# M8416P.net
KiCad netlist of a schematic drawn in EAGLE
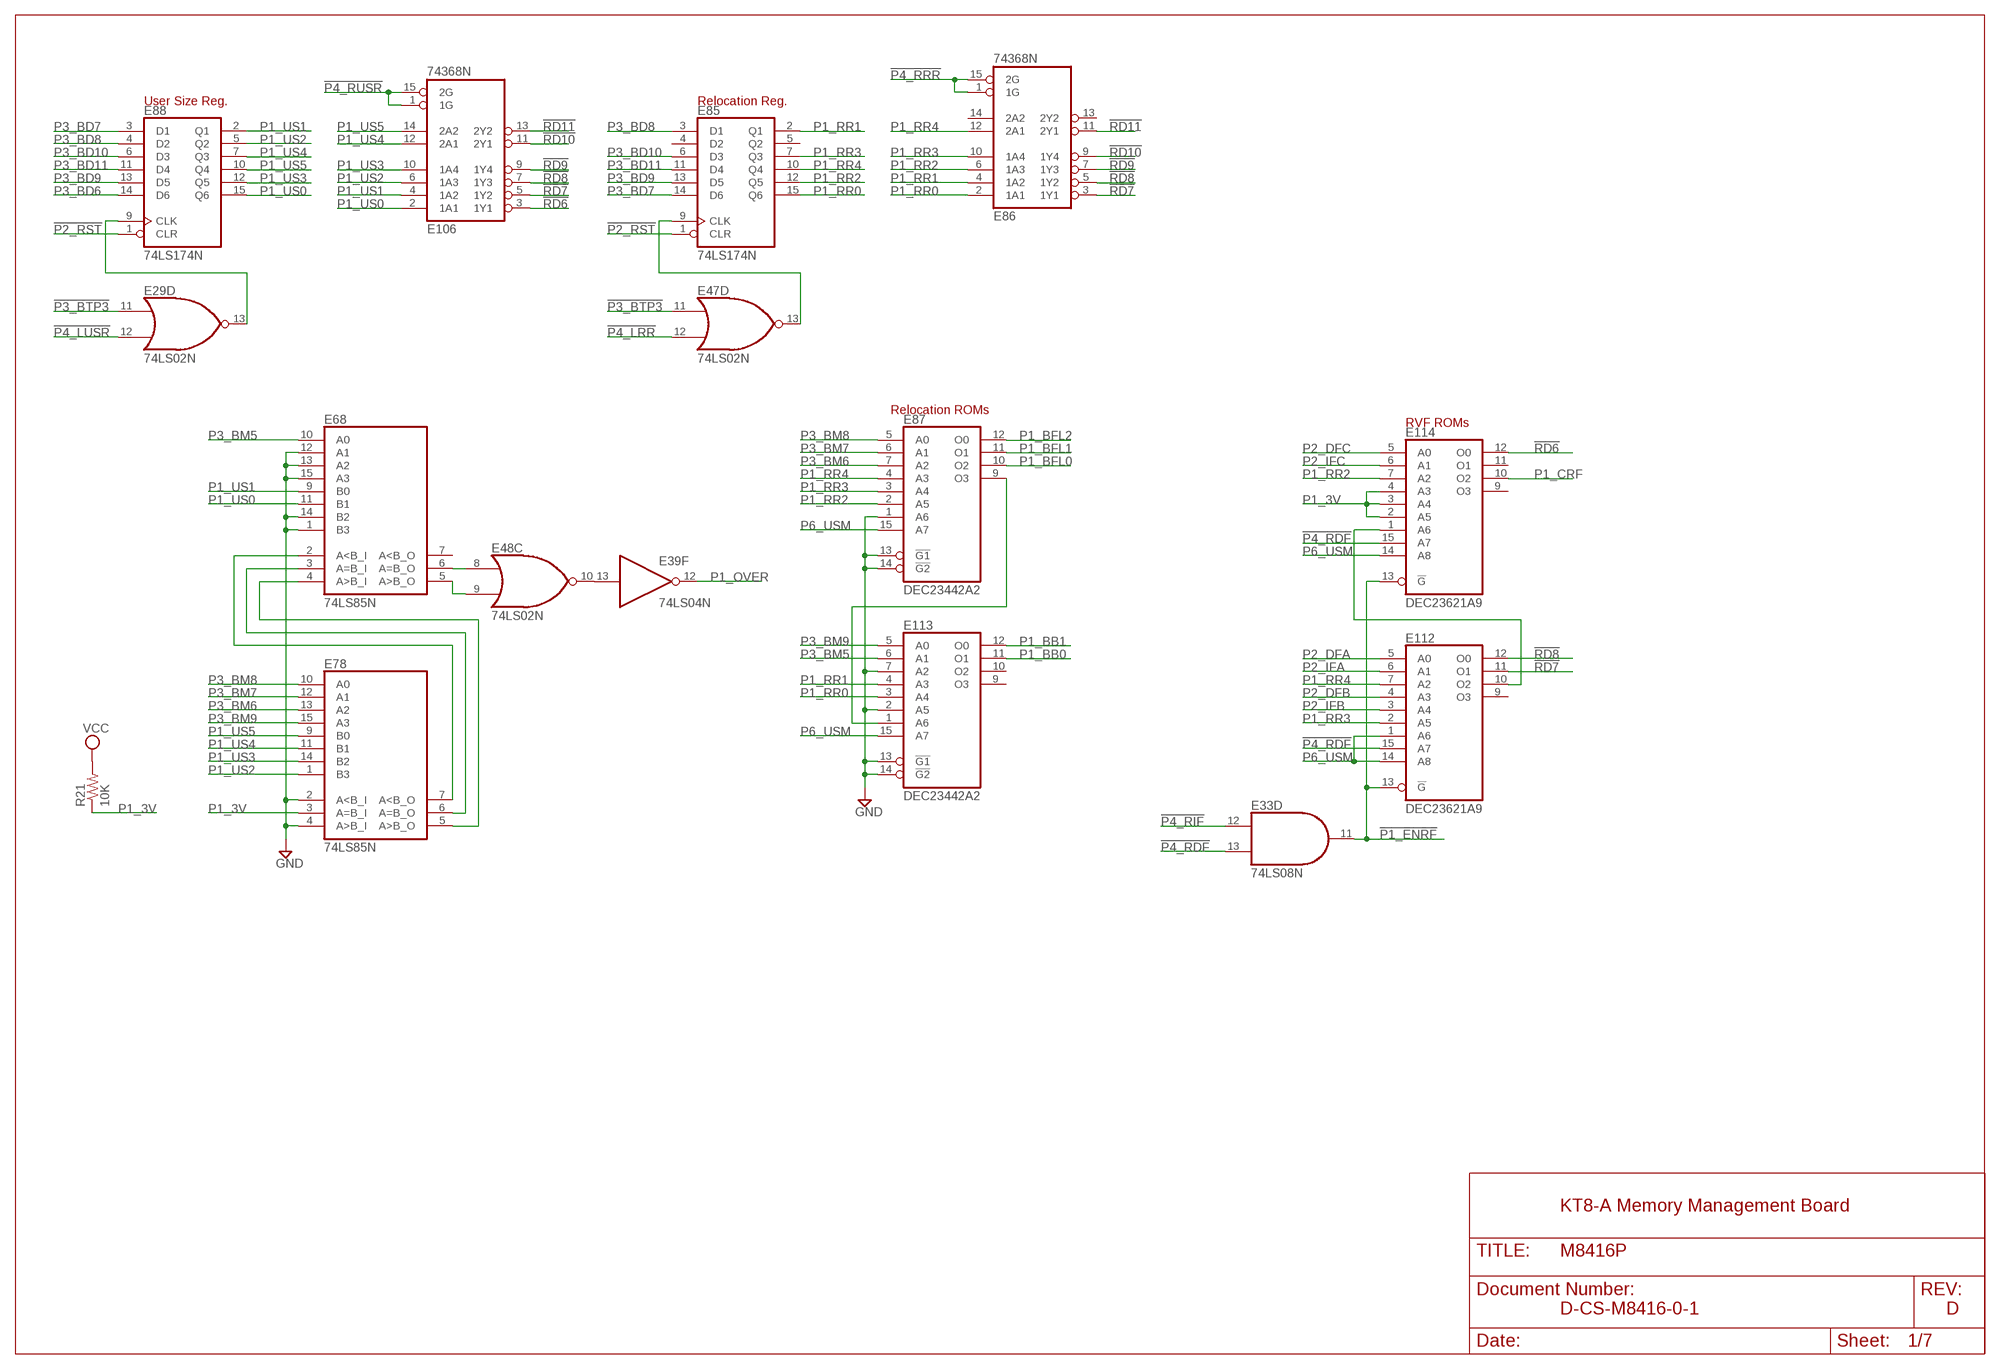
[diagram p0: schematic, sheet 1]
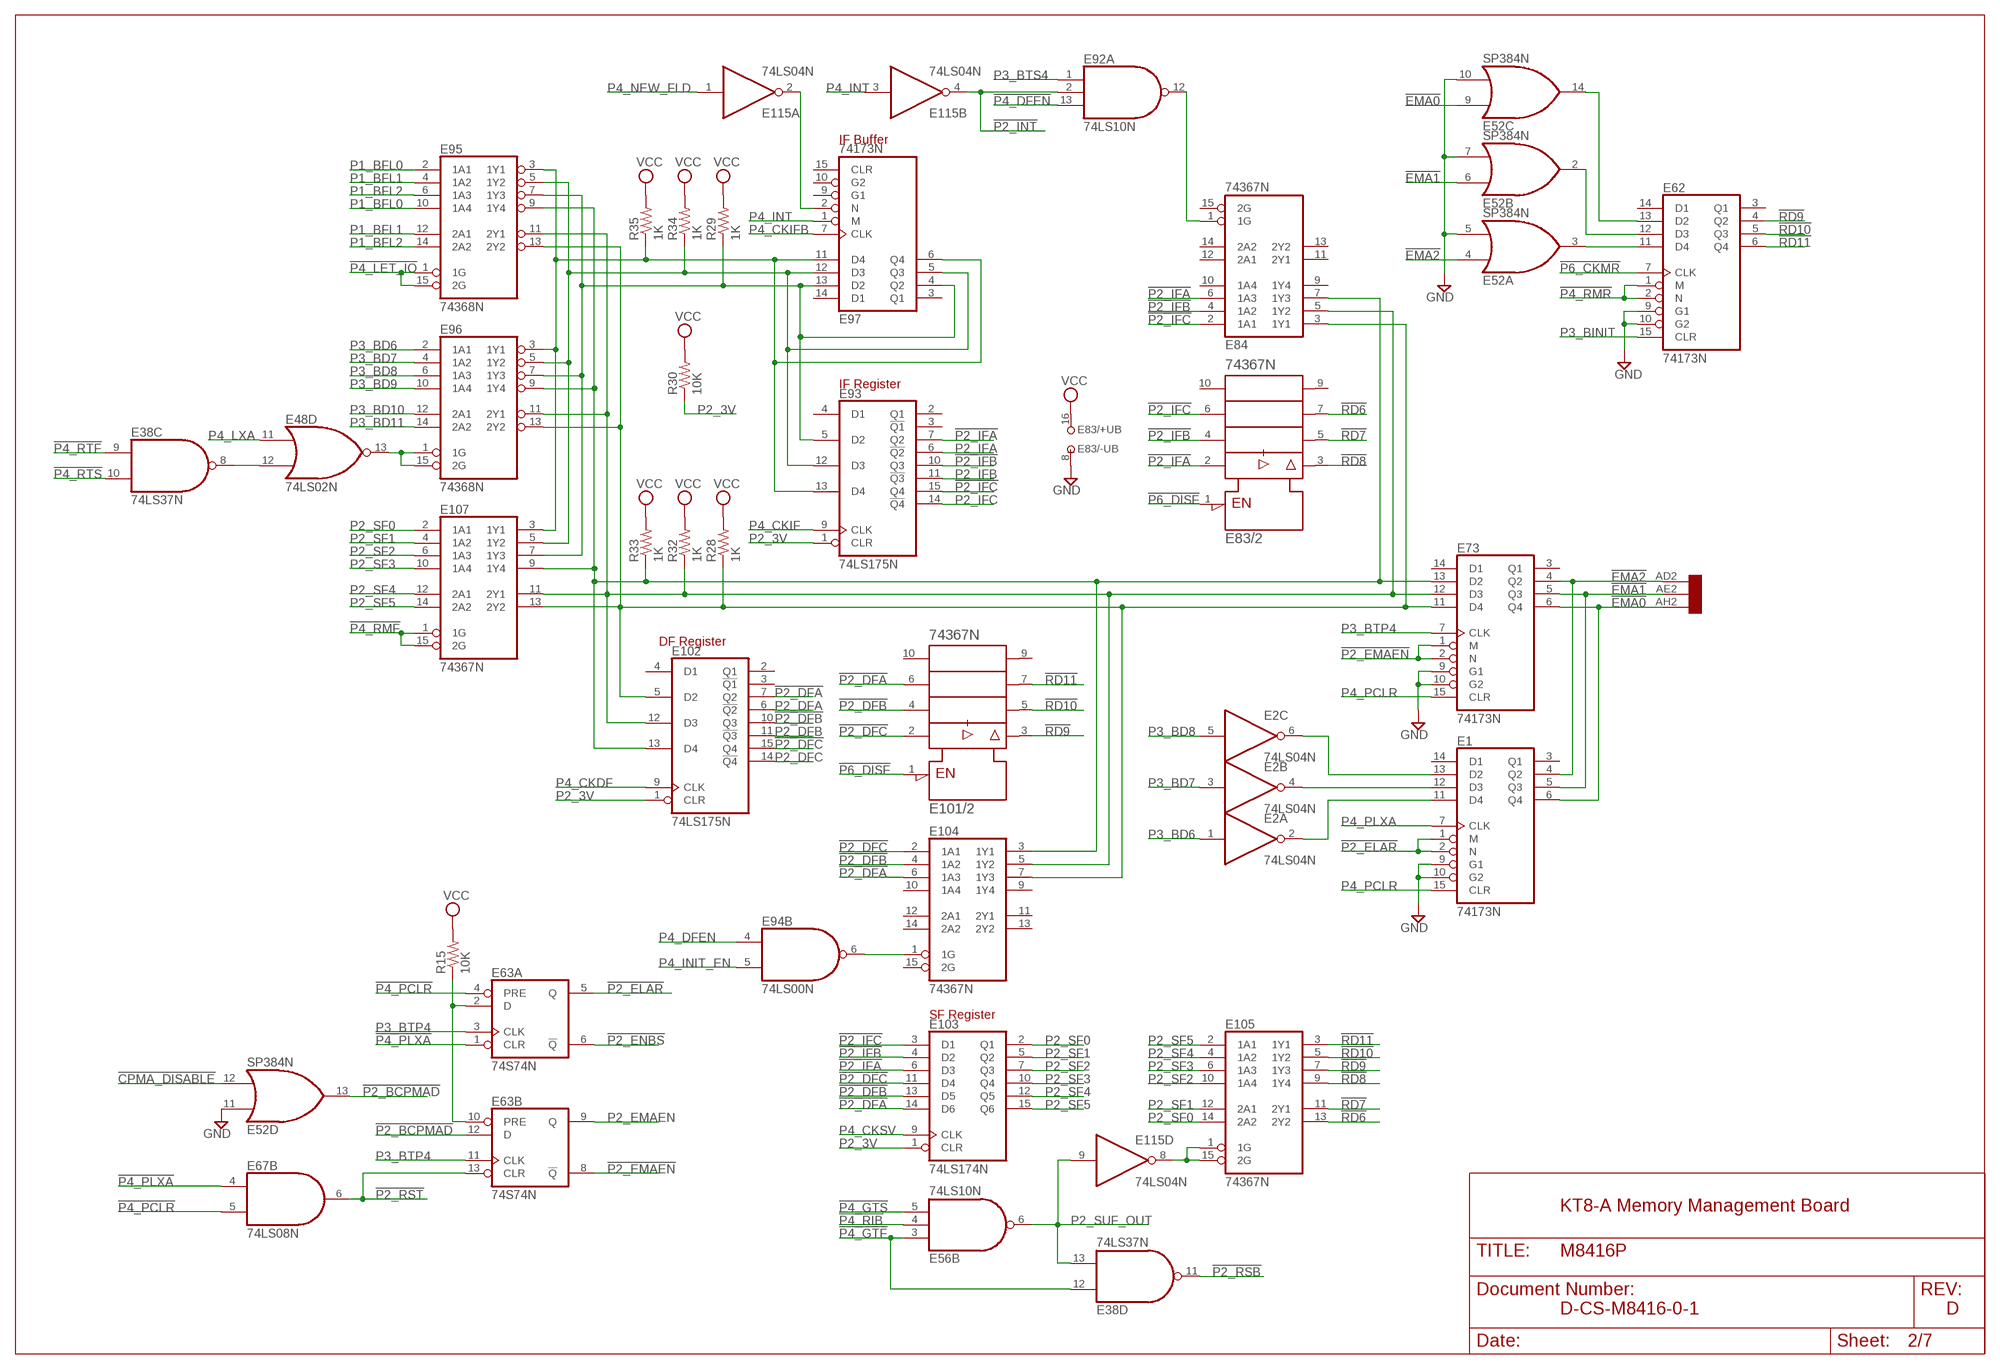
[diagram p1: schematic, sheet 2]
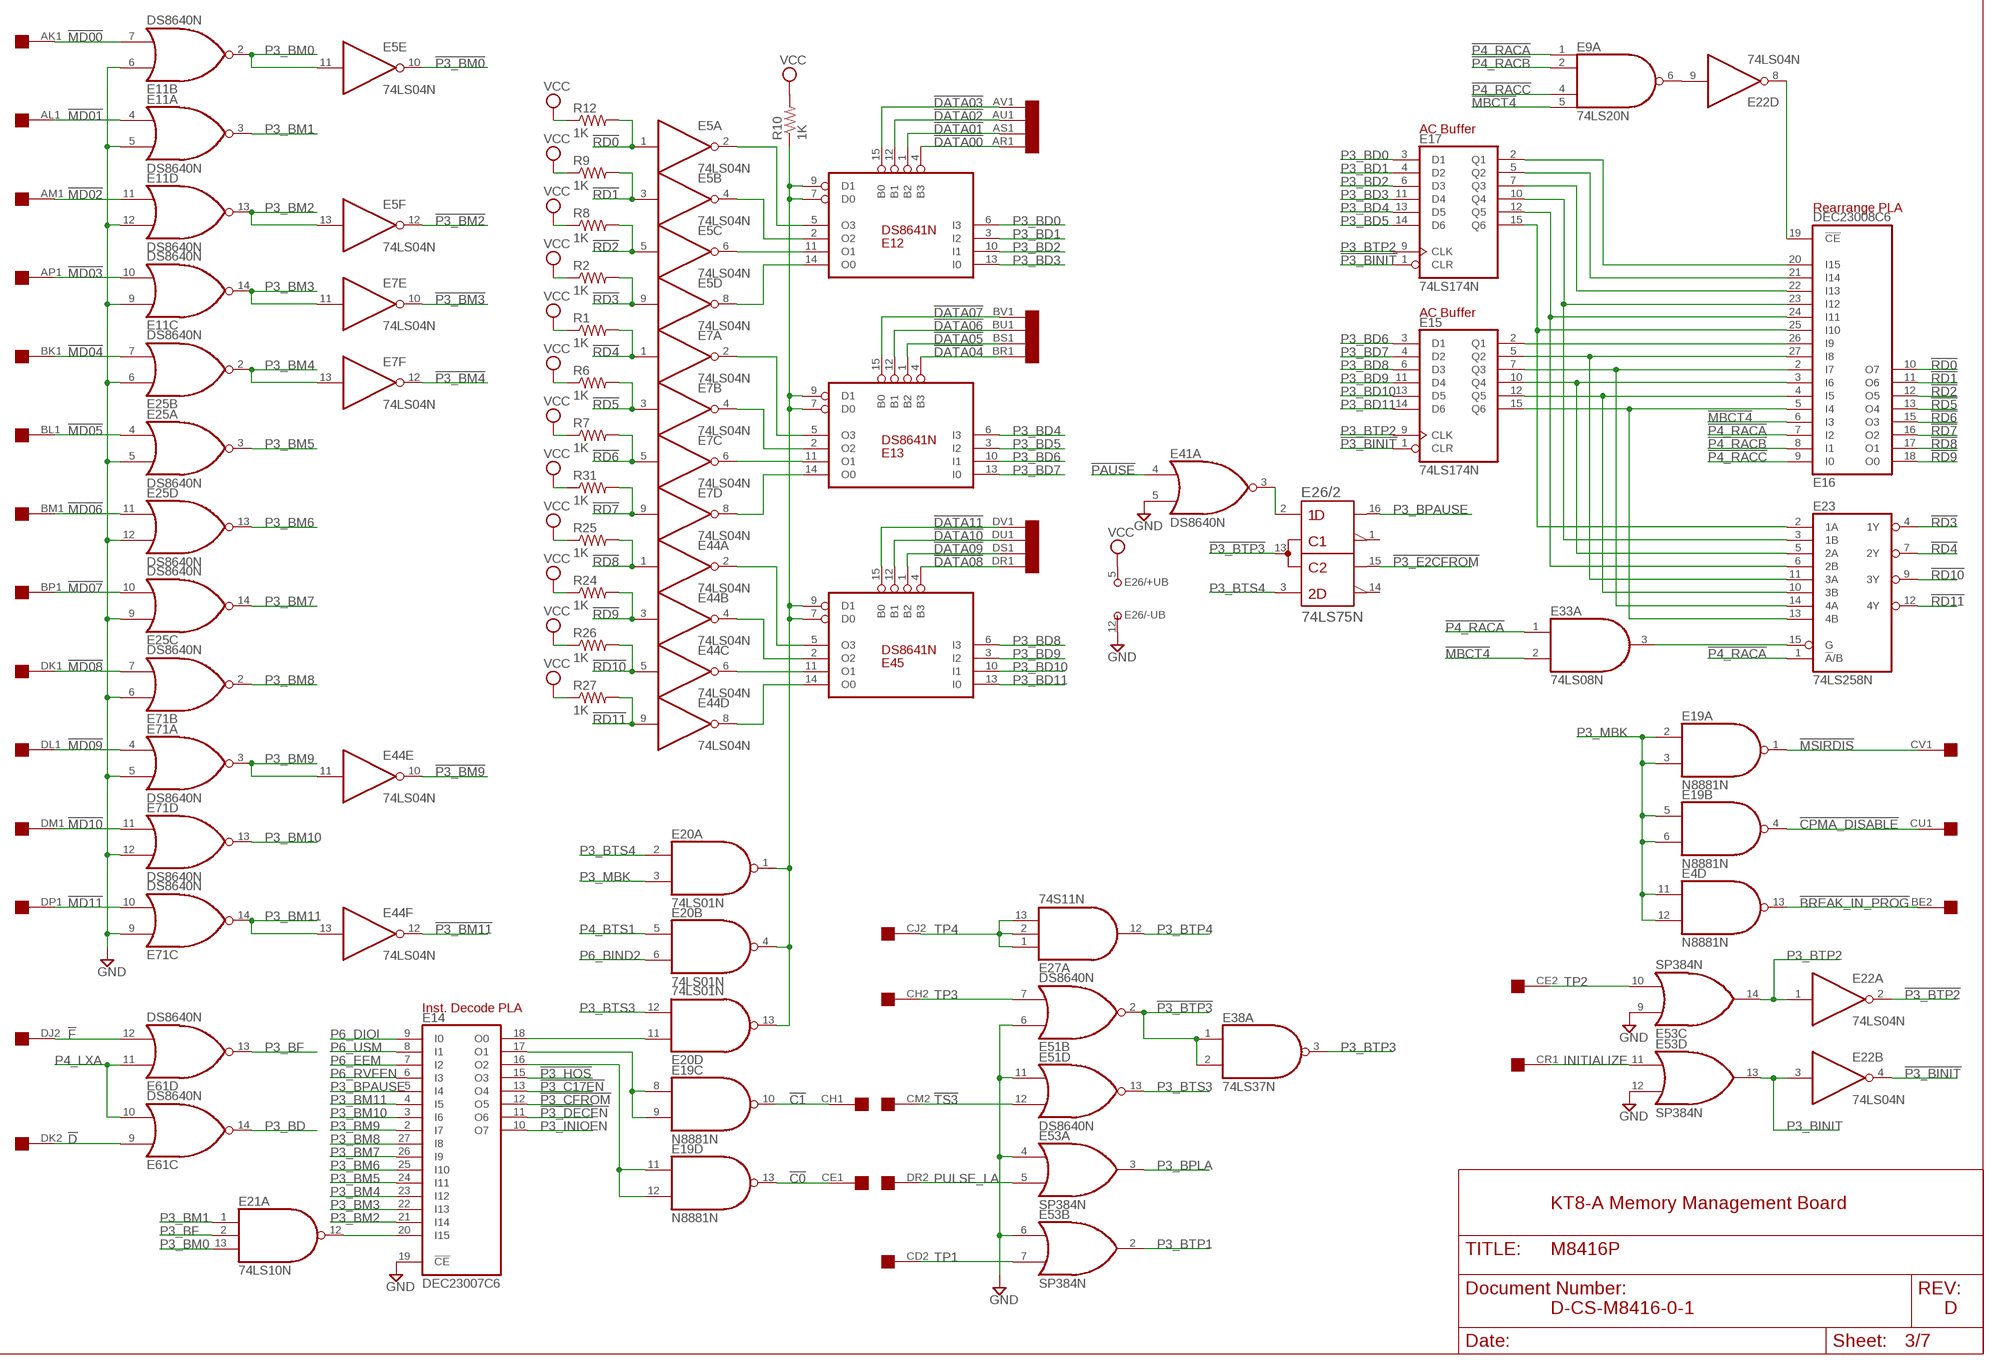
[diagram p2: schematic, sheet 3, part 1 of 2]
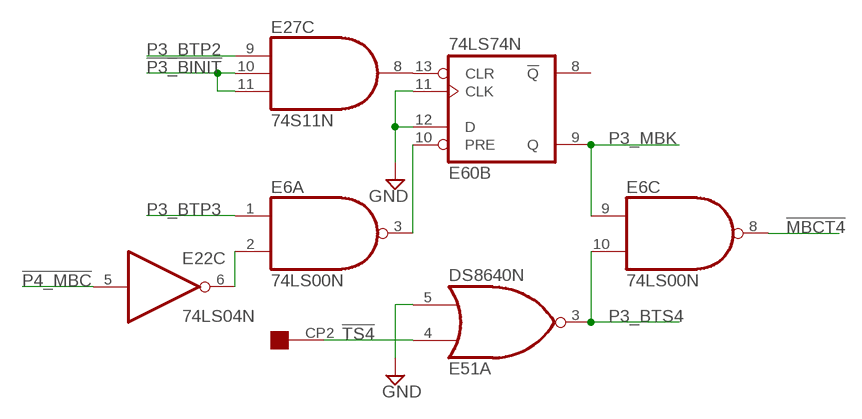
[diagram p3: schematic, sheet 3, part 2 of 2]
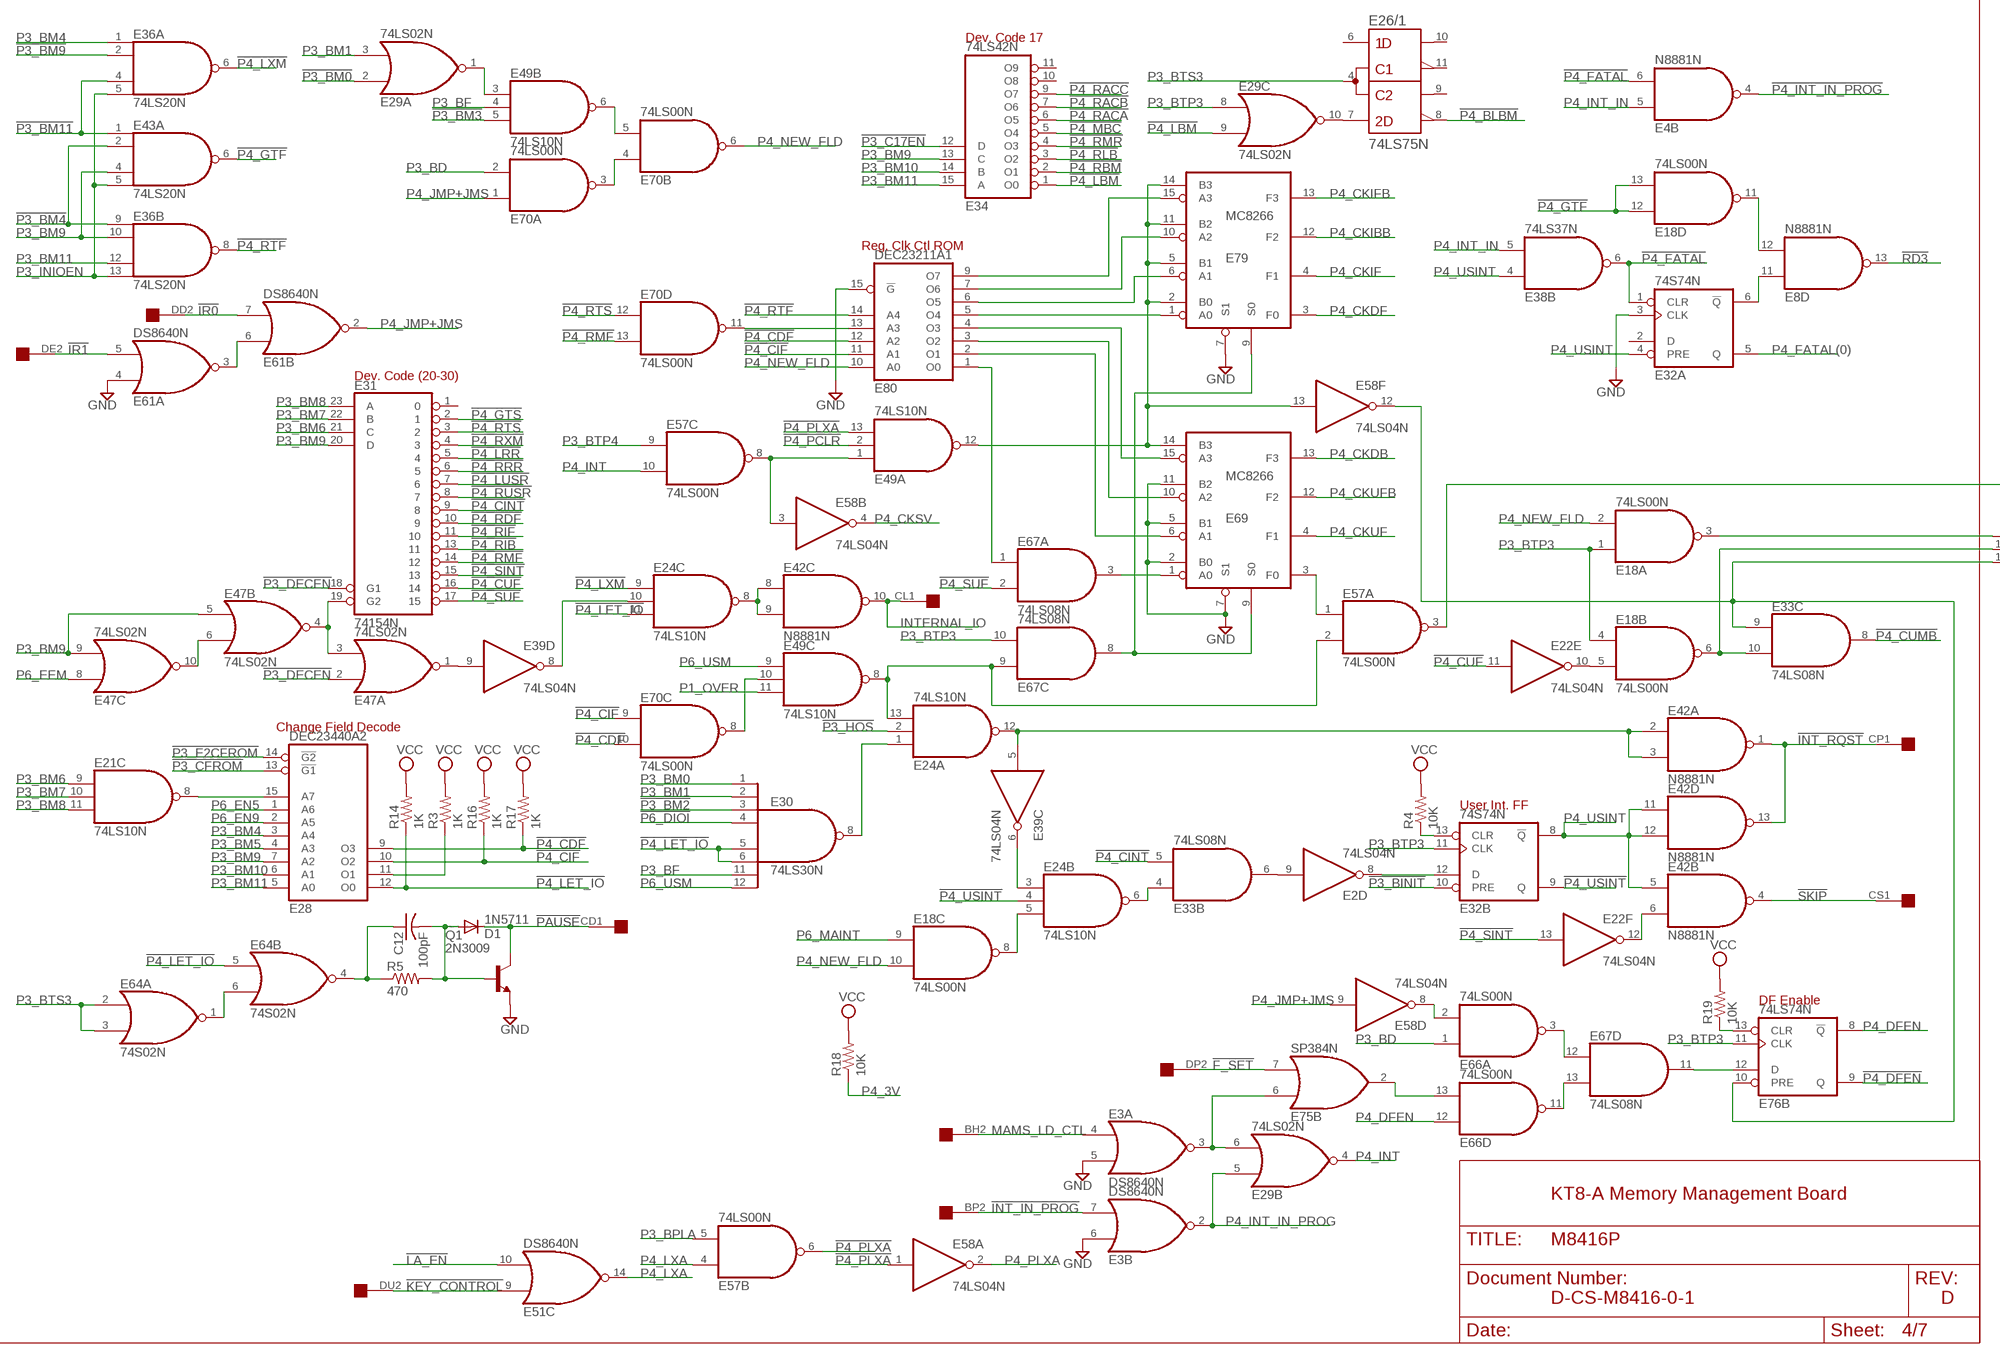
[diagram p4: schematic, sheet 4, part 1 of 2]
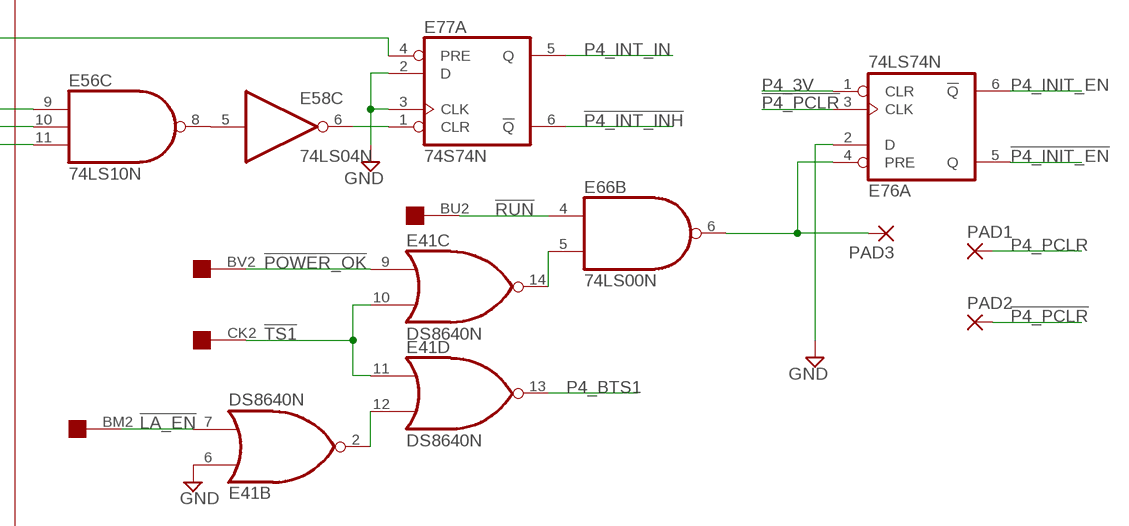
[diagram p5: schematic, sheet 4, part 2 of 2]
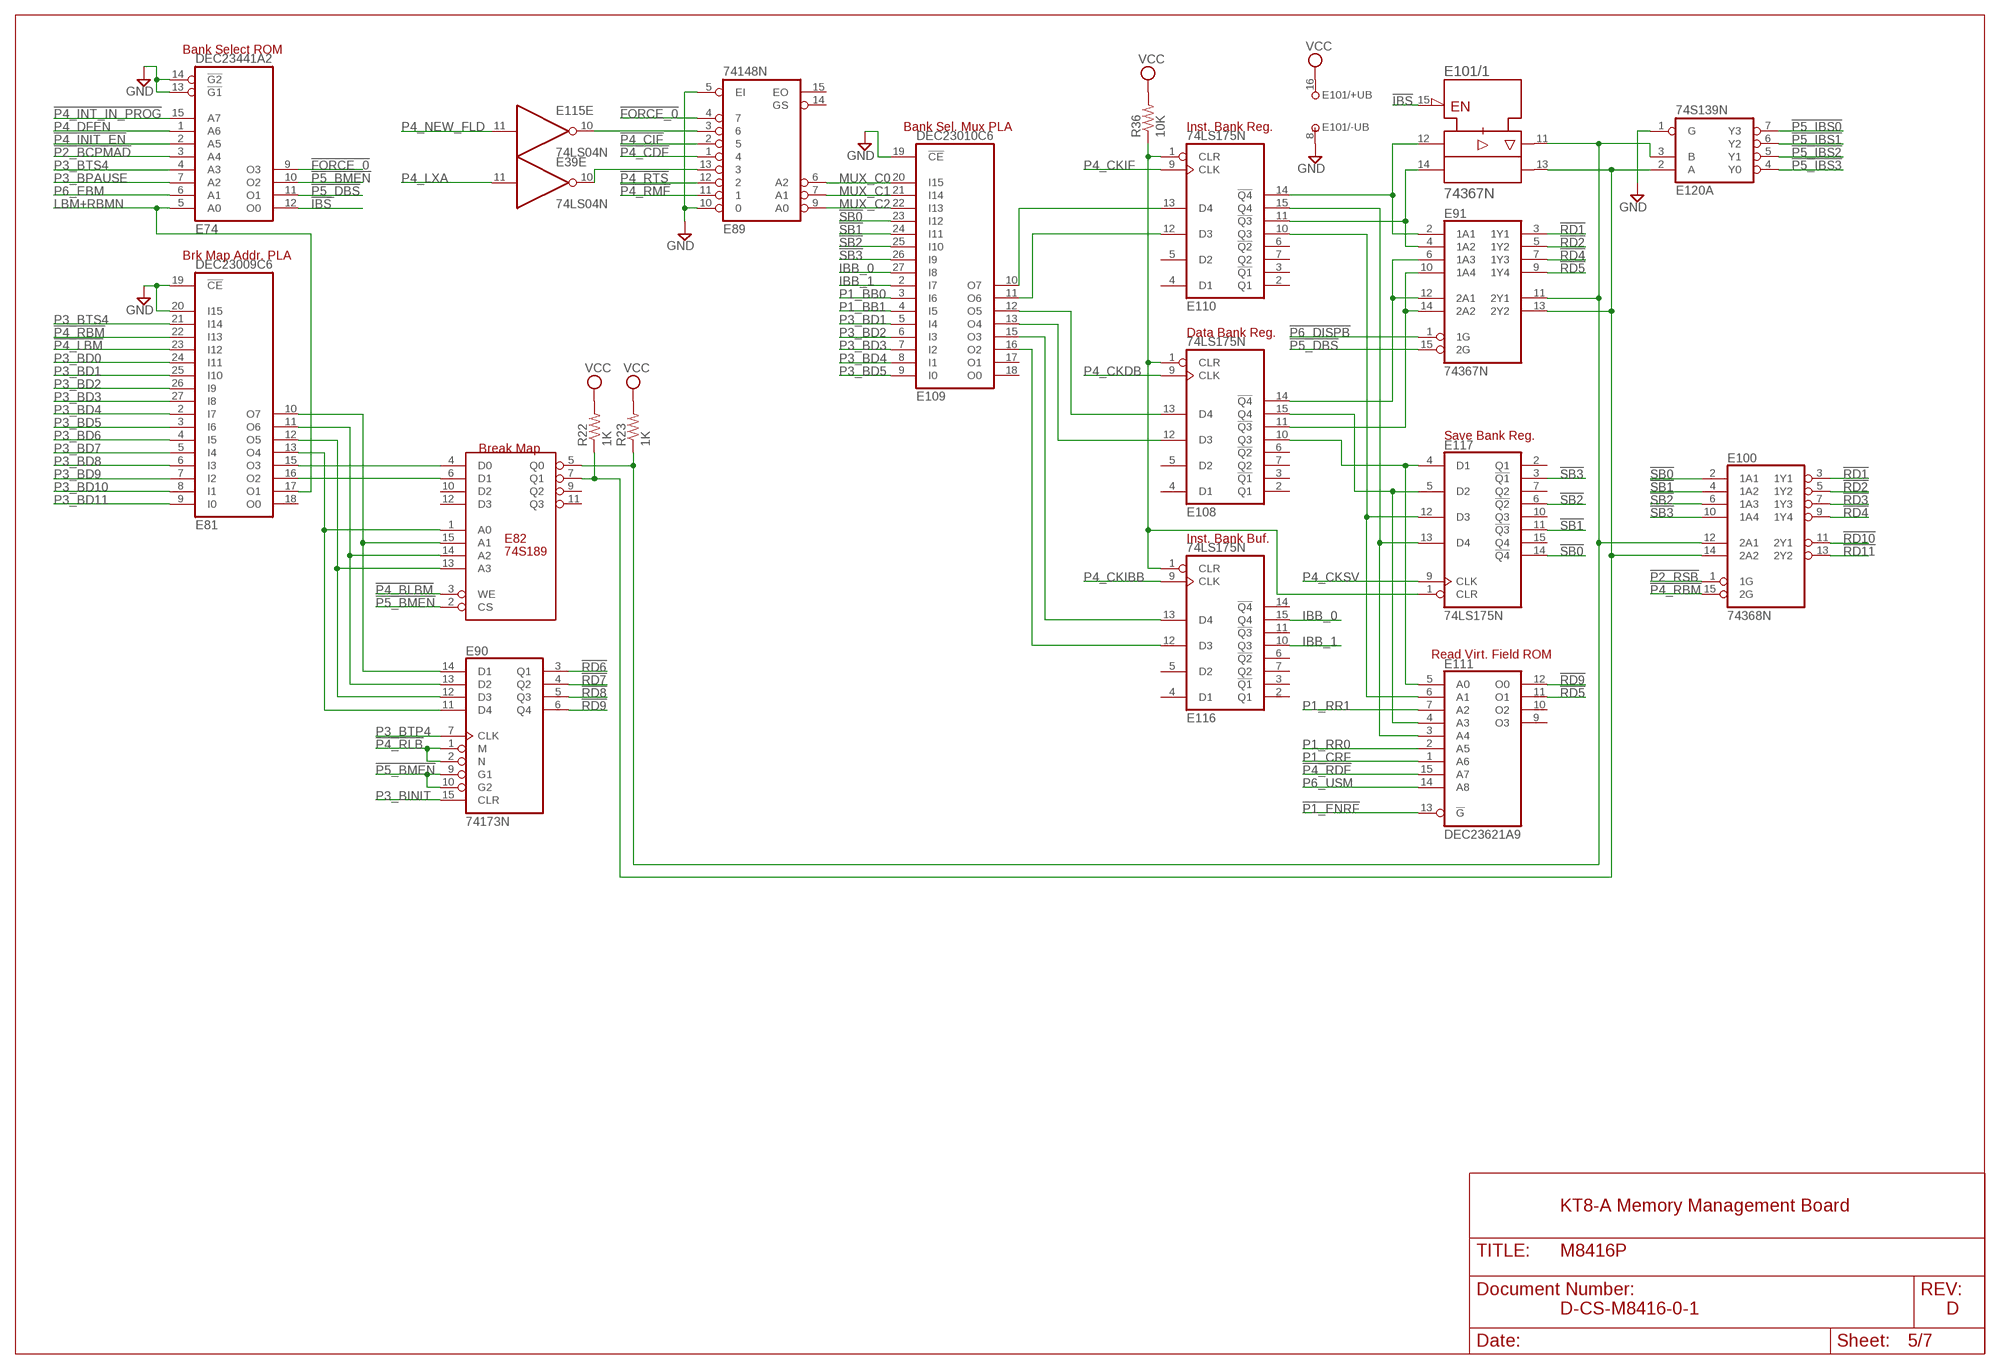
[diagram p6: schematic, sheet 5]
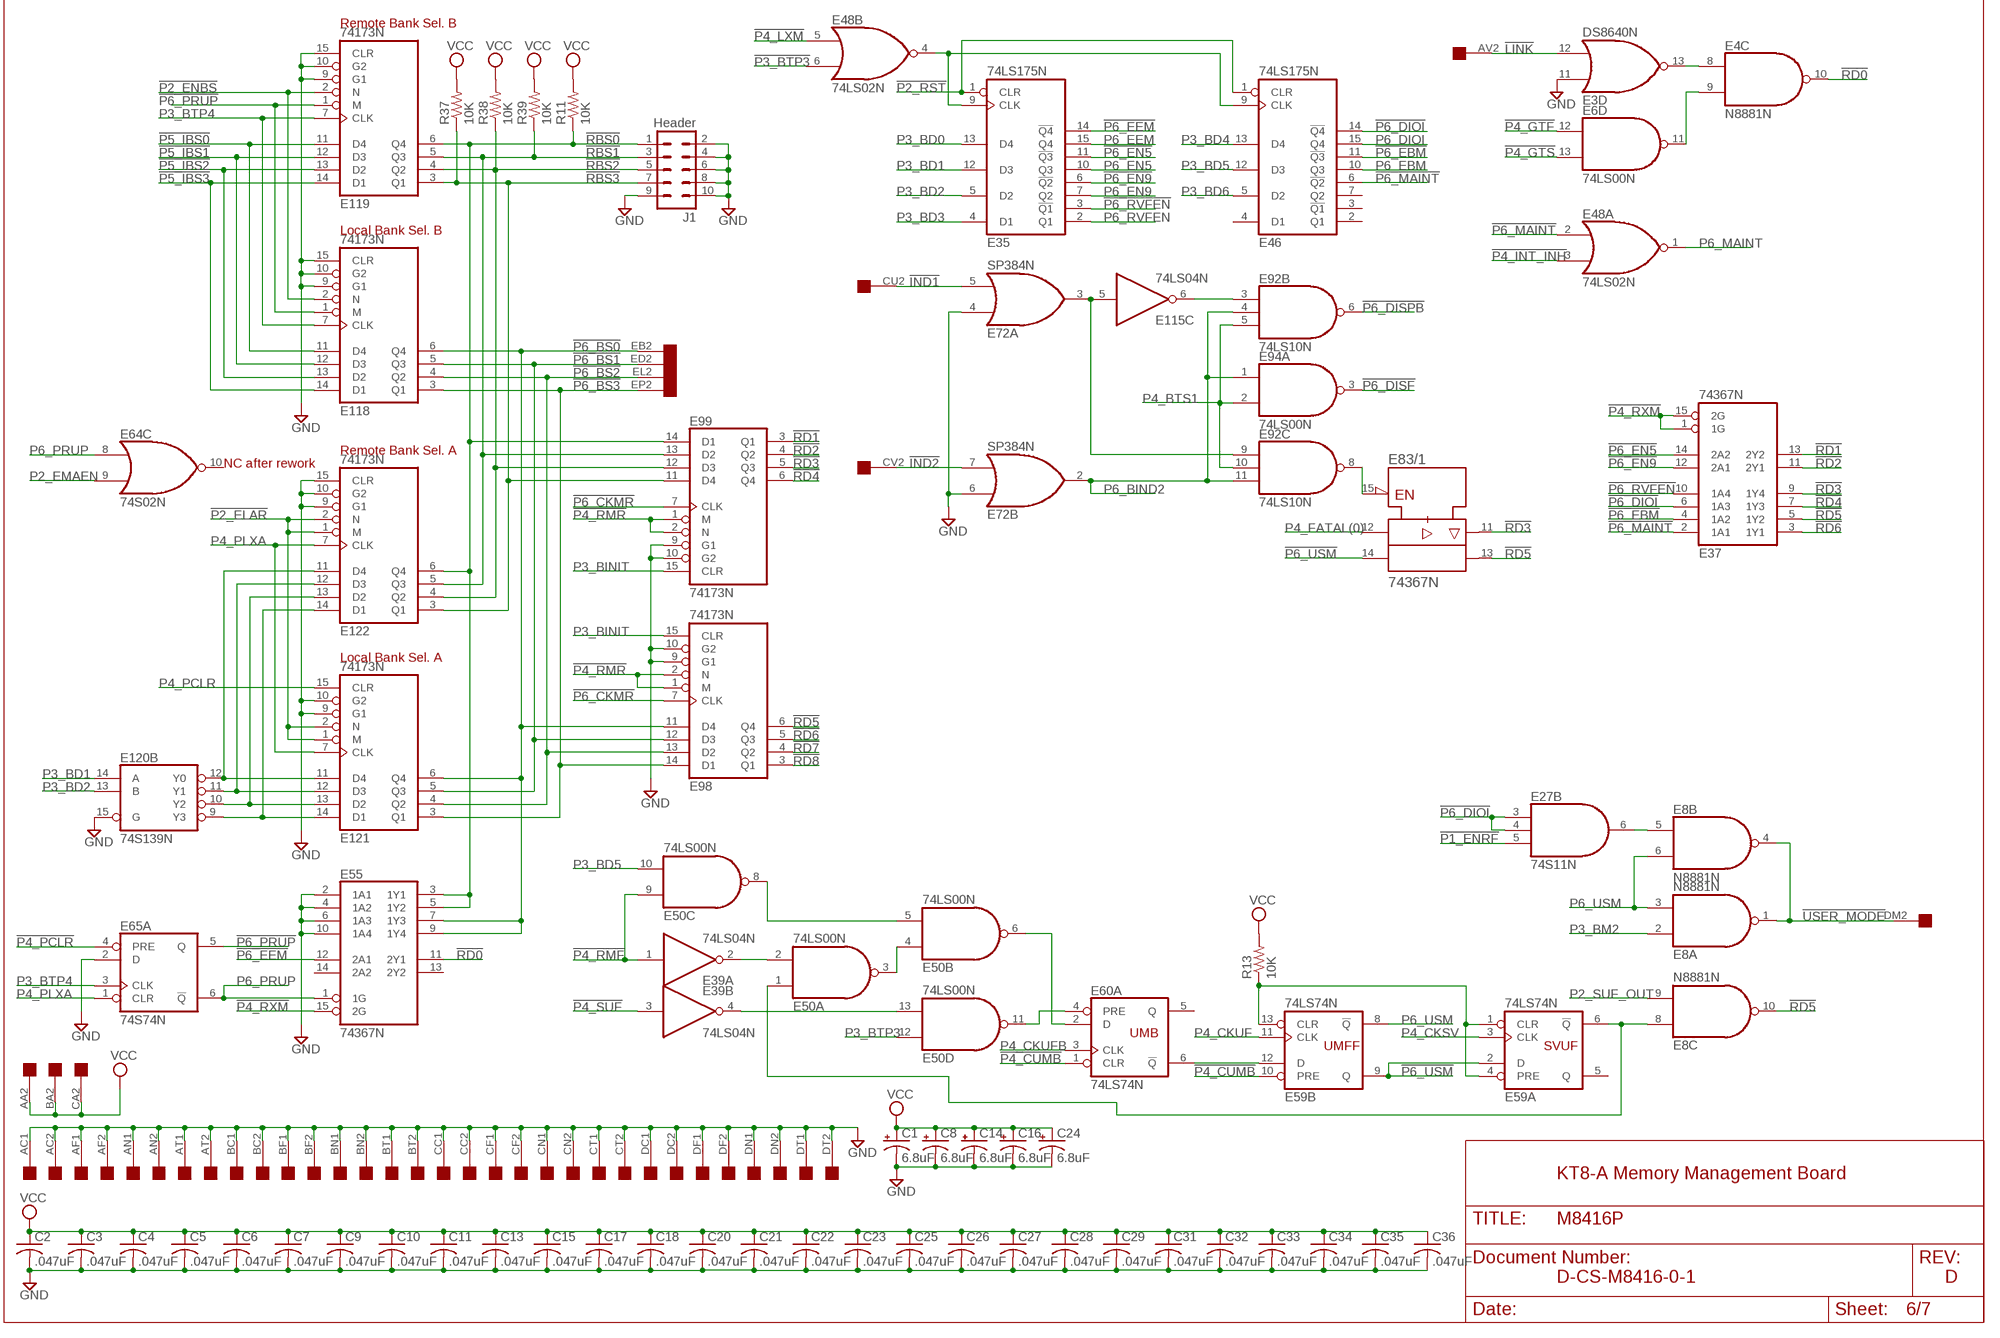
[diagram p7: schematic, sheet 6, part 1 of 2]
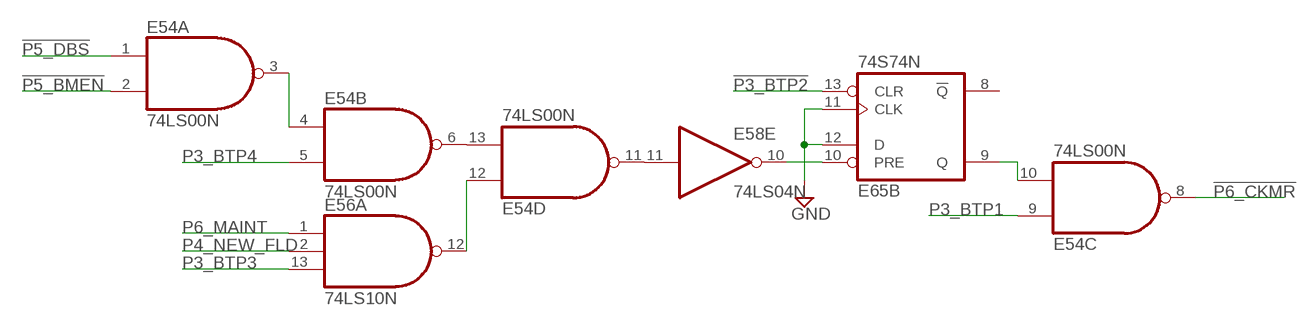
[diagram p8: schematic, sheet 6, part 2 of 2]
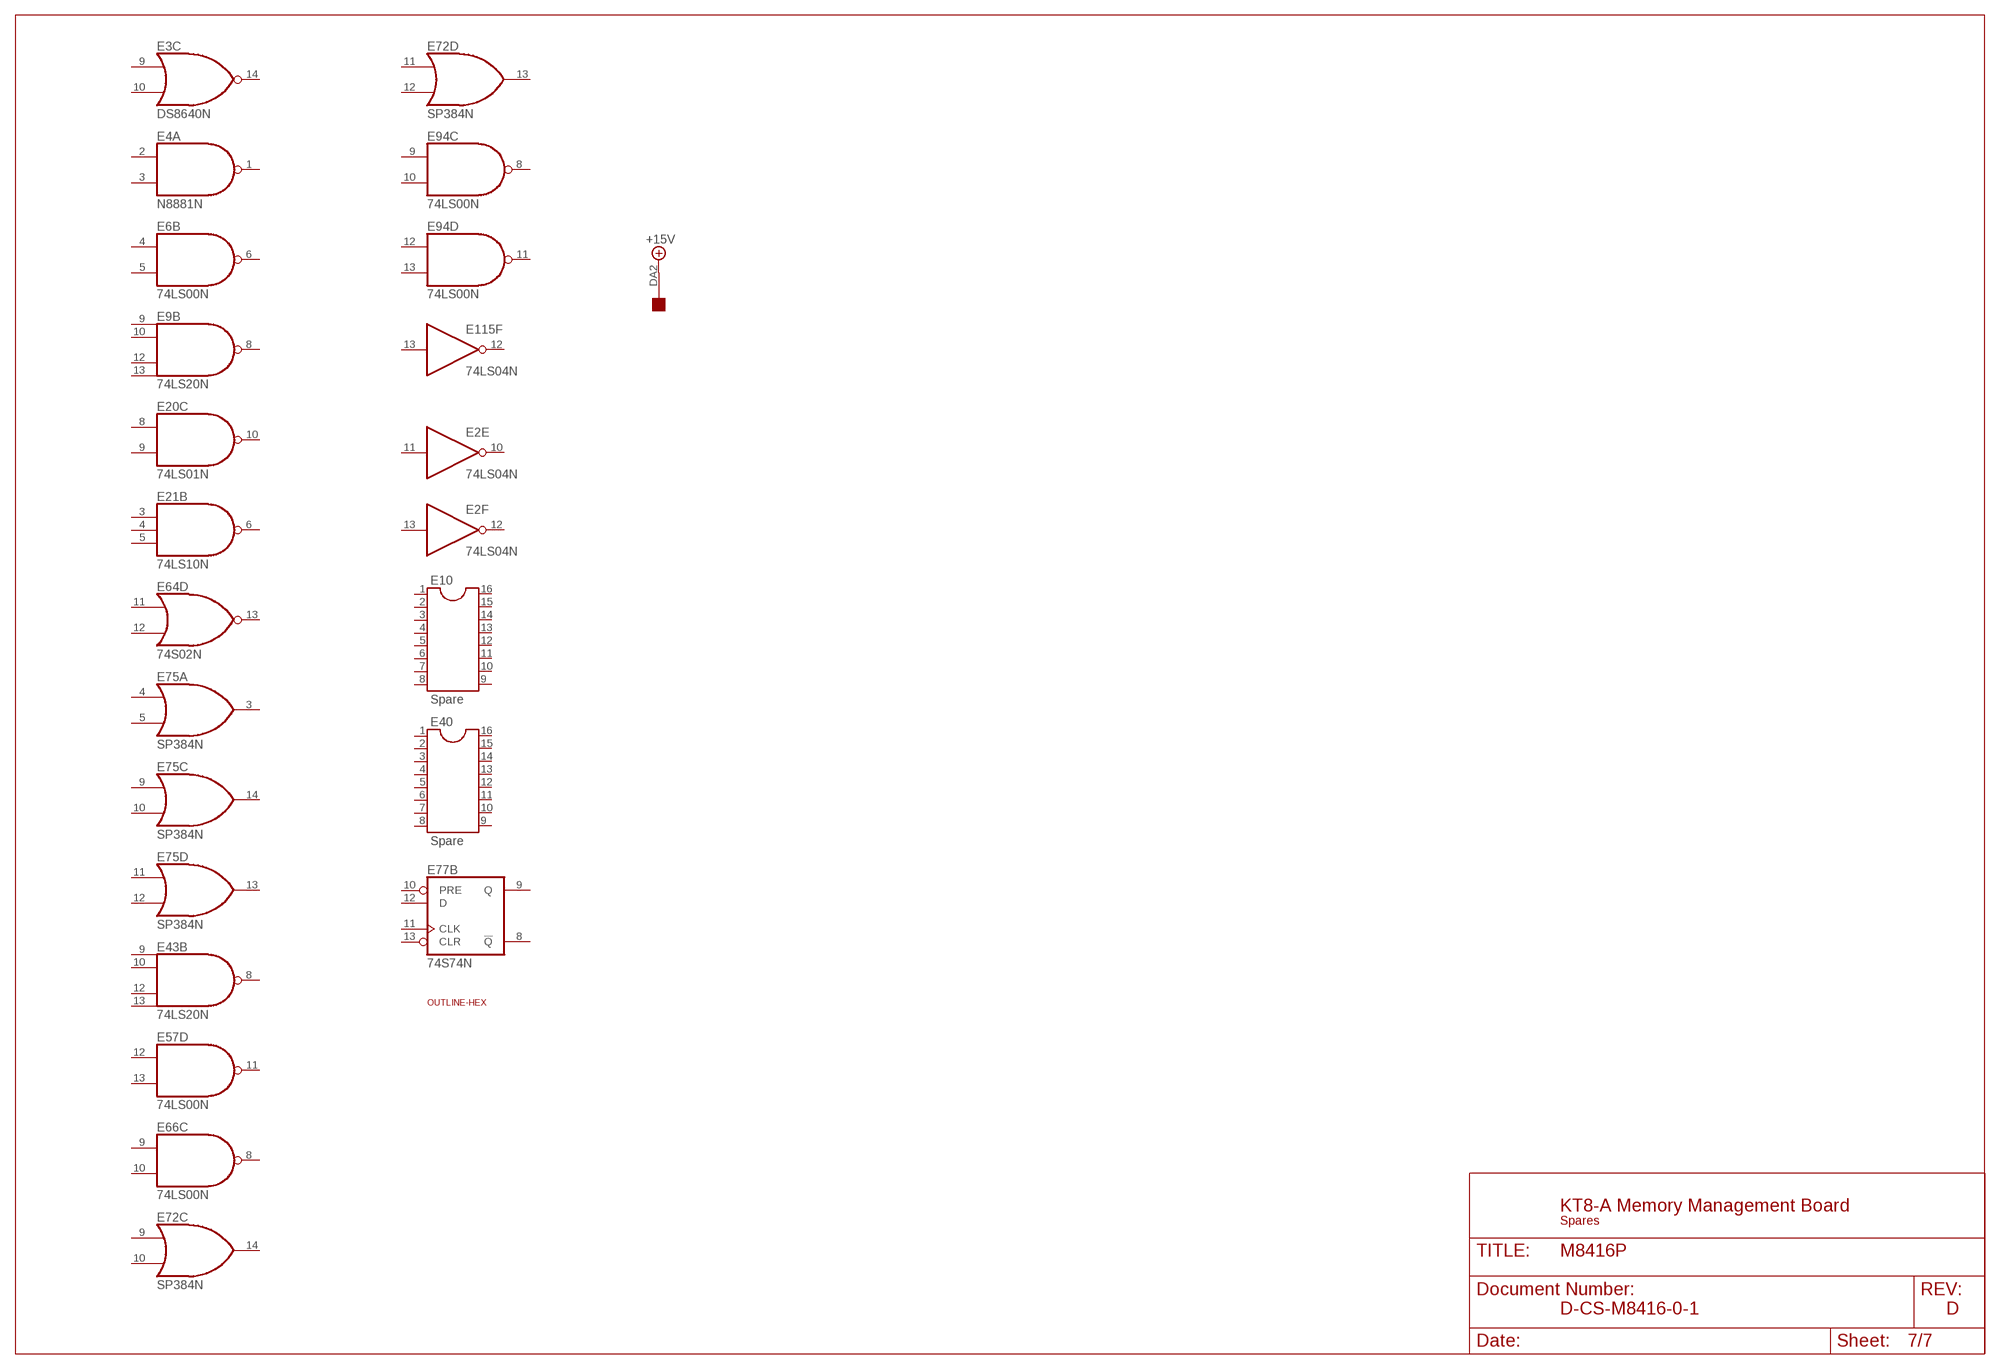
[diagram p9: schematic, sheet 7]

(export (version "E")
  (design (tool "Eeschema 10.0.6"))
  (components
    (comp (ref "E1")
      (value "74173N")
      (footprint "eagle-import:DIL16")
      (libsource (lib "eagle-import") (part "74173NLS"))
    )
    (comp (ref "E2")
      (value "74LS04N")
      (footprint "eagle-import:DIL14")
      (libsource (lib "eagle-import") (part "7404NLS"))
    )
    (comp (ref "E38")
      (value "74LS37N")
      (footprint "eagle-import:DIL14")
      (libsource (lib "eagle-import") (part "7437NLS"))
    )
    (comp (ref "E48")
      (value "74LS02N")
      (footprint "eagle-import:DIL14")
      (libsource (lib "eagle-import") (part "7402NLS"))
    )
    (comp (ref "E52")
      (value "SP384N")
      (footprint "eagle-import:DIL14")
      (libsource (lib "eagle-import") (part "SP384N"))
    )
    (comp (ref "E56")
      (value "74LS10N")
      (footprint "eagle-import:DIL14")
      (libsource (lib "eagle-import") (part "7410NLS"))
    )
    (comp (ref "E62")
      (value "74173N")
      (footprint "eagle-import:DIL16")
      (libsource (lib "eagle-import") (part "74173NLS"))
    )
    (comp (ref "E63")
      (value "74S74N")
      (footprint "eagle-import:DIL14")
      (libsource (lib "eagle-import") (part "7474NS"))
    )
    (comp (ref "E67")
      (value "74LS08N")
      (footprint "eagle-import:DIL14")
      (libsource (lib "eagle-import") (part "7408NLS"))
    )
    (comp (ref "E73")
      (value "74173N")
      (footprint "eagle-import:DIL16")
      (libsource (lib "eagle-import") (part "74173NLS"))
    )
    (comp (ref "E83")
      (value "74367N")
      (footprint "eagle-import:DIL16")
      (libsource (lib "eagle-import") (part "74367N"))
    )
    (comp (ref "E84")
      (value "74367N")
      (footprint "eagle-import:DIL16")
      (libsource (lib "eagle-import") (part "74xx-us_74367N"))
    )
    (comp (ref "E92")
      (value "74LS10N")
      (footprint "eagle-import:DIL14")
      (libsource (lib "eagle-import") (part "7410NLS"))
    )
    (comp (ref "E93")
      (value "74LS175N")
      (footprint "eagle-import:DIL16")
      (libsource (lib "eagle-import") (part "74175NLS"))
    )
    (comp (ref "E94")
      (value "74LS00N")
      (footprint "eagle-import:DIL14")
      (libsource (lib "eagle-import") (part "7400NLS"))
    )
    (comp (ref "E95")
      (value "74368N")
      (footprint "eagle-import:DIL16")
      (libsource (lib "eagle-import") (part "74368N"))
    )
    (comp (ref "E96")
      (value "74368N")
      (footprint "eagle-import:DIL16")
      (libsource (lib "eagle-import") (part "74368N"))
    )
    (comp (ref "E97")
      (value "74173N")
      (footprint "eagle-import:DIL16")
      (libsource (lib "eagle-import") (part "74173NLS"))
    )
    (comp (ref "E101")
      (value "74367N")
      (footprint "eagle-import:DIL16")
      (libsource (lib "eagle-import") (part "74367N"))
    )
    (comp (ref "E102")
      (value "74LS175N")
      (footprint "eagle-import:DIL16")
      (libsource (lib "eagle-import") (part "74175NLS"))
    )
    (comp (ref "E103")
      (value "74LS174N")
      (footprint "eagle-import:DIL16")
      (libsource (lib "eagle-import") (part "74174NLS"))
    )
    (comp (ref "E104")
      (value "74367N")
      (footprint "eagle-import:DIL16")
      (libsource (lib "eagle-import") (part "74xx-us_74367N"))
    )
    (comp (ref "E105")
      (value "74367N")
      (footprint "eagle-import:DIL16")
      (libsource (lib "eagle-import") (part "74xx-us_74367N"))
    )
    (comp (ref "E107")
      (value "74367N")
      (footprint "eagle-import:DIL16")
      (libsource (lib "eagle-import") (part "74xx-us_74367N"))
    )
    (comp (ref "E115")
      (value "74LS04N")
      (footprint "eagle-import:DIL14")
      (libsource (lib "eagle-import") (part "7404NLS"))
    )
    (comp (ref "R15")
      (value "10K")
      (footprint "eagle-import:0207_10")
      (libsource (lib "eagle-import") (part "R-US_0207/10"))
    )
    (comp (ref "R28")
      (value "1K")
      (footprint "eagle-import:0207_10")
      (libsource (lib "eagle-import") (part "R-US_0207/10"))
    )
    (comp (ref "R29")
      (value "1K")
      (footprint "eagle-import:0207_10")
      (libsource (lib "eagle-import") (part "R-US_0207/10"))
    )
    (comp (ref "R30")
      (value "10K")
      (footprint "eagle-import:0207_10")
      (libsource (lib "eagle-import") (part "R-US_0207/10"))
    )
    (comp (ref "R32")
      (value "1K")
      (footprint "eagle-import:0207_10")
      (libsource (lib "eagle-import") (part "R-US_0207/10"))
    )
    (comp (ref "R33")
      (value "1K")
      (footprint "eagle-import:0207_10")
      (libsource (lib "eagle-import") (part "R-US_0207/10"))
    )
    (comp (ref "R34")
      (value "1K")
      (footprint "eagle-import:0207_10")
      (libsource (lib "eagle-import") (part "R-US_0207/10"))
    )
    (comp (ref "R35")
      (value "1K")
      (footprint "eagle-import:0207_10")
      (libsource (lib "eagle-import") (part "R-US_0207/10"))
    )
    (comp (ref "U$1")
      (value "HEX")
      (footprint "eagle-import:EDGE-CON12")
      (libsource (lib "eagle-import") (part "HEX"))
    )
    (comp (ref "C1")
      (value "6.8uF")
      (footprint "eagle-import:E12-8")
      (libsource (lib "eagle-import") (part "CPOL-USE20-8AXIAL"))
    )
    (comp (ref "C2")
      (value ".047uF")
      (footprint "eagle-import:C102-043X133")
      (libsource (lib "eagle-import") (part "C-US102-043X133"))
    )
    (comp (ref "C3")
      (value ".047uF")
      (footprint "eagle-import:C102-043X133")
      (libsource (lib "eagle-import") (part "C-US102-043X133"))
    )
    (comp (ref "C4")
      (value ".047uF")
      (footprint "eagle-import:C102-043X133")
      (libsource (lib "eagle-import") (part "C-US102-043X133"))
    )
    (comp (ref "C5")
      (value ".047uF")
      (footprint "eagle-import:C102-043X133")
      (libsource (lib "eagle-import") (part "C-US102-043X133"))
    )
    (comp (ref "C6")
      (value ".047uF")
      (footprint "eagle-import:C102-043X133")
      (libsource (lib "eagle-import") (part "C-US102-043X133"))
    )
    (comp (ref "C7")
      (value ".047uF")
      (footprint "eagle-import:C102-043X133")
      (libsource (lib "eagle-import") (part "C-US102-043X133"))
    )
    (comp (ref "C8")
      (value "6.8uF")
      (footprint "eagle-import:E12-8")
      (libsource (lib "eagle-import") (part "CPOL-USE20-8AXIAL"))
    )
    (comp (ref "C9")
      (value ".047uF")
      (footprint "eagle-import:C102-043X133")
      (libsource (lib "eagle-import") (part "C-US102-043X133"))
    )
    (comp (ref "C10")
      (value ".047uF")
      (footprint "eagle-import:C102-043X133")
      (libsource (lib "eagle-import") (part "C-US102-043X133"))
    )
    (comp (ref "C11")
      (value ".047uF")
      (footprint "eagle-import:C102-043X133")
      (libsource (lib "eagle-import") (part "C-US102-043X133"))
    )
    (comp (ref "C13")
      (value ".047uF")
      (footprint "eagle-import:C102-043X133")
      (libsource (lib "eagle-import") (part "C-US102-043X133"))
    )
    (comp (ref "C14")
      (value "6.8uF")
      (footprint "eagle-import:E12-8")
      (libsource (lib "eagle-import") (part "CPOL-USE20-8AXIAL"))
    )
    (comp (ref "C15")
      (value ".047uF")
      (footprint "eagle-import:C102-043X133")
      (libsource (lib "eagle-import") (part "C-US102-043X133"))
    )
    (comp (ref "C16")
      (value "6.8uF")
      (footprint "eagle-import:E12-8")
      (libsource (lib "eagle-import") (part "CPOL-USE20-8AXIAL"))
    )
    (comp (ref "C17")
      (value ".047uF")
      (footprint "eagle-import:C102-043X133")
      (libsource (lib "eagle-import") (part "C-US102-043X133"))
    )
    (comp (ref "C18")
      (value ".047uF")
      (footprint "eagle-import:C102-043X133")
      (libsource (lib "eagle-import") (part "C-US102-043X133"))
    )
    (comp (ref "C20")
      (value ".047uF")
      (footprint "eagle-import:C102-043X133")
      (libsource (lib "eagle-import") (part "C-US102-043X133"))
    )
    (comp (ref "C21")
      (value ".047uF")
      (footprint "eagle-import:C102-043X133")
      (libsource (lib "eagle-import") (part "C-US102-043X133"))
    )
    (comp (ref "C22")
      (value ".047uF")
      (footprint "eagle-import:C102-043X133")
      (libsource (lib "eagle-import") (part "C-US102-043X133"))
    )
    (comp (ref "C23")
      (value ".047uF")
      (footprint "eagle-import:C102-043X133")
      (libsource (lib "eagle-import") (part "C-US102-043X133"))
    )
    (comp (ref "C24")
      (value "6.8uF")
      (footprint "eagle-import:E12-8")
      (libsource (lib "eagle-import") (part "CPOL-USE20-8AXIAL"))
    )
    (comp (ref "C25")
      (value ".047uF")
      (footprint "eagle-import:C102-043X133")
      (libsource (lib "eagle-import") (part "C-US102-043X133"))
    )
    (comp (ref "C26")
      (value ".047uF")
      (footprint "eagle-import:C102-043X133")
      (libsource (lib "eagle-import") (part "C-US102-043X133"))
    )
    (comp (ref "C27")
      (value ".047uF")
      (footprint "eagle-import:C102-043X133")
      (libsource (lib "eagle-import") (part "C-US102-043X133"))
    )
    (comp (ref "C28")
      (value ".047uF")
      (footprint "eagle-import:C102-043X133")
      (libsource (lib "eagle-import") (part "C-US102-043X133"))
    )
    (comp (ref "C29")
      (value ".047uF")
      (footprint "eagle-import:C102-043X133")
      (libsource (lib "eagle-import") (part "C-US102-043X133"))
    )
    (comp (ref "C31")
      (value ".047uF")
      (footprint "eagle-import:C102-043X133")
      (libsource (lib "eagle-import") (part "C-US102-043X133"))
    )
    (comp (ref "C32")
      (value ".047uF")
      (footprint "eagle-import:C102-043X133")
      (libsource (lib "eagle-import") (part "C-US102-043X133"))
    )
    (comp (ref "C33")
      (value ".047uF")
      (footprint "eagle-import:C102-043X133")
      (libsource (lib "eagle-import") (part "C-US102-043X133"))
    )
    (comp (ref "C34")
      (value ".047uF")
      (footprint "eagle-import:C102-043X133")
      (libsource (lib "eagle-import") (part "C-US102-043X133"))
    )
    (comp (ref "C35")
      (value ".047uF")
      (footprint "eagle-import:C102-043X133")
      (libsource (lib "eagle-import") (part "C-US102-043X133"))
    )
    (comp (ref "C36")
      (value ".047uF")
      (footprint "eagle-import:C102-043X133")
      (libsource (lib "eagle-import") (part "C-US102-043X133"))
    )
    (comp (ref "E3")
      (value "DS8640N")
      (footprint "eagle-import:DIL14")
      (libsource (lib "eagle-import") (part "DS8640N"))
    )
    (comp (ref "E4")
      (value "N8881N")
      (footprint "eagle-import:DIL14")
      (libsource (lib "eagle-import") (part "N8881N"))
    )
    (comp (ref "E6")
      (value "74LS00N")
      (footprint "eagle-import:DIL14")
      (libsource (lib "eagle-import") (part "7400NLS"))
    )
    (comp (ref "E8")
      (value "N8881N")
      (footprint "eagle-import:DIL14")
      (libsource (lib "eagle-import") (part "N8881N"))
    )
    (comp (ref "E27")
      (value "74S11N")
      (footprint "eagle-import:DIL14")
      (libsource (lib "eagle-import") (part "7411NS"))
    )
    (comp (ref "E35")
      (value "74LS175N")
      (footprint "eagle-import:DIL16")
      (libsource (lib "eagle-import") (part "74175NLS"))
    )
    (comp (ref "E37")
      (value "74367N")
      (footprint "eagle-import:DIL16")
      (libsource (lib "eagle-import") (part "74xx-us_74367N"))
    )
    (comp (ref "E39")
      (value "74LS04N")
      (footprint "eagle-import:DIL14")
      (libsource (lib "eagle-import") (part "7404NLS"))
    )
    (comp (ref "E46")
      (value "74LS175N")
      (footprint "eagle-import:DIL16")
      (libsource (lib "eagle-import") (part "74175NLS"))
    )
    (comp (ref "E50")
      (value "74LS00N")
      (footprint "eagle-import:DIL14")
      (libsource (lib "eagle-import") (part "7400NLS"))
    )
    (comp (ref "E54")
      (value "74LS00N")
      (footprint "eagle-import:DIL14")
      (libsource (lib "eagle-import") (part "7400NLS"))
    )
    (comp (ref "E55")
      (value "74367N")
      (footprint "eagle-import:DIL16")
      (libsource (lib "eagle-import") (part "74xx-us_74367N"))
    )
    (comp (ref "E58")
      (value "74LS04N")
      (footprint "eagle-import:DIL14")
      (libsource (lib "eagle-import") (part "7404NLS"))
    )
    (comp (ref "E59")
      (value "74LS74N")
      (footprint "eagle-import:DIL14")
      (libsource (lib "eagle-import") (part "7474NLS"))
    )
    (comp (ref "E60")
      (value "74LS74N")
      (footprint "eagle-import:DIL14")
      (libsource (lib "eagle-import") (part "7474NLS"))
    )
    (comp (ref "E64")
      (value "74S02N")
      (footprint "eagle-import:DIL14")
      (libsource (lib "eagle-import") (part "7402NS"))
    )
    (comp (ref "E65")
      (value "74S74N")
      (footprint "eagle-import:DIL14")
      (libsource (lib "eagle-import") (part "7474NS"))
    )
    (comp (ref "E72")
      (value "SP384N")
      (footprint "eagle-import:DIL14")
      (libsource (lib "eagle-import") (part "SP384N"))
    )
    (comp (ref "E98")
      (value "74173N")
      (footprint "eagle-import:DIL16")
      (libsource (lib "eagle-import") (part "74173NLS"))
    )
    (comp (ref "E99")
      (value "74173N")
      (footprint "eagle-import:DIL16")
      (libsource (lib "eagle-import") (part "74173NLS"))
    )
    (comp (ref "E118")
      (value "74173N")
      (footprint "eagle-import:DIL16")
      (libsource (lib "eagle-import") (part "74173NLS"))
    )
    (comp (ref "E119")
      (value "74173N")
      (footprint "eagle-import:DIL16")
      (libsource (lib "eagle-import") (part "74173NLS"))
    )
    (comp (ref "E120")
      (value "74S139N")
      (footprint "eagle-import:DIL16")
      (libsource (lib "eagle-import") (part "74139NS"))
    )
    (comp (ref "E121")
      (value "74173N")
      (footprint "eagle-import:DIL16")
      (libsource (lib "eagle-import") (part "74173NLS"))
    )
    (comp (ref "E122")
      (value "74173N")
      (footprint "eagle-import:DIL16")
      (libsource (lib "eagle-import") (part "74173NLS"))
    )
    (comp (ref "J1")
      (value "Header")
      (footprint "eagle-import:10H")
      (libsource (lib "eagle-import") (part "10H"))
    )
    (comp (ref "R11")
      (value "10K")
      (footprint "eagle-import:0207_10")
      (libsource (lib "eagle-import") (part "R-US_0207/10"))
    )
    (comp (ref "R13")
      (value "10K")
      (footprint "eagle-import:0207_10")
      (libsource (lib "eagle-import") (part "R-US_0207/10"))
    )
    (comp (ref "R37")
      (value "10K")
      (footprint "eagle-import:0207_10")
      (libsource (lib "eagle-import") (part "R-US_0207/10"))
    )
    (comp (ref "R38")
      (value "10K")
      (footprint "eagle-import:0207_10")
      (libsource (lib "eagle-import") (part "R-US_0207/10"))
    )
    (comp (ref "R39")
      (value "10K")
      (footprint "eagle-import:0207_10")
      (libsource (lib "eagle-import") (part "R-US_0207/10"))
    )
    (comp (ref "E29")
      (value "74LS02N")
      (footprint "eagle-import:DIL14")
      (libsource (lib "eagle-import") (part "7402NLS"))
    )
    (comp (ref "E33")
      (value "74LS08N")
      (footprint "eagle-import:DIL14")
      (libsource (lib "eagle-import") (part "7408NLS"))
    )
    (comp (ref "E47")
      (value "74LS02N")
      (footprint "eagle-import:DIL14")
      (libsource (lib "eagle-import") (part "7402NLS"))
    )
    (comp (ref "E68")
      (value "74LS85N")
      (footprint "eagle-import:DIL16")
      (libsource (lib "eagle-import") (part "7485NLS"))
    )
    (comp (ref "E78")
      (value "74LS85N")
      (footprint "eagle-import:DIL16")
      (libsource (lib "eagle-import") (part "7485NLS"))
    )
    (comp (ref "E85")
      (value "74LS174N")
      (footprint "eagle-import:DIL16")
      (libsource (lib "eagle-import") (part "74174NLS"))
    )
    (comp (ref "E86")
      (value "74368N")
      (footprint "eagle-import:DIL16")
      (libsource (lib "eagle-import") (part "74368N"))
    )
    (comp (ref "E87")
      (value "DEC23442A2")
      (footprint "eagle-import:DIL16")
      (libsource (lib "eagle-import") (part "74S287"))
    )
    (comp (ref "E88")
      (value "74LS174N")
      (footprint "eagle-import:DIL16")
      (libsource (lib "eagle-import") (part "74174NLS"))
    )
    (comp (ref "E106")
      (value "74368N")
      (footprint "eagle-import:DIL16")
      (libsource (lib "eagle-import") (part "74368N"))
    )
    (comp (ref "E112")
      (value "DEC23621A9")
      (footprint "eagle-import:DIL16")
      (libsource (lib "eagle-import") (part "74S571"))
    )
    (comp (ref "E113")
      (value "DEC23442A2")
      (footprint "eagle-import:DIL16")
      (libsource (lib "eagle-import") (part "74S287"))
    )
    (comp (ref "E114")
      (value "DEC23621A9")
      (footprint "eagle-import:DIL16")
      (libsource (lib "eagle-import") (part "74S571"))
    )
    (comp (ref "R21")
      (value "10K")
      (footprint "eagle-import:0207_10")
      (libsource (lib "eagle-import") (part "R-US_0207/10"))
    )
    (comp (ref "E5")
      (value "74LS04N")
      (footprint "eagle-import:DIL14")
      (libsource (lib "eagle-import") (part "7404NLS"))
    )
    (comp (ref "E7")
      (value "74LS04N")
      (footprint "eagle-import:DIL14")
      (libsource (lib "eagle-import") (part "7404NLS"))
    )
    (comp (ref "E9")
      (value "74LS20N")
      (footprint "eagle-import:DIL14")
      (libsource (lib "eagle-import") (part "7420NLS"))
    )
    (comp (ref "E11")
      (value "DS8640N")
      (footprint "eagle-import:DIL14")
      (libsource (lib "eagle-import") (part "DS8640N"))
    )
    (comp (ref "E12")
      (value "DS8641N")
      (footprint "eagle-import:DIL16")
      (libsource (lib "eagle-import") (part "DS8641N"))
    )
    (comp (ref "E13")
      (value "DS8641N")
      (footprint "eagle-import:DIL16")
      (libsource (lib "eagle-import") (part "DS8641N"))
    )
    (comp (ref "E14")
      (value "DEC23007C6")
      (footprint "eagle-import:DIL28")
      (libsource (lib "eagle-import") (part "82S100"))
    )
    (comp (ref "E15")
      (value "74LS174N")
      (footprint "eagle-import:DIL16")
      (libsource (lib "eagle-import") (part "74174NLS"))
    )
    (comp (ref "E16")
      (value "DEC23008C6")
      (footprint "eagle-import:DIL28")
      (libsource (lib "eagle-import") (part "82S100"))
    )
    (comp (ref "E17")
      (value "74LS174N")
      (footprint "eagle-import:DIL16")
      (libsource (lib "eagle-import") (part "74174NLS"))
    )
    (comp (ref "E19")
      (value "N8881N")
      (footprint "eagle-import:DIL14")
      (libsource (lib "eagle-import") (part "N8881N"))
    )
    (comp (ref "E20")
      (value "74LS01N")
      (footprint "eagle-import:DIL14")
      (libsource (lib "eagle-import") (part "7401NLS"))
    )
    (comp (ref "E21")
      (value "74LS10N")
      (footprint "eagle-import:DIL14")
      (libsource (lib "eagle-import") (part "7410NLS"))
    )
    (comp (ref "E22")
      (value "74LS04N")
      (footprint "eagle-import:DIL14")
      (libsource (lib "eagle-import") (part "7404NLS"))
    )
    (comp (ref "E23")
      (value "74LS258N")
      (footprint "eagle-import:DIL16")
      (libsource (lib "eagle-import") (part "74258NLS"))
    )
    (comp (ref "E25")
      (value "DS8640N")
      (footprint "eagle-import:DIL14")
      (libsource (lib "eagle-import") (part "DS8640N"))
    )
    (comp (ref "E26")
      (value "74LS75N")
      (footprint "eagle-import:DIL16")
      (libsource (lib "eagle-import") (part "7475N"))
    )
    (comp (ref "E41")
      (value "DS8640N")
      (footprint "eagle-import:DIL14")
      (libsource (lib "eagle-import") (part "DS8640N"))
    )
    (comp (ref "E44")
      (value "74LS04N")
      (footprint "eagle-import:DIL14")
      (libsource (lib "eagle-import") (part "7404NLS"))
    )
    (comp (ref "E45")
      (value "DS8641N")
      (footprint "eagle-import:DIL16")
      (libsource (lib "eagle-import") (part "DS8641N"))
    )
    (comp (ref "E51")
      (value "DS8640N")
      (footprint "eagle-import:DIL14")
      (libsource (lib "eagle-import") (part "DS8640N"))
    )
    (comp (ref "E53")
      (value "SP384N")
      (footprint "eagle-import:DIL14")
      (libsource (lib "eagle-import") (part "SP384N"))
    )
    (comp (ref "E61")
      (value "DS8640N")
      (footprint "eagle-import:DIL14")
      (libsource (lib "eagle-import") (part "DS8640N"))
    )
    (comp (ref "E71")
      (value "DS8640N")
      (footprint "eagle-import:DIL14")
      (libsource (lib "eagle-import") (part "DS8640N"))
    )
    (comp (ref "R1")
      (value "1K")
      (footprint "eagle-import:0207_10")
      (libsource (lib "eagle-import") (part "R-US_0207/10"))
    )
    (comp (ref "R2")
      (value "1K")
      (footprint "eagle-import:0207_10")
      (libsource (lib "eagle-import") (part "R-US_0207/10"))
    )
    (comp (ref "R6")
      (value "1K")
      (footprint "eagle-import:0207_10")
      (libsource (lib "eagle-import") (part "R-US_0207/10"))
    )
    (comp (ref "R7")
      (value "1K")
      (footprint "eagle-import:0207_10")
      (libsource (lib "eagle-import") (part "R-US_0207/10"))
    )
    (comp (ref "R8")
      (value "1K")
      (footprint "eagle-import:0207_10")
      (libsource (lib "eagle-import") (part "R-US_0207/10"))
    )
    (comp (ref "R9")
      (value "1K")
      (footprint "eagle-import:0207_10")
      (libsource (lib "eagle-import") (part "R-US_0207/10"))
    )
    (comp (ref "R10")
      (value "1K")
      (footprint "eagle-import:0207_10")
      (libsource (lib "eagle-import") (part "R-US_0207/10"))
    )
    (comp (ref "R12")
      (value "1K")
      (footprint "eagle-import:0207_10")
      (libsource (lib "eagle-import") (part "R-US_0207/10"))
    )
    (comp (ref "R24")
      (value "1K")
      (footprint "eagle-import:0207_10")
      (libsource (lib "eagle-import") (part "R-US_0207/10"))
    )
    (comp (ref "R25")
      (value "1K")
      (footprint "eagle-import:0207_10")
      (libsource (lib "eagle-import") (part "R-US_0207/10"))
    )
    (comp (ref "R26")
      (value "1K")
      (footprint "eagle-import:0207_10")
      (libsource (lib "eagle-import") (part "R-US_0207/10"))
    )
    (comp (ref "R27")
      (value "1K")
      (footprint "eagle-import:0207_10")
      (libsource (lib "eagle-import") (part "R-US_0207/10"))
    )
    (comp (ref "R31")
      (value "1K")
      (footprint "eagle-import:0207_10")
      (libsource (lib "eagle-import") (part "R-US_0207/10"))
    )
    (comp (ref "E74")
      (value "DEC23441A2")
      (footprint "eagle-import:DIL16")
      (libsource (lib "eagle-import") (part "74S287"))
    )
    (comp (ref "E81")
      (value "DEC23009C6")
      (footprint "eagle-import:DIL28")
      (libsource (lib "eagle-import") (part "82S100"))
    )
    (comp (ref "E82")
      (value "74S189")
      (footprint "eagle-import:DIL16")
      (libsource (lib "eagle-import") (part "7489"))
    )
    (comp (ref "E89")
      (value "74148N")
      (footprint "eagle-import:DIL16")
      (libsource (lib "eagle-import") (part "74148N"))
    )
    (comp (ref "E90")
      (value "74173N")
      (footprint "eagle-import:DIL16")
      (libsource (lib "eagle-import") (part "74173NLS"))
    )
    (comp (ref "E91")
      (value "74367N")
      (footprint "eagle-import:DIL16")
      (libsource (lib "eagle-import") (part "74xx-us_74367N"))
    )
    (comp (ref "E100")
      (value "74368N")
      (footprint "eagle-import:DIL16")
      (libsource (lib "eagle-import") (part "74368N"))
    )
    (comp (ref "E108")
      (value "74LS175N")
      (footprint "eagle-import:DIL16")
      (libsource (lib "eagle-import") (part "74175NLS"))
    )
    (comp (ref "E109")
      (value "DEC23010C6")
      (footprint "eagle-import:DIL28")
      (libsource (lib "eagle-import") (part "82S100"))
    )
    (comp (ref "E110")
      (value "74LS175N")
      (footprint "eagle-import:DIL16")
      (libsource (lib "eagle-import") (part "74175NLS"))
    )
    (comp (ref "E111")
      (value "DEC23621A9")
      (footprint "eagle-import:DIL16")
      (libsource (lib "eagle-import") (part "74S571"))
    )
    (comp (ref "E116")
      (value "74LS175N")
      (footprint "eagle-import:DIL16")
      (libsource (lib "eagle-import") (part "74175NLS"))
    )
    (comp (ref "E117")
      (value "74LS175N")
      (footprint "eagle-import:DIL16")
      (libsource (lib "eagle-import") (part "74175NLS"))
    )
    (comp (ref "R22")
      (value "1K")
      (footprint "eagle-import:0207_10")
      (libsource (lib "eagle-import") (part "R-US_0207/10"))
    )
    (comp (ref "R23")
      (value "1K")
      (footprint "eagle-import:0207_10")
      (libsource (lib "eagle-import") (part "R-US_0207/10"))
    )
    (comp (ref "R36")
      (value "10K")
      (footprint "eagle-import:0207_10")
      (libsource (lib "eagle-import") (part "R-US_0207/10"))
    )
    (comp (ref "E10")
      (value "Spare")
      (footprint "eagle-import:SOCKET-16")
      (libsource (lib "eagle-import") (part "DIL16S"))
    )
    (comp (ref "E40")
      (value "Spare")
      (footprint "eagle-import:SOCKET-16")
      (libsource (lib "eagle-import") (part "DIL16S"))
    )
    (comp (ref "E43")
      (value "74LS20N")
      (footprint "eagle-import:DIL14")
      (libsource (lib "eagle-import") (part "7420NLS"))
    )
    (comp (ref "E57")
      (value "74LS00N")
      (footprint "eagle-import:DIL14")
      (libsource (lib "eagle-import") (part "7400NLS"))
    )
    (comp (ref "E66")
      (value "74LS00N")
      (footprint "eagle-import:DIL14")
      (libsource (lib "eagle-import") (part "7400NLS"))
    )
    (comp (ref "E75")
      (value "SP384N")
      (footprint "eagle-import:DIL14")
      (libsource (lib "eagle-import") (part "SP384N"))
    )
    (comp (ref "E77")
      (value "74S74N")
      (footprint "eagle-import:DIL14")
      (libsource (lib "eagle-import") (part "7474NS"))
    )
    (comp (ref "U$2")
      (value "OUTLINE-HEX")
      (footprint "eagle-import:HEX-HEIGHT")
      (libsource (lib "eagle-import") (part "OUTLINE-HEX"))
    )
    (comp (ref "C12")
      (value "100pF")
      (footprint "eagle-import:C063-025X075")
      (libsource (lib "eagle-import") (part "C-US"))
    )
    (comp (ref "D1")
      (value "1N5711")
      (footprint "eagle-import:DO35-10")
      (libsource (lib "eagle-import") (part "DIODE-DO35-10"))
    )
    (comp (ref "E18")
      (value "74LS00N")
      (footprint "eagle-import:DIL14")
      (libsource (lib "eagle-import") (part "7400NLS"))
    )
    (comp (ref "E24")
      (value "74LS10N")
      (footprint "eagle-import:DIL14")
      (libsource (lib "eagle-import") (part "7410NLS"))
    )
    (comp (ref "E28")
      (value "DEC23440A2")
      (footprint "eagle-import:DIL16")
      (libsource (lib "eagle-import") (part "74S287"))
    )
    (comp (ref "E30")
      (value "74LS30N")
      (footprint "eagle-import:DIL14")
      (libsource (lib "eagle-import") (part "7430NLS"))
    )
    (comp (ref "E31")
      (value "74154N")
      (footprint "eagle-import:DIL24-6")
      (libsource (lib "eagle-import") (part "74154N"))
    )
    (comp (ref "E32")
      (value "74S74N")
      (footprint "eagle-import:DIL14")
      (libsource (lib "eagle-import") (part "7474NS"))
    )
    (comp (ref "E34")
      (value "74LS42N")
      (footprint "eagle-import:DIL16")
      (libsource (lib "eagle-import") (part "7442NLS"))
    )
    (comp (ref "E36")
      (value "74LS20N")
      (footprint "eagle-import:DIL14")
      (libsource (lib "eagle-import") (part "7420NLS"))
    )
    (comp (ref "E42")
      (value "N8881N")
      (footprint "eagle-import:DIL14")
      (libsource (lib "eagle-import") (part "N8881N"))
    )
    (comp (ref "E49")
      (value "74LS10N")
      (footprint "eagle-import:DIL14")
      (libsource (lib "eagle-import") (part "7410NLS"))
    )
    (comp (ref "E69")
      (value "MC8266")
      (footprint "eagle-import:DIL16")
      (libsource (lib "eagle-import") (part "MC8266"))
    )
    (comp (ref "E70")
      (value "74LS00N")
      (footprint "eagle-import:DIL14")
      (libsource (lib "eagle-import") (part "7400NLS"))
    )
    (comp (ref "E76")
      (value "74LS74N")
      (footprint "eagle-import:DIL14")
      (libsource (lib "eagle-import") (part "7474NLS"))
    )
    (comp (ref "E79")
      (value "MC8266")
      (footprint "eagle-import:DIL16")
      (libsource (lib "eagle-import") (part "MC8266"))
    )
    (comp (ref "E80")
      (value "DEC23211A1")
      (footprint "eagle-import:DIL16")
      (libsource (lib "eagle-import") (part "74S288"))
    )
    (comp (ref "PAD1")
      (value "1,6/0,8")
      (footprint "eagle-import:1,6_0,8")
      (libsource (lib "eagle-import") (part "1,6/0,8"))
    )
    (comp (ref "PAD2")
      (value "1,6/0,8")
      (footprint "eagle-import:1,6_0,8")
      (libsource (lib "eagle-import") (part "1,6/0,8"))
    )
    (comp (ref "PAD3")
      (value "1,6/0,8")
      (footprint "eagle-import:1,6_0,8")
      (libsource (lib "eagle-import") (part "1,6/0,8"))
    )
    (comp (ref "Q1")
      (value "2N3009")
      (footprint "eagle-import:TO5")
      (libsource (lib "eagle-import") (part "-NPN-TO5"))
    )
    (comp (ref "R3")
      (value "1K")
      (footprint "eagle-import:0207_10")
      (libsource (lib "eagle-import") (part "R-US_0207/10"))
    )
    (comp (ref "R4")
      (value "10K")
      (footprint "eagle-import:0207_10")
      (libsource (lib "eagle-import") (part "R-US_0207/10"))
    )
    (comp (ref "R5")
      (value "470")
      (footprint "eagle-import:0207_10")
      (libsource (lib "eagle-import") (part "R-US_0207/10"))
    )
    (comp (ref "R14")
      (value "1K")
      (footprint "eagle-import:0207_10")
      (libsource (lib "eagle-import") (part "R-US_0207/10"))
    )
    (comp (ref "R16")
      (value "1K")
      (footprint "eagle-import:0207_10")
      (libsource (lib "eagle-import") (part "R-US_0207/10"))
    )
    (comp (ref "R17")
      (value "1K")
      (footprint "eagle-import:0207_10")
      (libsource (lib "eagle-import") (part "R-US_0207/10"))
    )
    (comp (ref "R18")
      (value "10K")
      (footprint "eagle-import:0207_10")
      (libsource (lib "eagle-import") (part "R-US_0207/10"))
    )
    (comp (ref "R19")
      (value "10K")
      (footprint "eagle-import:0207_10")
      (libsource (lib "eagle-import") (part "R-US_0207/10"))
    )
  )
  (nets
    (net (code "1") (name "+15V") (class "Default")
      (node (ref "U$1") (pin "DA2") (pinfunction "1_DA2") (pintype "bidirectional"))
    )
    (net (code "2") (name "GND") (class "Default")
      (node (ref "C1") (pin "-") (pinfunction "-_-") (pintype "passive"))
      (node (ref "C10") (pin "2") (pinfunction "2_2") (pintype "passive"))
      (node (ref "C11") (pin "2") (pinfunction "2_2") (pintype "passive"))
      (node (ref "C13") (pin "2") (pinfunction "2_2") (pintype "passive"))
      (node (ref "C14") (pin "-") (pinfunction "-_-") (pintype "passive"))
      (node (ref "C15") (pin "2") (pinfunction "2_2") (pintype "passive"))
      (node (ref "C16") (pin "-") (pinfunction "-_-") (pintype "passive"))
      (node (ref "C17") (pin "2") (pinfunction "2_2") (pintype "passive"))
      (node (ref "C18") (pin "2") (pinfunction "2_2") (pintype "passive"))
      (node (ref "C2") (pin "2") (pinfunction "2_2") (pintype "passive"))
      (node (ref "C20") (pin "2") (pinfunction "2_2") (pintype "passive"))
      (node (ref "C21") (pin "2") (pinfunction "2_2") (pintype "passive"))
      (node (ref "C22") (pin "2") (pinfunction "2_2") (pintype "passive"))
      (node (ref "C23") (pin "2") (pinfunction "2_2") (pintype "passive"))
      (node (ref "C24") (pin "-") (pinfunction "-_-") (pintype "passive"))
      (node (ref "C25") (pin "2") (pinfunction "2_2") (pintype "passive"))
      (node (ref "C26") (pin "2") (pinfunction "2_2") (pintype "passive"))
      (node (ref "C27") (pin "2") (pinfunction "2_2") (pintype "passive"))
      (node (ref "C28") (pin "2") (pinfunction "2_2") (pintype "passive"))
      (node (ref "C29") (pin "2") (pinfunction "2_2") (pintype "passive"))
      (node (ref "C3") (pin "2") (pinfunction "2_2") (pintype "passive"))
      (node (ref "C31") (pin "2") (pinfunction "2_2") (pintype "passive"))
      (node (ref "C32") (pin "2") (pinfunction "2_2") (pintype "passive"))
      (node (ref "C33") (pin "2") (pinfunction "2_2") (pintype "passive"))
      (node (ref "C34") (pin "2") (pinfunction "2_2") (pintype "passive"))
      (node (ref "C35") (pin "2") (pinfunction "2_2") (pintype "passive"))
      (node (ref "C36") (pin "2") (pinfunction "2_2") (pintype "passive"))
      (node (ref "C4") (pin "2") (pinfunction "2_2") (pintype "passive"))
      (node (ref "C5") (pin "2") (pinfunction "2_2") (pintype "passive"))
      (node (ref "C6") (pin "2") (pinfunction "2_2") (pintype "passive"))
      (node (ref "C7") (pin "2") (pinfunction "2_2") (pintype "passive"))
      (node (ref "C8") (pin "-") (pinfunction "-_-") (pintype "passive"))
      (node (ref "C9") (pin "2") (pinfunction "2_2") (pintype "passive"))
      (node (ref "E1") (pin "10") (pinfunction "G2_10") (pintype "input"))
      (node (ref "E1") (pin "9") (pinfunction "G1_9") (pintype "input"))
      (node (ref "E101") (pin "8") (pinfunction "-UB_8") (pintype "power_in"))
      (node (ref "E109") (pin "19") (pinfunction "~{CE}_19") (pintype "input"))
      (node (ref "E11") (pin "12") (pinfunction "I1_12") (pintype "input"))
      (node (ref "E11") (pin "5") (pinfunction "I1_5") (pintype "input"))
      (node (ref "E11") (pin "6") (pinfunction "I0_6") (pintype "input"))
      (node (ref "E11") (pin "9") (pinfunction "I0_9") (pintype "input"))
      (node (ref "E113") (pin "13") (pinfunction "~{G1}_13") (pintype "input"))
      (node (ref "E113") (pin "14") (pinfunction "~{G2}_14") (pintype "input"))
      (node (ref "E113") (pin "2") (pinfunction "A5_2") (pintype "input"))
      (node (ref "E113") (pin "7") (pinfunction "A2_7") (pintype "input"))
      (node (ref "E118") (pin "10") (pinfunction "G2_10") (pintype "input"))
      (node (ref "E118") (pin "15") (pinfunction "CLR_15") (pintype "input"))
      (node (ref "E118") (pin "9") (pinfunction "G1_9") (pintype "input"))
      (node (ref "E119") (pin "10") (pinfunction "G2_10") (pintype "input"))
      (node (ref "E119") (pin "15") (pinfunction "CLR_15") (pintype "input"))
      (node (ref "E119") (pin "9") (pinfunction "G1_9") (pintype "input"))
      (node (ref "E120") (pin "1") (pinfunction "G_1") (pintype "input"))
      (node (ref "E120") (pin "15") (pinfunction "G_15") (pintype "input"))
      (node (ref "E121") (pin "10") (pinfunction "G2_10") (pintype "input"))
      (node (ref "E121") (pin "9") (pinfunction "G1_9") (pintype "input"))
      (node (ref "E122") (pin "10") (pinfunction "G2_10") (pintype "input"))
      (node (ref "E122") (pin "15") (pinfunction "CLR_15") (pintype "input"))
      (node (ref "E122") (pin "9") (pinfunction "G1_9") (pintype "input"))
      (node (ref "E14") (pin "19") (pinfunction "~{CE}_19") (pintype "input"))
      (node (ref "E25") (pin "12") (pinfunction "I1_12") (pintype "input"))
      (node (ref "E25") (pin "5") (pinfunction "I1_5") (pintype "input"))
      (node (ref "E25") (pin "6") (pinfunction "I0_6") (pintype "input"))
      (node (ref "E25") (pin "9") (pinfunction "I0_9") (pintype "input"))
      (node (ref "E26") (pin "12") (pinfunction "-UB_12") (pintype "power_in"))
      (node (ref "E3") (pin "11") (pinfunction "I0_11") (pintype "input"))
      (node (ref "E3") (pin "5") (pinfunction "I1_5") (pintype "input"))
      (node (ref "E3") (pin "6") (pinfunction "I0_6") (pintype "input"))
      (node (ref "E32") (pin "3") (pinfunction "CLK_3") (pintype "input"))
      (node (ref "E41") (pin "5") (pinfunction "I1_5") (pintype "input"))
      (node (ref "E41") (pin "6") (pinfunction "I0_6") (pintype "input"))
      (node (ref "E51") (pin "11") (pinfunction "I0_11") (pintype "input"))
      (node (ref "E51") (pin "5") (pinfunction "I1_5") (pintype "input"))
      (node (ref "E51") (pin "6") (pinfunction "I0_6") (pintype "input"))
      (node (ref "E52") (pin "10") (pinfunction "I1_10") (pintype "input"))
      (node (ref "E52") (pin "11") (pinfunction "I0_11") (pintype "input"))
      (node (ref "E52") (pin "5") (pinfunction "I1_5") (pintype "input"))
      (node (ref "E52") (pin "7") (pinfunction "I1_7") (pintype "input"))
      (node (ref "E53") (pin "12") (pinfunction "I1_12") (pintype "input"))
      (node (ref "E53") (pin "4") (pinfunction "I0_4") (pintype "input"))
      (node (ref "E53") (pin "6") (pinfunction "I0_6") (pintype "input"))
      (node (ref "E53") (pin "9") (pinfunction "I0_9") (pintype "input"))
      (node (ref "E55") (pin "10") (pinfunction "1A4_10") (pintype "input"))
      (node (ref "E55") (pin "2") (pinfunction "1A1_2") (pintype "input"))
      (node (ref "E55") (pin "4") (pinfunction "1A2_4") (pintype "input"))
      (node (ref "E55") (pin "6") (pinfunction "1A3_6") (pintype "input"))
      (node (ref "E60") (pin "11") (pinfunction "CLK_11") (pintype "input"))
      (node (ref "E60") (pin "12") (pinfunction "D_12") (pintype "input"))
      (node (ref "E61") (pin "4") (pinfunction "I0_4") (pintype "input"))
      (node (ref "E62") (pin "10") (pinfunction "G2_10") (pintype "input"))
      (node (ref "E62") (pin "9") (pinfunction "G1_9") (pintype "input"))
      (node (ref "E65") (pin "11") (pinfunction "CLK_11") (pintype "input"))
      (node (ref "E65") (pin "12") (pinfunction "D_12") (pintype "input"))
      (node (ref "E65") (pin "2") (pinfunction "D_2") (pintype "input"))
      (node (ref "E68") (pin "1") (pinfunction "B3_1") (pintype "input"))
      (node (ref "E68") (pin "12") (pinfunction "A1_12") (pintype "input"))
      (node (ref "E68") (pin "13") (pinfunction "A2_13") (pintype "input"))
      (node (ref "E68") (pin "14") (pinfunction "B2_14") (pintype "input"))
      (node (ref "E68") (pin "15") (pinfunction "A3_15") (pintype "input"))
      (node (ref "E69") (pin "11") (pinfunction "B2_11") (pintype "input"))
      (node (ref "E69") (pin "2") (pinfunction "B0_2") (pintype "input"))
      (node (ref "E69") (pin "5") (pinfunction "B1_5") (pintype "input"))
      (node (ref "E69") (pin "7") (pinfunction "S1_7") (pintype "input"))
      (node (ref "E71") (pin "12") (pinfunction "I1_12") (pintype "input"))
      (node (ref "E71") (pin "5") (pinfunction "I1_5") (pintype "input"))
      (node (ref "E71") (pin "6") (pinfunction "I0_6") (pintype "input"))
      (node (ref "E71") (pin "9") (pinfunction "I0_9") (pintype "input"))
      (node (ref "E72") (pin "4") (pinfunction "I0_4") (pintype "input"))
      (node (ref "E72") (pin "6") (pinfunction "I0_6") (pintype "input"))
      (node (ref "E73") (pin "10") (pinfunction "G2_10") (pintype "input"))
      (node (ref "E73") (pin "9") (pinfunction "G1_9") (pintype "input"))
      (node (ref "E74") (pin "13") (pinfunction "~{G1}_13") (pintype "input"))
      (node (ref "E74") (pin "14") (pinfunction "~{G2}_14") (pintype "input"))
      (node (ref "E76") (pin "2") (pinfunction "D_2") (pintype "input"))
      (node (ref "E77") (pin "2") (pinfunction "D_2") (pintype "input"))
      (node (ref "E77") (pin "3") (pinfunction "CLK_3") (pintype "input"))
      (node (ref "E78") (pin "2") (pinfunction "A<B_I_2") (pintype "input"))
      (node (ref "E78") (pin "4") (pinfunction "A>B_I_4") (pintype "input"))
      (node (ref "E79") (pin "7") (pinfunction "S1_7") (pintype "input"))
      (node (ref "E80") (pin "15") (pinfunction "~{G}_15") (pintype "input"))
      (node (ref "E81") (pin "19") (pinfunction "~{CE}_19") (pintype "input"))
      (node (ref "E81") (pin "20") (pinfunction "I15_20") (pintype "input"))
      (node (ref "E83") (pin "8") (pinfunction "-UB_8") (pintype "power_in"))
      (node (ref "E87") (pin "1") (pinfunction "A6_1") (pintype "input"))
      (node (ref "E87") (pin "13") (pinfunction "~{G1}_13") (pintype "input"))
      (node (ref "E87") (pin "14") (pinfunction "~{G2}_14") (pintype "input"))
      (node (ref "E89") (pin "10") (pinfunction "0_10") (pintype "input"))
      (node (ref "E89") (pin "5") (pinfunction "EI_5") (pintype "input"))
      (node (ref "E98") (pin "10") (pinfunction "G2_10") (pintype "input"))
      (node (ref "E98") (pin "9") (pinfunction "G1_9") (pintype "input"))
      (node (ref "E99") (pin "10") (pinfunction "G2_10") (pintype "input"))
      (node (ref "E99") (pin "9") (pinfunction "G1_9") (pintype "input"))
      (node (ref "J1") (pin "10") (pinfunction "10_10") (pintype "passive"))
      (node (ref "J1") (pin "2") (pinfunction "2_2") (pintype "passive"))
      (node (ref "J1") (pin "4") (pinfunction "4_4") (pintype "passive"))
      (node (ref "J1") (pin "6") (pinfunction "6_6") (pintype "passive"))
      (node (ref "J1") (pin "8") (pinfunction "8_8") (pintype "passive"))
      (node (ref "J1") (pin "9") (pinfunction "9_9") (pintype "passive"))
      (node (ref "Q1") (pin "1") (pinfunction "E_1") (pintype "passive"))
      (node (ref "U$1") (pin "AC1") (pinfunction "1_AC1") (pintype "bidirectional"))
      (node (ref "U$1") (pin "AC2") (pinfunction "1_AC2") (pintype "bidirectional"))
      (node (ref "U$1") (pin "AF1") (pinfunction "1_AF1") (pintype "bidirectional"))
      (node (ref "U$1") (pin "AF2") (pinfunction "1_AF2") (pintype "bidirectional"))
      (node (ref "U$1") (pin "AN1") (pinfunction "1_AN1") (pintype "bidirectional"))
      (node (ref "U$1") (pin "AN2") (pinfunction "1_AN2") (pintype "bidirectional"))
      (node (ref "U$1") (pin "AT1") (pinfunction "1_AT1") (pintype "bidirectional"))
      (node (ref "U$1") (pin "AT2") (pinfunction "1_AT2") (pintype "bidirectional"))
      (node (ref "U$1") (pin "BC1") (pinfunction "1_BC1") (pintype "bidirectional"))
      (node (ref "U$1") (pin "BC2") (pinfunction "1_BC2") (pintype "bidirectional"))
      (node (ref "U$1") (pin "BF1") (pinfunction "1_BF1") (pintype "bidirectional"))
      (node (ref "U$1") (pin "BF2") (pinfunction "1_BF2") (pintype "bidirectional"))
      (node (ref "U$1") (pin "BN1") (pinfunction "1_BN1") (pintype "bidirectional"))
      (node (ref "U$1") (pin "BN2") (pinfunction "1_BN2") (pintype "bidirectional"))
      (node (ref "U$1") (pin "BT1") (pinfunction "1_BT1") (pintype "bidirectional"))
      (node (ref "U$1") (pin "BT2") (pinfunction "1_BT2") (pintype "bidirectional"))
      (node (ref "U$1") (pin "CC1") (pinfunction "1_CC1") (pintype "bidirectional"))
      (node (ref "U$1") (pin "CC2") (pinfunction "1_CC2") (pintype "bidirectional"))
      (node (ref "U$1") (pin "CF1") (pinfunction "1_CF1") (pintype "bidirectional"))
      (node (ref "U$1") (pin "CF2") (pinfunction "1_CF2") (pintype "bidirectional"))
      (node (ref "U$1") (pin "CN1") (pinfunction "1_CN1") (pintype "bidirectional"))
      (node (ref "U$1") (pin "CN2") (pinfunction "1_CN2") (pintype "bidirectional"))
      (node (ref "U$1") (pin "CT1") (pinfunction "1_CT1") (pintype "bidirectional"))
      (node (ref "U$1") (pin "CT2") (pinfunction "1_CT2") (pintype "bidirectional"))
      (node (ref "U$1") (pin "DC1") (pinfunction "1_DC1") (pintype "bidirectional"))
      (node (ref "U$1") (pin "DC2") (pinfunction "1_DC2") (pintype "bidirectional"))
      (node (ref "U$1") (pin "DF1") (pinfunction "1_DF1") (pintype "bidirectional"))
      (node (ref "U$1") (pin "DF2") (pinfunction "1_DF2") (pintype "bidirectional"))
      (node (ref "U$1") (pin "DN1") (pinfunction "1_DN1") (pintype "bidirectional"))
      (node (ref "U$1") (pin "DN2") (pinfunction "1_DN2") (pintype "bidirectional"))
      (node (ref "U$1") (pin "DT1") (pinfunction "1_DT1") (pintype "bidirectional"))
      (node (ref "U$1") (pin "DT2") (pinfunction "1_DT2") (pintype "bidirectional"))
    )
    (net (code "3") (name "IBB_0") (class "Default")
      (node (ref "E109") (pin "27") (pinfunction "I8_27") (pintype "input"))
      (node (ref "E116") (pin "15") (pinfunction "Q4_15") (pintype "output"))
    )
    (net (code "4") (name "IBB_1") (class "Default")
      (node (ref "E109") (pin "2") (pinfunction "I7_2") (pintype "input"))
      (node (ref "E116") (pin "10") (pinfunction "Q3_10") (pintype "output"))
    )
    (net (code "5") (name "INITIALIZE") (class "Default")
      (node (ref "E53") (pin "11") (pinfunction "I0_11") (pintype "input"))
      (node (ref "U$1") (pin "CR1") (pinfunction "1_CR1") (pintype "bidirectional"))
    )
    (net (code "6") (name "INTERNAL_IO") (class "Default")
      (node (ref "E42") (pin "10") (pinfunction "O_10") (pintype "open_collector"))
      (node (ref "U$1") (pin "CL1") (pinfunction "1_CL1") (pintype "bidirectional"))
    )
    (net (code "7") (name "LBM+RBMN") (class "Default")
      (node (ref "E74") (pin "5") (pinfunction "A0_5") (pintype "input"))
      (node (ref "E81") (pin "17") (pinfunction "O1_17") (pintype "tri_state"))
    )
    (net (code "8") (name "MAMS_LD_CTL") (class "Default")
      (node (ref "E3") (pin "4") (pinfunction "I0_4") (pintype "input"))
      (node (ref "U$1") (pin "BH2") (pinfunction "1_BH2") (pintype "bidirectional"))
    )
    (net (code "9") (name "MUX_C0") (class "Default")
      (node (ref "E109") (pin "20") (pinfunction "I15_20") (pintype "input"))
      (node (ref "E89") (pin "6") (pinfunction "A2_6") (pintype "output"))
    )
    (net (code "10") (name "MUX_C1") (class "Default")
      (node (ref "E109") (pin "21") (pinfunction "I14_21") (pintype "input"))
      (node (ref "E89") (pin "7") (pinfunction "A1_7") (pintype "output"))
    )
    (net (code "11") (name "MUX_C2") (class "Default")
      (node (ref "E109") (pin "22") (pinfunction "I13_22") (pintype "input"))
      (node (ref "E89") (pin "9") (pinfunction "A0_9") (pintype "output"))
    )
    (net (code "12") (name "Net-(E1A-D2)") (class "Default")
      (node (ref "E1") (pin "13") (pinfunction "D2_13") (pintype "input"))
      (node (ref "E2") (pin "6") (pinfunction "O_6") (pintype "output"))
    )
    (net (code "13") (name "Net-(E1A-D3)") (class "Default")
      (node (ref "E1") (pin "12") (pinfunction "D3_12") (pintype "input"))
      (node (ref "E2") (pin "4") (pinfunction "O_4") (pintype "output"))
    )
    (net (code "14") (name "Net-(E1A-D4)") (class "Default")
      (node (ref "E1") (pin "11") (pinfunction "D4_11") (pintype "input"))
      (node (ref "E2") (pin "2") (pinfunction "O_2") (pintype "output"))
    )
    (net (code "15") (name "Net-(E2D-I)") (class "Default")
      (node (ref "E2") (pin "9") (pinfunction "I_9") (pintype "input"))
      (node (ref "E33") (pin "6") (pinfunction "O_6") (pintype "output"))
    )
    (net (code "16") (name "Net-(E2D-O)") (class "Default")
      (node (ref "E2") (pin "8") (pinfunction "O_8") (pintype "output"))
      (node (ref "E32") (pin "12") (pinfunction "D_12") (pintype "input"))
    )
    (net (code "17") (name "Net-(E3D-O)") (class "Default")
      (node (ref "E3") (pin "13") (pinfunction "O_13") (pintype "output"))
      (node (ref "E4") (pin "8") (pinfunction "I0_8") (pintype "input"))
    )
    (net (code "18") (name "Net-(E4C-I1)") (class "Default")
      (node (ref "E4") (pin "9") (pinfunction "I1_9") (pintype "input"))
      (node (ref "E6") (pin "11") (pinfunction "O_11") (pintype "output"))
    )
    (net (code "19") (name "Net-(E12A-D0)") (class "Default")
      (node (ref "E12") (pin "7") (pinfunction "D0_7") (pintype "input"))
      (node (ref "E12") (pin "9") (pinfunction "D1_9") (pintype "input"))
      (node (ref "E13") (pin "7") (pinfunction "D0_7") (pintype "input"))
      (node (ref "E13") (pin "9") (pinfunction "D1_9") (pintype "input"))
      (node (ref "E20") (pin "1") (pinfunction "O_1") (pintype "open_collector"))
      (node (ref "E20") (pin "13") (pinfunction "O_13") (pintype "open_collector"))
      (node (ref "E20") (pin "4") (pinfunction "O_4") (pintype "open_collector"))
      (node (ref "E45") (pin "7") (pinfunction "D0_7") (pintype "input"))
      (node (ref "E45") (pin "9") (pinfunction "D1_9") (pintype "input"))
      (node (ref "R10") (pin "1") (pinfunction "1_1") (pintype "passive"))
    )
    (net (code "20") (name "Net-(E12A-O0)") (class "Default")
      (node (ref "E12") (pin "14") (pinfunction "O0_14") (pintype "input"))
      (node (ref "E5") (pin "8") (pinfunction "O_8") (pintype "output"))
    )
    (net (code "21") (name "Net-(E12A-O1)") (class "Default")
      (node (ref "E12") (pin "11") (pinfunction "O1_11") (pintype "input"))
      (node (ref "E5") (pin "6") (pinfunction "O_6") (pintype "output"))
    )
    (net (code "22") (name "Net-(E12A-O2)") (class "Default")
      (node (ref "E12") (pin "2") (pinfunction "O2_2") (pintype "input"))
      (node (ref "E5") (pin "4") (pinfunction "O_4") (pintype "output"))
    )
    (net (code "23") (name "Net-(E12A-O3)") (class "Default")
      (node (ref "E12") (pin "5") (pinfunction "O3_5") (pintype "input"))
      (node (ref "E5") (pin "2") (pinfunction "O_2") (pintype "output"))
    )
    (net (code "24") (name "Net-(E13A-O0)") (class "Default")
      (node (ref "E13") (pin "14") (pinfunction "O0_14") (pintype "input"))
      (node (ref "E7") (pin "8") (pinfunction "O_8") (pintype "output"))
    )
    (net (code "25") (name "Net-(E13A-O1)") (class "Default")
      (node (ref "E13") (pin "11") (pinfunction "O1_11") (pintype "input"))
      (node (ref "E7") (pin "6") (pinfunction "O_6") (pintype "output"))
    )
    (net (code "26") (name "Net-(E13A-O2)") (class "Default")
      (node (ref "E13") (pin "2") (pinfunction "O2_2") (pintype "input"))
      (node (ref "E7") (pin "4") (pinfunction "O_4") (pintype "output"))
    )
    (net (code "27") (name "Net-(E13A-O3)") (class "Default")
      (node (ref "E13") (pin "5") (pinfunction "O3_5") (pintype "input"))
      (node (ref "E7") (pin "2") (pinfunction "O_2") (pintype "output"))
    )
    (net (code "28") (name "Net-(E14A-I15)") (class "Default")
      (node (ref "E14") (pin "20") (pinfunction "I15_20") (pintype "input"))
      (node (ref "E21") (pin "12") (pinfunction "O_12") (pintype "output"))
    )
    (net (code "29") (name "Net-(E14A-O0)") (class "Default")
      (node (ref "E14") (pin "18") (pinfunction "O0_18") (pintype "tri_state"))
      (node (ref "E20") (pin "11") (pinfunction "I0_11") (pintype "input"))
    )
    (net (code "30") (name "Net-(E14A-O1)") (class "Default")
      (node (ref "E14") (pin "17") (pinfunction "O1_17") (pintype "tri_state"))
      (node (ref "E19") (pin "8") (pinfunction "I0_8") (pintype "input"))
      (node (ref "E19") (pin "9") (pinfunction "I1_9") (pintype "input"))
    )
    (net (code "31") (name "Net-(E14A-O2)") (class "Default")
      (node (ref "E14") (pin "16") (pinfunction "O2_16") (pintype "tri_state"))
      (node (ref "E19") (pin "11") (pinfunction "I0_11") (pintype "input"))
      (node (ref "E19") (pin "12") (pinfunction "I1_12") (pintype "input"))
    )
    (net (code "32") (name "Net-(E15A-Q1)") (class "Default")
      (node (ref "E15") (pin "2") (pinfunction "Q1_2") (pintype "output"))
      (node (ref "E16") (pin "26") (pinfunction "I9_26") (pintype "input"))
    )
    (net (code "33") (name "Net-(E15A-Q2)") (class "Default")
      (node (ref "E15") (pin "5") (pinfunction "Q2_5") (pintype "output"))
      (node (ref "E16") (pin "27") (pinfunction "I8_27") (pintype "input"))
      (node (ref "E23") (pin "11") (pinfunction "3A_11") (pintype "input"))
    )
    (net (code "34") (name "Net-(E15A-Q3)") (class "Default")
      (node (ref "E15") (pin "7") (pinfunction "Q3_7") (pintype "output"))
      (node (ref "E16") (pin "2") (pinfunction "I7_2") (pintype "input"))
      (node (ref "E23") (pin "14") (pinfunction "4A_14") (pintype "input"))
    )
    (net (code "35") (name "Net-(E15A-Q4)") (class "Default")
      (node (ref "E15") (pin "10") (pinfunction "Q4_10") (pintype "output"))
      (node (ref "E16") (pin "3") (pinfunction "I6_3") (pintype "input"))
      (node (ref "E23") (pin "5") (pinfunction "2A_5") (pintype "input"))
    )
    (net (code "36") (name "Net-(E15A-Q5)") (class "Default")
      (node (ref "E15") (pin "12") (pinfunction "Q5_12") (pintype "output"))
      (node (ref "E16") (pin "4") (pinfunction "I5_4") (pintype "input"))
      (node (ref "E23") (pin "10") (pinfunction "3B_10") (pintype "input"))
    )
    (net (code "37") (name "Net-(E15A-Q6)") (class "Default")
      (node (ref "E15") (pin "15") (pinfunction "Q6_15") (pintype "output"))
      (node (ref "E16") (pin "5") (pinfunction "I4_5") (pintype "input"))
      (node (ref "E23") (pin "13") (pinfunction "4B_13") (pintype "input"))
    )
    (net (code "38") (name "Net-(E16A-I10)") (class "Default")
      (node (ref "E16") (pin "25") (pinfunction "I10_25") (pintype "input"))
      (node (ref "E17") (pin "15") (pinfunction "Q6_15") (pintype "output"))
      (node (ref "E23") (pin "2") (pinfunction "1A_2") (pintype "input"))
    )
    (net (code "39") (name "Net-(E16A-I11)") (class "Default")
      (node (ref "E16") (pin "24") (pinfunction "I11_24") (pintype "input"))
      (node (ref "E17") (pin "12") (pinfunction "Q5_12") (pintype "output"))
      (node (ref "E23") (pin "6") (pinfunction "2B_6") (pintype "input"))
    )
    (net (code "40") (name "Net-(E16A-I12)") (class "Default")
      (node (ref "E16") (pin "23") (pinfunction "I12_23") (pintype "input"))
      (node (ref "E17") (pin "10") (pinfunction "Q4_10") (pintype "output"))
      (node (ref "E23") (pin "3") (pinfunction "1B_3") (pintype "input"))
    )
    (net (code "41") (name "Net-(E16A-I13)") (class "Default")
      (node (ref "E16") (pin "22") (pinfunction "I13_22") (pintype "input"))
      (node (ref "E17") (pin "7") (pinfunction "Q3_7") (pintype "output"))
    )
    (net (code "42") (name "Net-(E16A-I14)") (class "Default")
      (node (ref "E16") (pin "21") (pinfunction "I14_21") (pintype "input"))
      (node (ref "E17") (pin "5") (pinfunction "Q2_5") (pintype "output"))
    )
    (net (code "43") (name "Net-(E16A-I15)") (class "Default")
      (node (ref "E16") (pin "20") (pinfunction "I15_20") (pintype "input"))
      (node (ref "E17") (pin "2") (pinfunction "Q1_2") (pintype "output"))
    )
    (net (code "44") (name "Net-(E16A-~{CE})") (class "Default")
      (node (ref "E16") (pin "19") (pinfunction "~{CE}_19") (pintype "input"))
      (node (ref "E22") (pin "8") (pinfunction "O_8") (pintype "output"))
    )
    (net (code "45") (name "Net-(E18A-O)") (class "Default")
      (node (ref "E18") (pin "3") (pinfunction "O_3") (pintype "output"))
      (node (ref "E56") (pin "9") (pinfunction "I0_9") (pintype "input"))
    )
    (net (code "46") (name "Net-(E18B-I1)") (class "Default")
      (node (ref "E18") (pin "5") (pinfunction "I1_5") (pintype "input"))
      (node (ref "E22") (pin "10") (pinfunction "O_10") (pintype "output"))
    )
    (net (code "47") (name "Net-(E18B-O)") (class "Default")
      (node (ref "E18") (pin "6") (pinfunction "O_6") (pintype "output"))
      (node (ref "E33") (pin "10") (pinfunction "I1_10") (pintype "input"))
      (node (ref "E56") (pin "10") (pinfunction "I1_10") (pintype "input"))
    )
    (net (code "48") (name "Net-(E18C-O)") (class "Default")
      (node (ref "E18") (pin "8") (pinfunction "O_8") (pintype "output"))
      (node (ref "E24") (pin "5") (pinfunction "I2_5") (pintype "input"))
    )
    (net (code "49") (name "Net-(E18D-O)") (class "Default")
      (node (ref "E18") (pin "11") (pinfunction "O_11") (pintype "output"))
      (node (ref "E8") (pin "12") (pinfunction "I1_12") (pintype "input"))
    )
    (net (code "50") (name "Net-(E21C-O)") (class "Default")
      (node (ref "E21") (pin "8") (pinfunction "O_8") (pintype "output"))
      (node (ref "E28") (pin "15") (pinfunction "A7_15") (pintype "input"))
    )
    (net (code "51") (name "Net-(E22C-O)") (class "Default")
      (node (ref "E22") (pin "6") (pinfunction "O_6") (pintype "output"))
      (node (ref "E6") (pin "2") (pinfunction "I1_2") (pintype "input"))
    )
    (net (code "52") (name "Net-(E22D-I)") (class "Default")
      (node (ref "E22") (pin "9") (pinfunction "I_9") (pintype "input"))
      (node (ref "E9") (pin "6") (pinfunction "O_6") (pintype "output"))
    )
    (net (code "53") (name "Net-(E22F-O)") (class "Default")
      (node (ref "E22") (pin "12") (pinfunction "O_12") (pintype "output"))
      (node (ref "E42") (pin "6") (pinfunction "I1_6") (pintype "input"))
    )
    (net (code "54") (name "Net-(E23A-G)") (class "Default")
      (node (ref "E23") (pin "15") (pinfunction "G_15") (pintype "input"))
      (node (ref "E33") (pin "3") (pinfunction "O_3") (pintype "output"))
    )
    (net (code "55") (name "Net-(E24A-I0)") (class "Default")
      (node (ref "E24") (pin "1") (pinfunction "I0_1") (pintype "input"))
      (node (ref "E30") (pin "8") (pinfunction "O_8") (pintype "output"))
    )
    (net (code "56") (name "Net-(E24A-I2)") (class "Default")
      (node (ref "E24") (pin "13") (pinfunction "I2_13") (pintype "input"))
      (node (ref "E49") (pin "8") (pinfunction "O_8") (pintype "output"))
      (node (ref "E57") (pin "2") (pinfunction "I1_2") (pintype "input"))
      (node (ref "E67") (pin "9") (pinfunction "I0_9") (pintype "input"))
    )
    (net (code "57") (name "Net-(E24A-O)") (class "Default")
      (node (ref "E24") (pin "12") (pinfunction "O_12") (pintype "output"))
      (node (ref "E39") (pin "5") (pinfunction "I_5") (pintype "input"))
      (node (ref "E42") (pin "2") (pinfunction "I0_2") (pintype "input"))
      (node (ref "E42") (pin "3") (pinfunction "I1_3") (pintype "input"))
    )
    (net (code "58") (name "Net-(E24B-I0)") (class "Default")
      (node (ref "E24") (pin "3") (pinfunction "I0_3") (pintype "input"))
      (node (ref "E39") (pin "6") (pinfunction "O_6") (pintype "output"))
    )
    (net (code "59") (name "Net-(E24B-O)") (class "Default")
      (node (ref "E24") (pin "6") (pinfunction "O_6") (pintype "output"))
      (node (ref "E33") (pin "4") (pinfunction "I0_4") (pintype "input"))
    )
    (net (code "60") (name "Net-(E24C-I1)") (class "Default")
      (node (ref "E24") (pin "10") (pinfunction "I1_10") (pintype "input"))
      (node (ref "E39") (pin "8") (pinfunction "O_8") (pintype "output"))
    )
    (net (code "61") (name "Net-(E24C-O)") (class "Default")
      (node (ref "E24") (pin "8") (pinfunction "O_8") (pintype "output"))
      (node (ref "E42") (pin "8") (pinfunction "I0_8") (pintype "input"))
      (node (ref "E42") (pin "9") (pinfunction "I1_9") (pintype "input"))
    )
    (net (code "62") (name "Net-(E26C-2D)") (class "Default")
      (node (ref "E26") (pin "7") (pinfunction "2D_7") (pintype "input"))
      (node (ref "E29") (pin "10") (pinfunction "O_10") (pintype "output"))
    )
    (net (code "63") (name "Net-(E26D-1D)") (class "Default")
      (node (ref "E26") (pin "2") (pinfunction "1D_2") (pintype "input"))
      (node (ref "E41") (pin "3") (pinfunction "O_3") (pintype "output"))
    )
    (net (code "64") (name "Net-(E27B-O)") (class "Default")
      (node (ref "E27") (pin "6") (pinfunction "O_6") (pintype "output"))
      (node (ref "E8") (pin "5") (pinfunction "I0_5") (pintype "input"))
    )
    (net (code "65") (name "Net-(E27C-O)") (class "Default")
      (node (ref "E27") (pin "8") (pinfunction "O_8") (pintype "output"))
      (node (ref "E60") (pin "13") (pinfunction "CLR_13") (pintype "input"))
    )
    (net (code "66") (name "Net-(E28A-O1)") (class "Default")
      (node (ref "E28") (pin "11") (pinfunction "O1_11") (pintype "tri_state"))
      (node (ref "R3") (pin "1") (pinfunction "1_1") (pintype "passive"))
    )
    (net (code "67") (name "Net-(E29A-O)") (class "Default")
      (node (ref "E29") (pin "1") (pinfunction "O_1") (pintype "output"))
      (node (ref "E49") (pin "3") (pinfunction "I0_3") (pintype "input"))
    )
    (net (code "68") (name "Net-(E29B-I1)") (class "Default")
      (node (ref "E29") (pin "6") (pinfunction "I1_6") (pintype "input"))
      (node (ref "E3") (pin "3") (pinfunction "O_3") (pintype "output"))
      (node (ref "E75") (pin "6") (pinfunction "I0_6") (pintype "input"))
    )
    (net (code "69") (name "Net-(E29D-O)") (class "Default")
      (node (ref "E29") (pin "13") (pinfunction "O_13") (pintype "output"))
      (node (ref "E88") (pin "9") (pinfunction "CLK_9") (pintype "input"))
    )
    (net (code "70") (name "Net-(E31A-G2)") (class "Default")
      (node (ref "E31") (pin "19") (pinfunction "G2_19") (pintype "input"))
      (node (ref "E47") (pin "3") (pinfunction "I1_3") (pintype "input"))
      (node (ref "E47") (pin "4") (pinfunction "O_4") (pintype "output"))
    )
    (net (code "71") (name "Net-(E32A-~{Q})") (class "Default")
      (node (ref "E32") (pin "6") (pinfunction "~{Q}_6") (pintype "output"))
      (node (ref "E8") (pin "11") (pinfunction "I0_11") (pintype "input"))
    )
    (net (code "72") (name "Net-(E32B-CLR)") (class "Default")
      (node (ref "E32") (pin "13") (pinfunction "CLR_13") (pintype "input"))
      (node (ref "R4") (pin "1") (pinfunction "1_1") (pintype "passive"))
    )
    (net (code "73") (name "Net-(E33C-I0)") (class "Default")
      (node (ref "E33") (pin "9") (pinfunction "I0_9") (pintype "input"))
      (node (ref "E56") (pin "11") (pinfunction "I2_11") (pintype "input"))
      (node (ref "E58") (pin "12") (pinfunction "O_12") (pintype "output"))
      (node (ref "E76") (pin "10") (pinfunction "PRE_10") (pintype "input"))
    )
    (net (code "74") (name "Net-(E35A-CLK)") (class "Default")
      (node (ref "E35") (pin "9") (pinfunction "CLK_9") (pintype "input"))
      (node (ref "E46") (pin "9") (pinfunction "CLK_9") (pintype "input"))
      (node (ref "E48") (pin "4") (pinfunction "O_4") (pintype "output"))
    )
    (net (code "75") (name "Net-(E38C-O)") (class "Default")
      (node (ref "E38") (pin "8") (pinfunction "O_8") (pintype "output"))
      (node (ref "E48") (pin "12") (pinfunction "I1_12") (pintype "input"))
    )
    (net (code "76") (name "Net-(E39A-O)") (class "Default")
      (node (ref "E39") (pin "2") (pinfunction "O_2") (pintype "output"))
      (node (ref "E50") (pin "2") (pinfunction "I1_2") (pintype "input"))
    )
    (net (code "77") (name "Net-(E39B-O)") (class "Default")
      (node (ref "E39") (pin "4") (pinfunction "O_4") (pintype "output"))
      (node (ref "E50") (pin "13") (pinfunction "I1_13") (pintype "input"))
    )
    (net (code "78") (name "Net-(E39D-I)") (class "Default")
      (node (ref "E39") (pin "9") (pinfunction "I_9") (pintype "input"))
      (node (ref "E47") (pin "1") (pinfunction "O_1") (pintype "output"))
    )
    (net (code "79") (name "Net-(E39E-O)") (class "Default")
      (node (ref "E39") (pin "10") (pinfunction "O_10") (pintype "output"))
      (node (ref "E89") (pin "13") (pinfunction "3_13") (pintype "input"))
    )
    (net (code "80") (name "Net-(E39F-I)") (class "Default")
      (node (ref "E39") (pin "13") (pinfunction "I_13") (pintype "input"))
      (node (ref "E48") (pin "10") (pinfunction "O_10") (pintype "output"))
    )
    (net (code "81") (name "Net-(E41B-O)") (class "Default")
      (node (ref "E41") (pin "12") (pinfunction "I1_12") (pintype "input"))
      (node (ref "E41") (pin "2") (pinfunction "O_2") (pintype "output"))
    )
    (net (code "82") (name "Net-(E41C-O)") (class "Default")
      (node (ref "E41") (pin "14") (pinfunction "O_14") (pintype "output"))
      (node (ref "E66") (pin "5") (pinfunction "I1_5") (pintype "input"))
    )
    (net (code "83") (name "Net-(E44A-O)") (class "Default")
      (node (ref "E44") (pin "2") (pinfunction "O_2") (pintype "output"))
      (node (ref "E45") (pin "5") (pinfunction "O3_5") (pintype "input"))
    )
    (net (code "84") (name "Net-(E44B-O)") (class "Default")
      (node (ref "E44") (pin "4") (pinfunction "O_4") (pintype "output"))
      (node (ref "E45") (pin "2") (pinfunction "O2_2") (pintype "input"))
    )
    (net (code "85") (name "Net-(E44C-O)") (class "Default")
      (node (ref "E44") (pin "6") (pinfunction "O_6") (pintype "output"))
      (node (ref "E45") (pin "11") (pinfunction "O1_11") (pintype "input"))
    )
    (net (code "86") (name "Net-(E44D-O)") (class "Default")
      (node (ref "E44") (pin "8") (pinfunction "O_8") (pintype "output"))
      (node (ref "E45") (pin "14") (pinfunction "O0_14") (pintype "input"))
    )
    (net (code "87") (name "Net-(E47B-I1)") (class "Default")
      (node (ref "E47") (pin "10") (pinfunction "O_10") (pintype "output"))
      (node (ref "E47") (pin "6") (pinfunction "I1_6") (pintype "input"))
    )
    (net (code "88") (name "Net-(E47D-O)") (class "Default")
      (node (ref "E47") (pin "13") (pinfunction "O_13") (pintype "output"))
      (node (ref "E85") (pin "9") (pinfunction "CLK_9") (pintype "input"))
    )
    (net (code "89") (name "Net-(E48C-I0)") (class "Default")
      (node (ref "E48") (pin "8") (pinfunction "I0_8") (pintype "input"))
      (node (ref "E68") (pin "6") (pinfunction "A=B_O_6") (pintype "output"))
    )
    (net (code "90") (name "Net-(E48C-I1)") (class "Default")
      (node (ref "E48") (pin "9") (pinfunction "I1_9") (pintype "input"))
      (node (ref "E68") (pin "5") (pinfunction "A>B_O_5") (pintype "output"))
    )
    (net (code "91") (name "Net-(E48D-O)") (class "Default")
      (node (ref "E48") (pin "13") (pinfunction "O_13") (pintype "output"))
      (node (ref "E96") (pin "1") (pinfunction "1G_1") (pintype "input"))
      (node (ref "E96") (pin "15") (pinfunction "2G_15") (pintype "input"))
    )
    (net (code "92") (name "Net-(E49A-I0)") (class "Default")
      (node (ref "E49") (pin "1") (pinfunction "I0_1") (pintype "input"))
      (node (ref "E57") (pin "8") (pinfunction "O_8") (pintype "output"))
      (node (ref "E58") (pin "3") (pinfunction "I_3") (pintype "input"))
    )
    (net (code "93") (name "Net-(E49A-O)") (class "Default")
      (node (ref "E49") (pin "12") (pinfunction "O_12") (pintype "output"))
      (node (ref "E58") (pin "13") (pinfunction "I_13") (pintype "input"))
      (node (ref "E69") (pin "14") (pinfunction "B3_14") (pintype "input"))
      (node (ref "E79") (pin "11") (pinfunction "B2_11") (pintype "input"))
      (node (ref "E79") (pin "14") (pinfunction "B3_14") (pintype "input"))
      (node (ref "E79") (pin "2") (pinfunction "B0_2") (pintype "input"))
      (node (ref "E79") (pin "5") (pinfunction "B1_5") (pintype "input"))
    )
    (net (code "94") (name "Net-(E49B-O)") (class "Default")
      (node (ref "E49") (pin "6") (pinfunction "O_6") (pintype "output"))
      (node (ref "E70") (pin "5") (pinfunction "I1_5") (pintype "input"))
    )
    (net (code "95") (name "Net-(E49C-I1)") (class "Default")
      (node (ref "E49") (pin "10") (pinfunction "I1_10") (pintype "input"))
      (node (ref "E70") (pin "8") (pinfunction "O_8") (pintype "output"))
    )
    (net (code "96") (name "Net-(E50A-I0)") (class "Default")
      (node (ref "E50") (pin "1") (pinfunction "I0_1") (pintype "input"))
      (node (ref "E59") (pin "6") (pinfunction "~{Q}_6") (pintype "output"))
      (node (ref "E8") (pin "8") (pinfunction "I0_8") (pintype "input"))
    )
    (net (code "97") (name "Net-(E50A-O)") (class "Default")
      (node (ref "E50") (pin "3") (pinfunction "O_3") (pintype "output"))
      (node (ref "E50") (pin "4") (pinfunction "I0_4") (pintype "input"))
    )
    (net (code "98") (name "Net-(E50B-I1)") (class "Default")
      (node (ref "E50") (pin "5") (pinfunction "I1_5") (pintype "input"))
      (node (ref "E50") (pin "8") (pinfunction "O_8") (pintype "output"))
    )
    (net (code "99") (name "Net-(E50B-O)") (class "Default")
      (node (ref "E50") (pin "6") (pinfunction "O_6") (pintype "output"))
      (node (ref "E60") (pin "2") (pinfunction "D_2") (pintype "input"))
    )
    (net (code "100") (name "Net-(E50D-O)") (class "Default")
      (node (ref "E50") (pin "11") (pinfunction "O_11") (pintype "output"))
      (node (ref "E60") (pin "4") (pinfunction "PRE_4") (pintype "input"))
    )
    (net (code "101") (name "Net-(E52A-O)") (class "Default")
      (node (ref "E52") (pin "3") (pinfunction "O_3") (pintype "output"))
      (node (ref "E62") (pin "11") (pinfunction "D4_11") (pintype "input"))
    )
    (net (code "102") (name "Net-(E52B-O)") (class "Default")
      (node (ref "E52") (pin "2") (pinfunction "O_2") (pintype "output"))
      (node (ref "E62") (pin "12") (pinfunction "D3_12") (pintype "input"))
    )
    (net (code "103") (name "Net-(E52C-O)") (class "Default")
      (node (ref "E52") (pin "14") (pinfunction "O_14") (pintype "output"))
      (node (ref "E62") (pin "13") (pinfunction "D2_13") (pintype "input"))
    )
    (net (code "104") (name "Net-(E54A-O)") (class "Default")
      (node (ref "E54") (pin "3") (pinfunction "O_3") (pintype "output"))
      (node (ref "E54") (pin "4") (pinfunction "I0_4") (pintype "input"))
    )
    (net (code "105") (name "Net-(E54B-O)") (class "Default")
      (node (ref "E54") (pin "13") (pinfunction "I1_13") (pintype "input"))
      (node (ref "E54") (pin "6") (pinfunction "O_6") (pintype "output"))
    )
    (net (code "106") (name "Net-(E54C-I1)") (class "Default")
      (node (ref "E54") (pin "10") (pinfunction "I1_10") (pintype "input"))
      (node (ref "E65") (pin "9") (pinfunction "Q_9") (pintype "output"))
    )
    (net (code "107") (name "Net-(E54D-I0)") (class "Default")
      (node (ref "E54") (pin "12") (pinfunction "I0_12") (pintype "input"))
      (node (ref "E56") (pin "12") (pinfunction "O_12") (pintype "output"))
    )
    (net (code "108") (name "Net-(E54D-O)") (class "Default")
      (node (ref "E54") (pin "11") (pinfunction "O_11") (pintype "output"))
      (node (ref "E58") (pin "11") (pinfunction "I_11") (pintype "input"))
    )
    (net (code "109") (name "Net-(E56C-O)") (class "Default")
      (node (ref "E56") (pin "8") (pinfunction "O_8") (pintype "output"))
      (node (ref "E58") (pin "5") (pinfunction "I_5") (pintype "input"))
    )
    (net (code "110") (name "Net-(E57A-I0)") (class "Default")
      (node (ref "E57") (pin "1") (pinfunction "I0_1") (pintype "input"))
      (node (ref "E69") (pin "3") (pinfunction "F0_3") (pintype "output"))
    )
    (net (code "111") (name "Net-(E57A-O)") (class "Default")
      (node (ref "E57") (pin "3") (pinfunction "O_3") (pintype "output"))
      (node (ref "E77") (pin "4") (pinfunction "PRE_4") (pintype "input"))
    )
    (net (code "112") (name "Net-(E58C-O)") (class "Default")
      (node (ref "E58") (pin "6") (pinfunction "O_6") (pintype "output"))
      (node (ref "E77") (pin "1") (pinfunction "CLR_1") (pintype "input"))
    )
    (net (code "113") (name "Net-(E58D-O)") (class "Default")
      (node (ref "E58") (pin "8") (pinfunction "O_8") (pintype "output"))
      (node (ref "E66") (pin "2") (pinfunction "I1_2") (pintype "input"))
    )
    (net (code "114") (name "Net-(E58E-O)") (class "Default")
      (node (ref "E58") (pin "10") (pinfunction "O_10") (pintype "output"))
      (node (ref "E65") (pin "10") (pinfunction "PRE_10") (pintype "input"))
    )
    (net (code "115") (name "Net-(E59A-CLR)") (class "Default")
      (node (ref "E59") (pin "1") (pinfunction "CLR_1") (pintype "input"))
      (node (ref "E59") (pin "13") (pinfunction "CLR_13") (pintype "input"))
      (node (ref "E59") (pin "4") (pinfunction "PRE_4") (pintype "input"))
      (node (ref "R13") (pin "1") (pinfunction "1_1") (pintype "passive"))
    )
    (net (code "116") (name "Net-(E59B-D)") (class "Default")
      (node (ref "E59") (pin "12") (pinfunction "D_12") (pintype "input"))
      (node (ref "E60") (pin "6") (pinfunction "~{Q}_6") (pintype "output"))
    )
    (net (code "117") (name "Net-(E60B-PRE)") (class "Default")
      (node (ref "E6") (pin "3") (pinfunction "O_3") (pintype "output"))
      (node (ref "E60") (pin "10") (pinfunction "PRE_10") (pintype "input"))
    )
    (net (code "118") (name "Net-(E61A-O)") (class "Default")
      (node (ref "E61") (pin "3") (pinfunction "O_3") (pintype "output"))
      (node (ref "E61") (pin "6") (pinfunction "I0_6") (pintype "input"))
    )
    (net (code "119") (name "Net-(E63A-D)") (class "Default")
      (node (ref "E63") (pin "10") (pinfunction "PRE_10") (pintype "input"))
      (node (ref "E63") (pin "2") (pinfunction "D_2") (pintype "input"))
      (node (ref "R15") (pin "1") (pinfunction "1_1") (pintype "passive"))
    )
    (net (code "120") (name "Net-(E64A-O)") (class "Default")
      (node (ref "E64") (pin "1") (pinfunction "O_1") (pintype "output"))
      (node (ref "E64") (pin "6") (pinfunction "I1_6") (pintype "input"))
    )
    (net (code "121") (name "Net-(E64B-O)") (class "Default")
      (node (ref "C12") (pin "1") (pinfunction "1_1") (pintype "passive"))
      (node (ref "E64") (pin "4") (pinfunction "O_4") (pintype "output"))
      (node (ref "R5") (pin "1") (pinfunction "1_1") (pintype "passive"))
    )
    (net (code "122") (name "Net-(E66A-O)") (class "Default")
      (node (ref "E66") (pin "3") (pinfunction "O_3") (pintype "output"))
      (node (ref "E67") (pin "12") (pinfunction "I0_12") (pintype "input"))
    )
    (net (code "123") (name "Net-(E66B-O)") (class "Default")
      (node (ref "E66") (pin "6") (pinfunction "O_6") (pintype "output"))
      (node (ref "E76") (pin "4") (pinfunction "PRE_4") (pintype "input"))
      (node (ref "PAD3") (pin "1") (pinfunction "P_1") (pintype "passive"))
    )
    (net (code "124") (name "Net-(E66D-I1)") (class "Default")
      (node (ref "E66") (pin "13") (pinfunction "I1_13") (pintype "input"))
      (node (ref "E75") (pin "2") (pinfunction "O_2") (pintype "output"))
    )
    (net (code "125") (name "Net-(E66D-O)") (class "Default")
      (node (ref "E66") (pin "11") (pinfunction "O_11") (pintype "output"))
      (node (ref "E67") (pin "13") (pinfunction "I1_13") (pintype "input"))
    )
    (net (code "126") (name "Net-(E67A-I0)") (class "Default")
      (node (ref "E67") (pin "1") (pinfunction "I0_1") (pintype "input"))
      (node (ref "E80") (pin "1") (pinfunction "O0_1") (pintype "tri_state"))
    )
    (net (code "127") (name "Net-(E67A-O)") (class "Default")
      (node (ref "E67") (pin "3") (pinfunction "O_3") (pintype "output"))
      (node (ref "E69") (pin "1") (pinfunction "A0_1") (pintype "input"))
    )
    (net (code "128") (name "Net-(E67C-O)") (class "Default")
      (node (ref "E67") (pin "8") (pinfunction "O_8") (pintype "output"))
      (node (ref "E69") (pin "9") (pinfunction "S0_9") (pintype "input"))
      (node (ref "E79") (pin "9") (pinfunction "S0_9") (pintype "input"))
    )
    (net (code "129") (name "Net-(E67D-O)") (class "Default")
      (node (ref "E67") (pin "11") (pinfunction "O_11") (pintype "output"))
      (node (ref "E76") (pin "12") (pinfunction "D_12") (pintype "input"))
    )
    (net (code "130") (name "Net-(E68A-A<B_I)") (class "Default")
      (node (ref "E68") (pin "2") (pinfunction "A<B_I_2") (pintype "input"))
      (node (ref "E78") (pin "7") (pinfunction "A<B_O_7") (pintype "output"))
    )
    (net (code "131") (name "Net-(E68A-A=B_I)") (class "Default")
      (node (ref "E68") (pin "3") (pinfunction "A=B_I_3") (pintype "input"))
      (node (ref "E78") (pin "6") (pinfunction "A=B_O_6") (pintype "output"))
    )
    (net (code "132") (name "Net-(E68A-A>B_I)") (class "Default")
      (node (ref "E68") (pin "4") (pinfunction "A>B_I_4") (pintype "input"))
      (node (ref "E78") (pin "5") (pinfunction "A>B_O_5") (pintype "output"))
    )
    (net (code "133") (name "Net-(E69A-A1)") (class "Default")
      (node (ref "E69") (pin "6") (pinfunction "A1_6") (pintype "input"))
      (node (ref "E80") (pin "2") (pinfunction "O1_2") (pintype "tri_state"))
    )
    (net (code "134") (name "Net-(E69A-A2)") (class "Default")
      (node (ref "E69") (pin "10") (pinfunction "A2_10") (pintype "input"))
      (node (ref "E80") (pin "3") (pinfunction "O2_3") (pintype "tri_state"))
    )
    (net (code "135") (name "Net-(E69A-A3)") (class "Default")
      (node (ref "E69") (pin "15") (pinfunction "A3_15") (pintype "input"))
      (node (ref "E80") (pin "4") (pinfunction "O3_4") (pintype "tri_state"))
    )
    (net (code "136") (name "Net-(E70A-O)") (class "Default")
      (node (ref "E70") (pin "3") (pinfunction "O_3") (pintype "output"))
      (node (ref "E70") (pin "4") (pinfunction "I0_4") (pintype "input"))
    )
    (net (code "137") (name "Net-(E70D-O)") (class "Default")
      (node (ref "E70") (pin "11") (pinfunction "O_11") (pintype "output"))
      (node (ref "E80") (pin "13") (pinfunction "A3_13") (pintype "input"))
    )
    (net (code "138") (name "Net-(E76B-CLR)") (class "Default")
      (node (ref "E76") (pin "13") (pinfunction "CLR_13") (pintype "input"))
      (node (ref "R19") (pin "1") (pinfunction "1_1") (pintype "passive"))
    )
    (net (code "139") (name "Net-(E79A-A0)") (class "Default")
      (node (ref "E79") (pin "1") (pinfunction "A0_1") (pintype "input"))
      (node (ref "E80") (pin "5") (pinfunction "O4_5") (pintype "tri_state"))
    )
    (net (code "140") (name "Net-(E79A-A1)") (class "Default")
      (node (ref "E79") (pin "6") (pinfunction "A1_6") (pintype "input"))
      (node (ref "E80") (pin "6") (pinfunction "O5_6") (pintype "tri_state"))
    )
    (net (code "141") (name "Net-(E79A-A2)") (class "Default")
      (node (ref "E79") (pin "10") (pinfunction "A2_10") (pintype "input"))
      (node (ref "E80") (pin "7") (pinfunction "O6_7") (pintype "tri_state"))
    )
    (net (code "142") (name "Net-(E79A-A3)") (class "Default")
      (node (ref "E79") (pin "15") (pinfunction "A3_15") (pintype "input"))
      (node (ref "E80") (pin "9") (pinfunction "O7_9") (pintype "tri_state"))
    )
    (net (code "143") (name "Net-(E81A-O2)") (class "Default")
      (node (ref "E81") (pin "16") (pinfunction "O2_16") (pintype "tri_state"))
      (node (ref "E82") (pin "6") (pinfunction "D1_6") (pintype "input"))
    )
    (net (code "144") (name "Net-(E81A-O3)") (class "Default")
      (node (ref "E81") (pin "15") (pinfunction "O3_15") (pintype "tri_state"))
      (node (ref "E82") (pin "4") (pinfunction "D0_4") (pintype "input"))
    )
    (net (code "145") (name "Net-(E81A-O4)") (class "Default")
      (node (ref "E81") (pin "13") (pinfunction "O4_13") (pintype "tri_state"))
      (node (ref "E82") (pin "1") (pinfunction "A0_1") (pintype "input"))
      (node (ref "E90") (pin "11") (pinfunction "D4_11") (pintype "input"))
    )
    (net (code "146") (name "Net-(E81A-O5)") (class "Default")
      (node (ref "E81") (pin "12") (pinfunction "O5_12") (pintype "tri_state"))
      (node (ref "E82") (pin "13") (pinfunction "A3_13") (pintype "input"))
      (node (ref "E90") (pin "12") (pinfunction "D3_12") (pintype "input"))
    )
    (net (code "147") (name "Net-(E81A-O6)") (class "Default")
      (node (ref "E81") (pin "11") (pinfunction "O6_11") (pintype "tri_state"))
      (node (ref "E82") (pin "14") (pinfunction "A2_14") (pintype "input"))
      (node (ref "E90") (pin "13") (pinfunction "D2_13") (pintype "input"))
    )
    (net (code "148") (name "Net-(E81A-O7)") (class "Default")
      (node (ref "E81") (pin "10") (pinfunction "O7_10") (pintype "tri_state"))
      (node (ref "E82") (pin "15") (pinfunction "A1_15") (pintype "input"))
      (node (ref "E90") (pin "14") (pinfunction "D1_14") (pintype "input"))
    )
    (net (code "149") (name "Net-(E83C-~{G})") (class "Default")
      (node (ref "E83") (pin "15") (pinfunction "~{G}_15") (pintype "input"))
      (node (ref "E92") (pin "8") (pinfunction "O_8") (pintype "output"))
    )
    (net (code "150") (name "Net-(E84A-1G)") (class "Default")
      (node (ref "E84") (pin "1") (pinfunction "1G_1") (pintype "input"))
      (node (ref "E92") (pin "12") (pinfunction "O_12") (pintype "output"))
    )
    (net (code "151") (name "Net-(E100A-2A1)") (class "Default")
      (node (ref "E100") (pin "12") (pinfunction "2A1_12") (pintype "input"))
      (node (ref "E101") (pin "11") (pinfunction "Y1_11") (pintype "tri_state"))
      (node (ref "E120") (pin "3") (pinfunction "B_3") (pintype "input"))
      (node (ref "E82") (pin "5") (pinfunction "Q0_5") (pintype "output"))
      (node (ref "E91") (pin "11") (pinfunction "2Y1_11") (pintype "tri_state"))
      (node (ref "R23") (pin "1") (pinfunction "1_1") (pintype "passive"))
    )
    (net (code "152") (name "Net-(E100A-2A2)") (class "Default")
      (node (ref "E100") (pin "14") (pinfunction "2A2_14") (pintype "input"))
      (node (ref "E101") (pin "13") (pinfunction "Y2_13") (pintype "tri_state"))
      (node (ref "E120") (pin "2") (pinfunction "A_2") (pintype "input"))
      (node (ref "E82") (pin "7") (pinfunction "Q1_7") (pintype "output"))
      (node (ref "E91") (pin "13") (pinfunction "2Y2_13") (pintype "tri_state"))
      (node (ref "R22") (pin "1") (pinfunction "1_1") (pintype "passive"))
    )
    (net (code "153") (name "Net-(E101C-A1)") (class "Default")
      (node (ref "E101") (pin "12") (pinfunction "A1_12") (pintype "input"))
      (node (ref "E110") (pin "14") (pinfunction "~{Q4}_14") (pintype "output"))
      (node (ref "E91") (pin "2") (pinfunction "1A1_2") (pintype "input"))
    )
    (net (code "154") (name "Net-(E101C-A2)") (class "Default")
      (node (ref "E101") (pin "14") (pinfunction "A2_14") (pintype "input"))
      (node (ref "E110") (pin "11") (pinfunction "~{Q3}_11") (pintype "output"))
      (node (ref "E91") (pin "4") (pinfunction "1A2_4") (pintype "input"))
    )
    (net (code "155") (name "Net-(E102A-D2)") (class "Default")
      (node (ref "E102") (pin "5") (pinfunction "D2_5") (pintype "input"))
      (node (ref "E104") (pin "7") (pinfunction "1Y3_7") (pintype "tri_state"))
      (node (ref "E107") (pin "13") (pinfunction "2Y2_13") (pintype "tri_state"))
      (node (ref "E73") (pin "11") (pinfunction "D4_11") (pintype "input"))
      (node (ref "E84") (pin "3") (pinfunction "1Y1_3") (pintype "tri_state"))
      (node (ref "E95") (pin "13") (pinfunction "2Y2_13") (pintype "tri_state"))
      (node (ref "E96") (pin "13") (pinfunction "2Y2_13") (pintype "tri_state"))
      (node (ref "R28") (pin "1") (pinfunction "1_1") (pintype "passive"))
    )
    (net (code "156") (name "Net-(E102A-D3)") (class "Default")
      (node (ref "E102") (pin "12") (pinfunction "D3_12") (pintype "input"))
      (node (ref "E104") (pin "5") (pinfunction "1Y2_5") (pintype "tri_state"))
      (node (ref "E107") (pin "11") (pinfunction "2Y1_11") (pintype "tri_state"))
      (node (ref "E73") (pin "12") (pinfunction "D3_12") (pintype "input"))
      (node (ref "E84") (pin "5") (pinfunction "1Y2_5") (pintype "tri_state"))
      (node (ref "E95") (pin "11") (pinfunction "2Y1_11") (pintype "tri_state"))
      (node (ref "E96") (pin "11") (pinfunction "2Y1_11") (pintype "tri_state"))
      (node (ref "R32") (pin "1") (pinfunction "1_1") (pintype "passive"))
    )
    (net (code "157") (name "Net-(E102A-D4)") (class "Default")
      (node (ref "E102") (pin "13") (pinfunction "D4_13") (pintype "input"))
      (node (ref "E104") (pin "3") (pinfunction "1Y1_3") (pintype "tri_state"))
      (node (ref "E107") (pin "9") (pinfunction "1Y4_9") (pintype "tri_state"))
      (node (ref "E73") (pin "13") (pinfunction "D2_13") (pintype "input"))
      (node (ref "E84") (pin "7") (pinfunction "1Y3_7") (pintype "tri_state"))
      (node (ref "E95") (pin "9") (pinfunction "1Y4_9") (pintype "tri_state"))
      (node (ref "E96") (pin "9") (pinfunction "1Y4_9") (pintype "tri_state"))
      (node (ref "R33") (pin "1") (pinfunction "1_1") (pintype "passive"))
    )
    (net (code "158") (name "Net-(E104A-1G)") (class "Default")
      (node (ref "E104") (pin "1") (pinfunction "1G_1") (pintype "input"))
      (node (ref "E94") (pin "6") (pinfunction "O_6") (pintype "output"))
    )
    (net (code "159") (name "Net-(E105A-1G)") (class "Default")
      (node (ref "E105") (pin "1") (pinfunction "1G_1") (pintype "input"))
      (node (ref "E105") (pin "15") (pinfunction "2G_15") (pintype "input"))
      (node (ref "E115") (pin "8") (pinfunction "O_8") (pintype "output"))
    )
    (net (code "160") (name "Net-(E107A-1Y1)") (class "Default")
      (node (ref "E107") (pin "3") (pinfunction "1Y1_3") (pintype "tri_state"))
      (node (ref "E93") (pin "13") (pinfunction "D4_13") (pintype "input"))
      (node (ref "E95") (pin "3") (pinfunction "1Y1_3") (pintype "tri_state"))
      (node (ref "E96") (pin "3") (pinfunction "1Y1_3") (pintype "tri_state"))
      (node (ref "E97") (pin "11") (pinfunction "D4_11") (pintype "input"))
      (node (ref "E97") (pin "6") (pinfunction "Q4_6") (pintype "tri_state"))
      (node (ref "R35") (pin "1") (pinfunction "1_1") (pintype "passive"))
    )
    (net (code "161") (name "Net-(E107A-1Y2)") (class "Default")
      (node (ref "E107") (pin "5") (pinfunction "1Y2_5") (pintype "tri_state"))
      (node (ref "E93") (pin "12") (pinfunction "D3_12") (pintype "input"))
      (node (ref "E95") (pin "5") (pinfunction "1Y2_5") (pintype "tri_state"))
      (node (ref "E96") (pin "5") (pinfunction "1Y2_5") (pintype "tri_state"))
      (node (ref "E97") (pin "12") (pinfunction "D3_12") (pintype "input"))
      (node (ref "E97") (pin "5") (pinfunction "Q3_5") (pintype "tri_state"))
      (node (ref "R34") (pin "1") (pinfunction "1_1") (pintype "passive"))
    )
    (net (code "162") (name "Net-(E107A-1Y3)") (class "Default")
      (node (ref "E107") (pin "7") (pinfunction "1Y3_7") (pintype "tri_state"))
      (node (ref "E93") (pin "5") (pinfunction "D2_5") (pintype "input"))
      (node (ref "E95") (pin "7") (pinfunction "1Y3_7") (pintype "tri_state"))
      (node (ref "E96") (pin "7") (pinfunction "1Y3_7") (pintype "tri_state"))
      (node (ref "E97") (pin "13") (pinfunction "D2_13") (pintype "input"))
      (node (ref "E97") (pin "4") (pinfunction "Q2_4") (pintype "tri_state"))
      (node (ref "R29") (pin "1") (pinfunction "1_1") (pintype "passive"))
    )
    (net (code "163") (name "Net-(E108A-CLR)") (class "Default")
      (node (ref "E108") (pin "1") (pinfunction "CLR_1") (pintype "input"))
      (node (ref "E110") (pin "1") (pinfunction "CLR_1") (pintype "input"))
      (node (ref "E116") (pin "1") (pinfunction "CLR_1") (pintype "input"))
      (node (ref "E117") (pin "1") (pinfunction "CLR_1") (pintype "input"))
      (node (ref "R36") (pin "1") (pinfunction "1_1") (pintype "passive"))
    )
    (net (code "164") (name "Net-(E108A-D3)") (class "Default")
      (node (ref "E108") (pin "12") (pinfunction "D3_12") (pintype "input"))
      (node (ref "E109") (pin "13") (pinfunction "O4_13") (pintype "tri_state"))
    )
    (net (code "165") (name "Net-(E108A-D4)") (class "Default")
      (node (ref "E108") (pin "13") (pinfunction "D4_13") (pintype "input"))
      (node (ref "E109") (pin "12") (pinfunction "O5_12") (pintype "tri_state"))
    )
    (net (code "166") (name "Net-(E108A-Q3)") (class "Default")
      (node (ref "E108") (pin "10") (pinfunction "Q3_10") (pintype "output"))
      (node (ref "E111") (pin "5") (pinfunction "A0_5") (pintype "input"))
      (node (ref "E117") (pin "4") (pinfunction "D1_4") (pintype "input"))
    )
    (net (code "167") (name "Net-(E108A-Q4)") (class "Default")
      (node (ref "E108") (pin "15") (pinfunction "Q4_15") (pintype "output"))
      (node (ref "E111") (pin "4") (pinfunction "A3_4") (pintype "input"))
      (node (ref "E117") (pin "5") (pinfunction "D2_5") (pintype "input"))
    )
    (net (code "168") (name "Net-(E108A-~{Q3})") (class "Default")
      (node (ref "E108") (pin "11") (pinfunction "~{Q3}_11") (pintype "output"))
      (node (ref "E91") (pin "10") (pinfunction "1A4_10") (pintype "input"))
      (node (ref "E91") (pin "14") (pinfunction "2A2_14") (pintype "input"))
    )
    (net (code "169") (name "Net-(E108A-~{Q4})") (class "Default")
      (node (ref "E108") (pin "14") (pinfunction "~{Q4}_14") (pintype "output"))
      (node (ref "E91") (pin "12") (pinfunction "2A1_12") (pintype "input"))
      (node (ref "E91") (pin "6") (pinfunction "1A3_6") (pintype "input"))
    )
    (net (code "170") (name "Net-(E109A-O2)") (class "Default")
      (node (ref "E109") (pin "16") (pinfunction "O2_16") (pintype "tri_state"))
      (node (ref "E116") (pin "12") (pinfunction "D3_12") (pintype "input"))
    )
    (net (code "171") (name "Net-(E109A-O3)") (class "Default")
      (node (ref "E109") (pin "15") (pinfunction "O3_15") (pintype "tri_state"))
      (node (ref "E116") (pin "13") (pinfunction "D4_13") (pintype "input"))
    )
    (net (code "172") (name "Net-(E109A-O6)") (class "Default")
      (node (ref "E109") (pin "11") (pinfunction "O6_11") (pintype "tri_state"))
      (node (ref "E110") (pin "12") (pinfunction "D3_12") (pintype "input"))
    )
    (net (code "173") (name "Net-(E109A-O7)") (class "Default")
      (node (ref "E109") (pin "10") (pinfunction "O7_10") (pintype "tri_state"))
      (node (ref "E110") (pin "13") (pinfunction "D4_13") (pintype "input"))
    )
    (net (code "174") (name "Net-(E110A-Q3)") (class "Default")
      (node (ref "E110") (pin "10") (pinfunction "Q3_10") (pintype "output"))
      (node (ref "E111") (pin "6") (pinfunction "A1_6") (pintype "input"))
      (node (ref "E117") (pin "12") (pinfunction "D3_12") (pintype "input"))
    )
    (net (code "175") (name "Net-(E110A-Q4)") (class "Default")
      (node (ref "E110") (pin "15") (pinfunction "Q4_15") (pintype "output"))
      (node (ref "E111") (pin "3") (pinfunction "A4_3") (pintype "input"))
      (node (ref "E117") (pin "13") (pinfunction "D4_13") (pintype "input"))
    )
    (net (code "176") (name "Net-(E112A-O2)") (class "Default")
      (node (ref "E112") (pin "10") (pinfunction "O2_10") (pintype "tri_state"))
      (node (ref "E114") (pin "1") (pinfunction "A6_1") (pintype "input"))
    )
    (net (code "177") (name "Net-(E113A-A6)") (class "Default")
      (node (ref "E113") (pin "1") (pinfunction "A6_1") (pintype "input"))
      (node (ref "E87") (pin "9") (pinfunction "O3_9") (pintype "tri_state"))
    )
    (net (code "178") (name "Net-(E115A-O)") (class "Default")
      (node (ref "E115") (pin "2") (pinfunction "O_2") (pintype "output"))
      (node (ref "E97") (pin "2") (pinfunction "N_2") (pintype "input"))
    )
    (net (code "179") (name "Net-(E115C-I)") (class "Default")
      (node (ref "E115") (pin "5") (pinfunction "I_5") (pintype "input"))
      (node (ref "E72") (pin "3") (pinfunction "O_3") (pintype "output"))
      (node (ref "E92") (pin "9") (pinfunction "I0_9") (pintype "input"))
    )
    (net (code "180") (name "Net-(E115C-O)") (class "Default")
      (node (ref "E115") (pin "6") (pinfunction "O_6") (pintype "output"))
      (node (ref "E92") (pin "3") (pinfunction "I0_3") (pintype "input"))
    )
    (net (code "181") (name "Net-(E115E-O)") (class "Default")
      (node (ref "E115") (pin "10") (pinfunction "O_10") (pintype "output"))
      (node (ref "E89") (pin "3") (pinfunction "6_3") (pintype "input"))
    )
    (net (code "182") (name "Net-(E120B-Y0)") (class "Default")
      (node (ref "E120") (pin "12") (pinfunction "Y0_12") (pintype "output"))
      (node (ref "E121") (pin "11") (pinfunction "D4_11") (pintype "input"))
      (node (ref "E122") (pin "11") (pinfunction "D4_11") (pintype "input"))
    )
    (net (code "183") (name "Net-(E120B-Y1)") (class "Default")
      (node (ref "E120") (pin "11") (pinfunction "Y1_11") (pintype "output"))
      (node (ref "E121") (pin "12") (pinfunction "D3_12") (pintype "input"))
      (node (ref "E122") (pin "12") (pinfunction "D3_12") (pintype "input"))
    )
    (net (code "184") (name "Net-(E120B-Y2)") (class "Default")
      (node (ref "E120") (pin "10") (pinfunction "Y2_10") (pintype "output"))
      (node (ref "E121") (pin "13") (pinfunction "D2_13") (pintype "input"))
      (node (ref "E122") (pin "13") (pinfunction "D2_13") (pintype "input"))
    )
    (net (code "185") (name "Net-(E120B-Y3)") (class "Default")
      (node (ref "E120") (pin "9") (pinfunction "Y3_9") (pintype "output"))
      (node (ref "E121") (pin "14") (pinfunction "D1_14") (pintype "input"))
      (node (ref "E122") (pin "14") (pinfunction "D1_14") (pintype "input"))
    )
    (net (code "186") (name "Net-(Q1-B)") (class "Default")
      (node (ref "C12") (pin "2") (pinfunction "2_2") (pintype "passive"))
      (node (ref "D1") (pin "A") (pinfunction "A_A") (pintype "passive"))
      (node (ref "Q1") (pin "2") (pinfunction "B_2") (pintype "passive"))
      (node (ref "R5") (pin "2") (pinfunction "2_2") (pintype "passive"))
    )
    (net (code "187") (name "P1_3V") (class "Default")
      (node (ref "E114") (pin "2") (pinfunction "A5_2") (pintype "input"))
      (node (ref "E114") (pin "3") (pinfunction "A4_3") (pintype "input"))
      (node (ref "E114") (pin "4") (pinfunction "A3_4") (pintype "input"))
      (node (ref "E78") (pin "3") (pinfunction "A=B_I_3") (pintype "input"))
      (node (ref "R21") (pin "1") (pinfunction "1_1") (pintype "passive"))
    )
    (net (code "188") (name "P1_BB0") (class "Default")
      (node (ref "E109") (pin "3") (pinfunction "I6_3") (pintype "input"))
      (node (ref "E113") (pin "11") (pinfunction "O1_11") (pintype "tri_state"))
    )
    (net (code "189") (name "P1_BB1") (class "Default")
      (node (ref "E109") (pin "4") (pinfunction "I5_4") (pintype "input"))
      (node (ref "E113") (pin "12") (pinfunction "O0_12") (pintype "tri_state"))
    )
    (net (code "190") (name "P1_BFL0") (class "Default")
      (node (ref "E87") (pin "10") (pinfunction "O2_10") (pintype "tri_state"))
      (node (ref "E95") (pin "10") (pinfunction "1A4_10") (pintype "input"))
      (node (ref "E95") (pin "2") (pinfunction "1A1_2") (pintype "input"))
    )
    (net (code "191") (name "P1_BFL1") (class "Default")
      (node (ref "E87") (pin "11") (pinfunction "O1_11") (pintype "tri_state"))
      (node (ref "E95") (pin "12") (pinfunction "2A1_12") (pintype "input"))
      (node (ref "E95") (pin "4") (pinfunction "1A2_4") (pintype "input"))
    )
    (net (code "192") (name "P1_BFL2") (class "Default")
      (node (ref "E87") (pin "12") (pinfunction "O0_12") (pintype "tri_state"))
      (node (ref "E95") (pin "14") (pinfunction "2A2_14") (pintype "input"))
      (node (ref "E95") (pin "6") (pinfunction "1A3_6") (pintype "input"))
    )
    (net (code "193") (name "P1_CRF") (class "Default")
      (node (ref "E111") (pin "1") (pinfunction "A6_1") (pintype "input"))
      (node (ref "E114") (pin "10") (pinfunction "O2_10") (pintype "tri_state"))
    )
    (net (code "194") (name "P1_OVER") (class "Default")
      (node (ref "E39") (pin "12") (pinfunction "O_12") (pintype "output"))
      (node (ref "E49") (pin "11") (pinfunction "I2_11") (pintype "input"))
    )
    (net (code "195") (name "P1_RR0") (class "Default")
      (node (ref "E111") (pin "2") (pinfunction "A5_2") (pintype "input"))
      (node (ref "E113") (pin "3") (pinfunction "A4_3") (pintype "input"))
      (node (ref "E85") (pin "15") (pinfunction "Q6_15") (pintype "output"))
      (node (ref "E86") (pin "2") (pinfunction "1A1_2") (pintype "input"))
    )
    (net (code "196") (name "P1_RR1") (class "Default")
      (node (ref "E111") (pin "7") (pinfunction "A2_7") (pintype "input"))
      (node (ref "E113") (pin "4") (pinfunction "A3_4") (pintype "input"))
      (node (ref "E85") (pin "2") (pinfunction "Q1_2") (pintype "output"))
      (node (ref "E86") (pin "4") (pinfunction "1A2_4") (pintype "input"))
    )
    (net (code "197") (name "P1_RR2") (class "Default")
      (node (ref "E114") (pin "7") (pinfunction "A2_7") (pintype "input"))
      (node (ref "E85") (pin "12") (pinfunction "Q5_12") (pintype "output"))
      (node (ref "E86") (pin "6") (pinfunction "1A3_6") (pintype "input"))
      (node (ref "E87") (pin "2") (pinfunction "A5_2") (pintype "input"))
    )
    (net (code "198") (name "P1_RR3") (class "Default")
      (node (ref "E112") (pin "2") (pinfunction "A5_2") (pintype "input"))
      (node (ref "E85") (pin "7") (pinfunction "Q3_7") (pintype "output"))
      (node (ref "E86") (pin "10") (pinfunction "1A4_10") (pintype "input"))
      (node (ref "E87") (pin "3") (pinfunction "A4_3") (pintype "input"))
    )
    (net (code "199") (name "P1_RR4") (class "Default")
      (node (ref "E112") (pin "7") (pinfunction "A2_7") (pintype "input"))
      (node (ref "E85") (pin "10") (pinfunction "Q4_10") (pintype "output"))
      (node (ref "E86") (pin "12") (pinfunction "2A1_12") (pintype "input"))
      (node (ref "E87") (pin "4") (pinfunction "A3_4") (pintype "input"))
    )
    (net (code "200") (name "P1_US0") (class "Default")
      (node (ref "E106") (pin "2") (pinfunction "1A1_2") (pintype "input"))
      (node (ref "E68") (pin "11") (pinfunction "B1_11") (pintype "input"))
      (node (ref "E88") (pin "15") (pinfunction "Q6_15") (pintype "output"))
    )
    (net (code "201") (name "P1_US1") (class "Default")
      (node (ref "E106") (pin "4") (pinfunction "1A2_4") (pintype "input"))
      (node (ref "E68") (pin "9") (pinfunction "B0_9") (pintype "input"))
      (node (ref "E88") (pin "2") (pinfunction "Q1_2") (pintype "output"))
    )
    (net (code "202") (name "P1_US2") (class "Default")
      (node (ref "E106") (pin "6") (pinfunction "1A3_6") (pintype "input"))
      (node (ref "E78") (pin "1") (pinfunction "B3_1") (pintype "input"))
      (node (ref "E88") (pin "5") (pinfunction "Q2_5") (pintype "output"))
    )
    (net (code "203") (name "P1_US3") (class "Default")
      (node (ref "E106") (pin "10") (pinfunction "1A4_10") (pintype "input"))
      (node (ref "E78") (pin "14") (pinfunction "B2_14") (pintype "input"))
      (node (ref "E88") (pin "12") (pinfunction "Q5_12") (pintype "output"))
    )
    (net (code "204") (name "P1_US4") (class "Default")
      (node (ref "E106") (pin "12") (pinfunction "2A1_12") (pintype "input"))
      (node (ref "E78") (pin "11") (pinfunction "B1_11") (pintype "input"))
      (node (ref "E88") (pin "7") (pinfunction "Q3_7") (pintype "output"))
    )
    (net (code "205") (name "P1_US5") (class "Default")
      (node (ref "E106") (pin "14") (pinfunction "2A2_14") (pintype "input"))
      (node (ref "E78") (pin "9") (pinfunction "B0_9") (pintype "input"))
      (node (ref "E88") (pin "10") (pinfunction "Q4_10") (pintype "output"))
    )
    (net (code "206") (name "P2_3V") (class "Default")
      (node (ref "E102") (pin "1") (pinfunction "CLR_1") (pintype "input"))
      (node (ref "E103") (pin "1") (pinfunction "CLR_1") (pintype "input"))
      (node (ref "E93") (pin "1") (pinfunction "CLR_1") (pintype "input"))
      (node (ref "R30") (pin "1") (pinfunction "1_1") (pintype "passive"))
    )
    (net (code "207") (name "P2_DFA") (class "Default")
      (node (ref "E102") (pin "6") (pinfunction "~{Q2}_6") (pintype "output"))
      (node (ref "E112") (pin "5") (pinfunction "A0_5") (pintype "input"))
    )
    (net (code "208") (name "P2_DFB") (class "Default")
      (node (ref "E102") (pin "11") (pinfunction "~{Q3}_11") (pintype "output"))
      (node (ref "E112") (pin "4") (pinfunction "A3_4") (pintype "input"))
    )
    (net (code "209") (name "P2_DFC") (class "Default")
      (node (ref "E102") (pin "14") (pinfunction "~{Q4}_14") (pintype "output"))
      (node (ref "E114") (pin "5") (pinfunction "A0_5") (pintype "input"))
    )
    (net (code "210") (name "P2_EMAEN") (class "Default")
      (node (ref "E63") (pin "9") (pinfunction "Q_9") (pintype "output"))
      (node (ref "E64") (pin "9") (pinfunction "I1_9") (pintype "input"))
    )
    (net (code "211") (name "P2_IFA") (class "Default")
      (node (ref "E112") (pin "6") (pinfunction "A1_6") (pintype "input"))
      (node (ref "E93") (pin "6") (pinfunction "~{Q2}_6") (pintype "output"))
    )
    (net (code "212") (name "P2_IFB") (class "Default")
      (node (ref "E112") (pin "3") (pinfunction "A4_3") (pintype "input"))
      (node (ref "E93") (pin "11") (pinfunction "~{Q3}_11") (pintype "output"))
    )
    (net (code "213") (name "P2_IFC") (class "Default")
      (node (ref "E114") (pin "6") (pinfunction "A1_6") (pintype "input"))
      (node (ref "E93") (pin "14") (pinfunction "~{Q4}_14") (pintype "output"))
    )
    (net (code "214") (name "P2_SF0") (class "Default")
      (node (ref "E103") (pin "2") (pinfunction "Q1_2") (pintype "output"))
      (node (ref "E105") (pin "14") (pinfunction "2A2_14") (pintype "input"))
      (node (ref "E107") (pin "2") (pinfunction "1A1_2") (pintype "input"))
    )
    (net (code "215") (name "P2_SF1") (class "Default")
      (node (ref "E103") (pin "5") (pinfunction "Q2_5") (pintype "output"))
      (node (ref "E105") (pin "12") (pinfunction "2A1_12") (pintype "input"))
      (node (ref "E107") (pin "4") (pinfunction "1A2_4") (pintype "input"))
    )
    (net (code "216") (name "P2_SF2") (class "Default")
      (node (ref "E103") (pin "7") (pinfunction "Q3_7") (pintype "output"))
      (node (ref "E105") (pin "10") (pinfunction "1A4_10") (pintype "input"))
      (node (ref "E107") (pin "6") (pinfunction "1A3_6") (pintype "input"))
    )
    (net (code "217") (name "P2_SF3") (class "Default")
      (node (ref "E103") (pin "10") (pinfunction "Q4_10") (pintype "output"))
      (node (ref "E105") (pin "6") (pinfunction "1A3_6") (pintype "input"))
      (node (ref "E107") (pin "10") (pinfunction "1A4_10") (pintype "input"))
    )
    (net (code "218") (name "P2_SF4") (class "Default")
      (node (ref "E103") (pin "12") (pinfunction "Q5_12") (pintype "output"))
      (node (ref "E105") (pin "4") (pinfunction "1A2_4") (pintype "input"))
      (node (ref "E107") (pin "12") (pinfunction "2A1_12") (pintype "input"))
    )
    (net (code "219") (name "P2_SF5") (class "Default")
      (node (ref "E103") (pin "15") (pinfunction "Q6_15") (pintype "output"))
      (node (ref "E105") (pin "2") (pinfunction "1A1_2") (pintype "input"))
      (node (ref "E107") (pin "14") (pinfunction "2A2_14") (pintype "input"))
    )
    (net (code "220") (name "P2_SUF_OUT") (class "Default")
      (node (ref "E115") (pin "9") (pinfunction "I_9") (pintype "input"))
      (node (ref "E38") (pin "13") (pinfunction "I1_13") (pintype "input"))
      (node (ref "E56") (pin "6") (pinfunction "O_6") (pintype "output"))
      (node (ref "E8") (pin "9") (pinfunction "I1_9") (pintype "input"))
    )
    (net (code "221") (name "P3_BD") (class "Default")
      (node (ref "E61") (pin "14") (pinfunction "O_14") (pintype "output"))
      (node (ref "E66") (pin "1") (pinfunction "I0_1") (pintype "input"))
      (node (ref "E70") (pin "2") (pinfunction "I1_2") (pintype "input"))
    )
    (net (code "222") (name "P3_BD0") (class "Default")
      (node (ref "E12") (pin "6") (pinfunction "I3_6") (pintype "output"))
      (node (ref "E17") (pin "3") (pinfunction "D1_3") (pintype "input"))
      (node (ref "E35") (pin "13") (pinfunction "D4_13") (pintype "input"))
      (node (ref "E81") (pin "24") (pinfunction "I11_24") (pintype "input"))
    )
    (net (code "223") (name "P3_BD1") (class "Default")
      (node (ref "E109") (pin "5") (pinfunction "I4_5") (pintype "input"))
      (node (ref "E12") (pin "3") (pinfunction "I2_3") (pintype "output"))
      (node (ref "E120") (pin "14") (pinfunction "A_14") (pintype "input"))
      (node (ref "E17") (pin "4") (pinfunction "D2_4") (pintype "input"))
      (node (ref "E35") (pin "12") (pinfunction "D3_12") (pintype "input"))
      (node (ref "E81") (pin "25") (pinfunction "I10_25") (pintype "input"))
    )
    (net (code "224") (name "P3_BD2") (class "Default")
      (node (ref "E109") (pin "6") (pinfunction "I3_6") (pintype "input"))
      (node (ref "E12") (pin "10") (pinfunction "I1_10") (pintype "output"))
      (node (ref "E120") (pin "13") (pinfunction "B_13") (pintype "input"))
      (node (ref "E17") (pin "6") (pinfunction "D3_6") (pintype "input"))
      (node (ref "E35") (pin "5") (pinfunction "D2_5") (pintype "input"))
      (node (ref "E81") (pin "26") (pinfunction "I9_26") (pintype "input"))
    )
    (net (code "225") (name "P3_BD3") (class "Default")
      (node (ref "E109") (pin "7") (pinfunction "I2_7") (pintype "input"))
      (node (ref "E12") (pin "13") (pinfunction "I0_13") (pintype "output"))
      (node (ref "E17") (pin "11") (pinfunction "D4_11") (pintype "input"))
      (node (ref "E35") (pin "4") (pinfunction "D1_4") (pintype "input"))
      (node (ref "E81") (pin "27") (pinfunction "I8_27") (pintype "input"))
    )
    (net (code "226") (name "P3_BD4") (class "Default")
      (node (ref "E109") (pin "8") (pinfunction "I1_8") (pintype "input"))
      (node (ref "E13") (pin "6") (pinfunction "I3_6") (pintype "output"))
      (node (ref "E17") (pin "13") (pinfunction "D5_13") (pintype "input"))
      (node (ref "E46") (pin "13") (pinfunction "D4_13") (pintype "input"))
      (node (ref "E81") (pin "2") (pinfunction "I7_2") (pintype "input"))
    )
    (net (code "227") (name "P3_BD5") (class "Default")
      (node (ref "E109") (pin "9") (pinfunction "I0_9") (pintype "input"))
      (node (ref "E13") (pin "3") (pinfunction "I2_3") (pintype "output"))
      (node (ref "E17") (pin "14") (pinfunction "D6_14") (pintype "input"))
      (node (ref "E46") (pin "12") (pinfunction "D3_12") (pintype "input"))
      (node (ref "E50") (pin "10") (pinfunction "I1_10") (pintype "input"))
      (node (ref "E81") (pin "3") (pinfunction "I6_3") (pintype "input"))
    )
    (net (code "228") (name "P3_BD6") (class "Default")
      (node (ref "E13") (pin "10") (pinfunction "I1_10") (pintype "output"))
      (node (ref "E15") (pin "3") (pinfunction "D1_3") (pintype "input"))
      (node (ref "E2") (pin "1") (pinfunction "I_1") (pintype "input"))
      (node (ref "E46") (pin "5") (pinfunction "D2_5") (pintype "input"))
      (node (ref "E81") (pin "4") (pinfunction "I5_4") (pintype "input"))
      (node (ref "E88") (pin "14") (pinfunction "D6_14") (pintype "input"))
      (node (ref "E96") (pin "2") (pinfunction "1A1_2") (pintype "input"))
    )
    (net (code "229") (name "P3_BD7") (class "Default")
      (node (ref "E13") (pin "13") (pinfunction "I0_13") (pintype "output"))
      (node (ref "E15") (pin "4") (pinfunction "D2_4") (pintype "input"))
      (node (ref "E2") (pin "3") (pinfunction "I_3") (pintype "input"))
      (node (ref "E81") (pin "5") (pinfunction "I4_5") (pintype "input"))
      (node (ref "E85") (pin "14") (pinfunction "D6_14") (pintype "input"))
      (node (ref "E88") (pin "3") (pinfunction "D1_3") (pintype "input"))
      (node (ref "E96") (pin "4") (pinfunction "1A2_4") (pintype "input"))
    )
    (net (code "230") (name "P3_BD8") (class "Default")
      (node (ref "E15") (pin "6") (pinfunction "D3_6") (pintype "input"))
      (node (ref "E2") (pin "5") (pinfunction "I_5") (pintype "input"))
      (node (ref "E45") (pin "6") (pinfunction "I3_6") (pintype "output"))
      (node (ref "E81") (pin "6") (pinfunction "I3_6") (pintype "input"))
      (node (ref "E85") (pin "3") (pinfunction "D1_3") (pintype "input"))
      (node (ref "E88") (pin "4") (pinfunction "D2_4") (pintype "input"))
      (node (ref "E96") (pin "6") (pinfunction "1A3_6") (pintype "input"))
    )
    (net (code "231") (name "P3_BD9") (class "Default")
      (node (ref "E15") (pin "11") (pinfunction "D4_11") (pintype "input"))
      (node (ref "E45") (pin "3") (pinfunction "I2_3") (pintype "output"))
      (node (ref "E81") (pin "7") (pinfunction "I2_7") (pintype "input"))
      (node (ref "E85") (pin "13") (pinfunction "D5_13") (pintype "input"))
      (node (ref "E88") (pin "13") (pinfunction "D5_13") (pintype "input"))
      (node (ref "E96") (pin "10") (pinfunction "1A4_10") (pintype "input"))
    )
    (net (code "232") (name "P3_BD10") (class "Default")
      (node (ref "E15") (pin "13") (pinfunction "D5_13") (pintype "input"))
      (node (ref "E45") (pin "10") (pinfunction "I1_10") (pintype "output"))
      (node (ref "E81") (pin "8") (pinfunction "I1_8") (pintype "input"))
      (node (ref "E85") (pin "6") (pinfunction "D3_6") (pintype "input"))
      (node (ref "E88") (pin "6") (pinfunction "D3_6") (pintype "input"))
      (node (ref "E96") (pin "12") (pinfunction "2A1_12") (pintype "input"))
    )
    (net (code "233") (name "P3_BD11") (class "Default")
      (node (ref "E15") (pin "14") (pinfunction "D6_14") (pintype "input"))
      (node (ref "E45") (pin "13") (pinfunction "I0_13") (pintype "output"))
      (node (ref "E81") (pin "9") (pinfunction "I0_9") (pintype "input"))
      (node (ref "E85") (pin "11") (pinfunction "D4_11") (pintype "input"))
      (node (ref "E88") (pin "11") (pinfunction "D4_11") (pintype "input"))
      (node (ref "E96") (pin "14") (pinfunction "2A2_14") (pintype "input"))
    )
    (net (code "234") (name "P3_BF") (class "Default")
      (node (ref "E21") (pin "2") (pinfunction "I1_2") (pintype "input"))
      (node (ref "E30") (pin "11") (pinfunction "I6_11") (pintype "input"))
      (node (ref "E49") (pin "4") (pinfunction "I1_4") (pintype "input"))
      (node (ref "E61") (pin "13") (pinfunction "O_13") (pintype "output"))
    )
    (net (code "235") (name "P3_BINIT") (class "Default")
      (node (ref "E22") (pin "3") (pinfunction "I_3") (pintype "input"))
      (node (ref "E53") (pin "13") (pinfunction "O_13") (pintype "output"))
      (node (ref "E62") (pin "15") (pinfunction "CLR_15") (pintype "input"))
      (node (ref "E90") (pin "15") (pinfunction "CLR_15") (pintype "input"))
      (node (ref "E98") (pin "15") (pinfunction "CLR_15") (pintype "input"))
      (node (ref "E99") (pin "15") (pinfunction "CLR_15") (pintype "input"))
    )
    (net (code "236") (name "P3_BM0") (class "Default")
      (node (ref "E11") (pin "2") (pinfunction "O_2") (pintype "output"))
      (node (ref "E21") (pin "13") (pinfunction "I2_13") (pintype "input"))
      (node (ref "E30") (pin "1") (pinfunction "I0_1") (pintype "input"))
      (node (ref "E5") (pin "11") (pinfunction "I_11") (pintype "input"))
    )
    (net (code "237") (name "P3_BM1") (class "Default")
      (node (ref "E11") (pin "3") (pinfunction "O_3") (pintype "output"))
      (node (ref "E21") (pin "1") (pinfunction "I0_1") (pintype "input"))
      (node (ref "E29") (pin "3") (pinfunction "I1_3") (pintype "input"))
      (node (ref "E30") (pin "2") (pinfunction "I1_2") (pintype "input"))
    )
    (net (code "238") (name "P3_BM2") (class "Default")
      (node (ref "E11") (pin "13") (pinfunction "O_13") (pintype "output"))
      (node (ref "E14") (pin "21") (pinfunction "I14_21") (pintype "input"))
      (node (ref "E5") (pin "13") (pinfunction "I_13") (pintype "input"))
      (node (ref "E8") (pin "2") (pinfunction "I0_2") (pintype "input"))
    )
    (net (code "239") (name "P3_BM3") (class "Default")
      (node (ref "E11") (pin "14") (pinfunction "O_14") (pintype "output"))
      (node (ref "E14") (pin "22") (pinfunction "I13_22") (pintype "input"))
      (node (ref "E7") (pin "11") (pinfunction "I_11") (pintype "input"))
    )
    (net (code "240") (name "P3_BM4") (class "Default")
      (node (ref "E14") (pin "23") (pinfunction "I12_23") (pintype "input"))
      (node (ref "E25") (pin "2") (pinfunction "O_2") (pintype "output"))
      (node (ref "E28") (pin "3") (pinfunction "A4_3") (pintype "input"))
      (node (ref "E36") (pin "1") (pinfunction "I0_1") (pintype "input"))
      (node (ref "E7") (pin "13") (pinfunction "I_13") (pintype "input"))
    )
    (net (code "241") (name "P3_BM5") (class "Default")
      (node (ref "E113") (pin "6") (pinfunction "A1_6") (pintype "input"))
      (node (ref "E14") (pin "24") (pinfunction "I11_24") (pintype "input"))
      (node (ref "E25") (pin "3") (pinfunction "O_3") (pintype "output"))
      (node (ref "E28") (pin "4") (pinfunction "A3_4") (pintype "input"))
      (node (ref "E68") (pin "10") (pinfunction "A0_10") (pintype "input"))
    )
    (net (code "242") (name "P3_BM6") (class "Default")
      (node (ref "E14") (pin "25") (pinfunction "I10_25") (pintype "input"))
      (node (ref "E21") (pin "9") (pinfunction "I0_9") (pintype "input"))
      (node (ref "E25") (pin "13") (pinfunction "O_13") (pintype "output"))
      (node (ref "E31") (pin "21") (pinfunction "C_21") (pintype "input"))
      (node (ref "E78") (pin "13") (pinfunction "A2_13") (pintype "input"))
      (node (ref "E87") (pin "7") (pinfunction "A2_7") (pintype "input"))
    )
    (net (code "243") (name "P3_BM7") (class "Default")
      (node (ref "E14") (pin "26") (pinfunction "I9_26") (pintype "input"))
      (node (ref "E21") (pin "10") (pinfunction "I1_10") (pintype "input"))
      (node (ref "E25") (pin "14") (pinfunction "O_14") (pintype "output"))
      (node (ref "E31") (pin "22") (pinfunction "B_22") (pintype "input"))
      (node (ref "E78") (pin "12") (pinfunction "A1_12") (pintype "input"))
      (node (ref "E87") (pin "6") (pinfunction "A1_6") (pintype "input"))
    )
    (net (code "244") (name "P3_BM8") (class "Default")
      (node (ref "E14") (pin "27") (pinfunction "I8_27") (pintype "input"))
      (node (ref "E21") (pin "11") (pinfunction "I2_11") (pintype "input"))
      (node (ref "E31") (pin "23") (pinfunction "A_23") (pintype "input"))
      (node (ref "E71") (pin "2") (pinfunction "O_2") (pintype "output"))
      (node (ref "E78") (pin "10") (pinfunction "A0_10") (pintype "input"))
      (node (ref "E87") (pin "5") (pinfunction "A0_5") (pintype "input"))
    )
    (net (code "245") (name "P3_BM9") (class "Default")
      (node (ref "E113") (pin "5") (pinfunction "A0_5") (pintype "input"))
      (node (ref "E14") (pin "2") (pinfunction "I7_2") (pintype "input"))
      (node (ref "E28") (pin "7") (pinfunction "A2_7") (pintype "input"))
      (node (ref "E31") (pin "20") (pinfunction "D_20") (pintype "input"))
      (node (ref "E34") (pin "13") (pinfunction "C_13") (pintype "input"))
      (node (ref "E36") (pin "10") (pinfunction "I1_10") (pintype "input"))
      (node (ref "E43") (pin "4") (pinfunction "I2_4") (pintype "input"))
      (node (ref "E44") (pin "11") (pinfunction "I_11") (pintype "input"))
      (node (ref "E47") (pin "5") (pinfunction "I0_5") (pintype "input"))
      (node (ref "E47") (pin "9") (pinfunction "I1_9") (pintype "input"))
      (node (ref "E71") (pin "3") (pinfunction "O_3") (pintype "output"))
      (node (ref "E78") (pin "15") (pinfunction "A3_15") (pintype "input"))
    )
    (net (code "246") (name "P3_BM10") (class "Default")
      (node (ref "E14") (pin "3") (pinfunction "I6_3") (pintype "input"))
      (node (ref "E28") (pin "6") (pinfunction "A1_6") (pintype "input"))
      (node (ref "E34") (pin "14") (pinfunction "B_14") (pintype "input"))
      (node (ref "E71") (pin "13") (pinfunction "O_13") (pintype "output"))
    )
    (net (code "247") (name "P3_BM11") (class "Default")
      (node (ref "E14") (pin "4") (pinfunction "I5_4") (pintype "input"))
      (node (ref "E28") (pin "5") (pinfunction "A0_5") (pintype "input"))
      (node (ref "E34") (pin "15") (pinfunction "A_15") (pintype "input"))
      (node (ref "E36") (pin "12") (pinfunction "I2_12") (pintype "input"))
      (node (ref "E44") (pin "13") (pinfunction "I_13") (pintype "input"))
      (node (ref "E71") (pin "14") (pinfunction "O_14") (pintype "output"))
    )
    (net (code "248") (name "P3_BPAUSE") (class "Default")
      (node (ref "E14") (pin "5") (pinfunction "I4_5") (pintype "input"))
      (node (ref "E26") (pin "16") (pinfunction "1Q_16") (pintype "output"))
      (node (ref "E74") (pin "7") (pinfunction "A2_7") (pintype "input"))
    )
    (net (code "249") (name "P3_BPLA") (class "Default")
      (node (ref "E53") (pin "3") (pinfunction "O_3") (pintype "output"))
      (node (ref "E57") (pin "5") (pinfunction "I1_5") (pintype "input"))
    )
    (net (code "250") (name "P3_BTP1") (class "Default")
      (node (ref "E53") (pin "2") (pinfunction "O_2") (pintype "output"))
      (node (ref "E54") (pin "9") (pinfunction "I0_9") (pintype "input"))
    )
    (net (code "251") (name "P3_BTP2") (class "Default")
      (node (ref "E15") (pin "9") (pinfunction "CLK_9") (pintype "input"))
      (node (ref "E17") (pin "9") (pinfunction "CLK_9") (pintype "input"))
      (node (ref "E22") (pin "1") (pinfunction "I_1") (pintype "input"))
      (node (ref "E27") (pin "9") (pinfunction "I0_9") (pintype "input"))
      (node (ref "E53") (pin "14") (pinfunction "O_14") (pintype "output"))
    )
    (net (code "252") (name "P3_BTP3") (class "Default")
      (node (ref "E18") (pin "1") (pinfunction "I0_1") (pintype "input"))
      (node (ref "E18") (pin "4") (pinfunction "I0_4") (pintype "input"))
      (node (ref "E29") (pin "8") (pinfunction "I0_8") (pintype "input"))
      (node (ref "E32") (pin "11") (pinfunction "CLK_11") (pintype "input"))
      (node (ref "E38") (pin "3") (pinfunction "O_3") (pintype "output"))
      (node (ref "E50") (pin "12") (pinfunction "I0_12") (pintype "input"))
      (node (ref "E56") (pin "13") (pinfunction "I2_13") (pintype "input"))
      (node (ref "E6") (pin "1") (pinfunction "I0_1") (pintype "input"))
      (node (ref "E67") (pin "10") (pinfunction "I1_10") (pintype "input"))
      (node (ref "E76") (pin "11") (pinfunction "CLK_11") (pintype "input"))
    )
    (net (code "253") (name "P3_BTP4") (class "Default")
      (node (ref "E118") (pin "7") (pinfunction "CLK_7") (pintype "input"))
      (node (ref "E119") (pin "7") (pinfunction "CLK_7") (pintype "input"))
      (node (ref "E27") (pin "12") (pinfunction "O_12") (pintype "output"))
      (node (ref "E54") (pin "5") (pinfunction "I1_5") (pintype "input"))
      (node (ref "E57") (pin "9") (pinfunction "I0_9") (pintype "input"))
      (node (ref "E63") (pin "11") (pinfunction "CLK_11") (pintype "input"))
      (node (ref "E63") (pin "3") (pinfunction "CLK_3") (pintype "input"))
      (node (ref "E65") (pin "3") (pinfunction "CLK_3") (pintype "input"))
      (node (ref "E73") (pin "7") (pinfunction "CLK_7") (pintype "input"))
      (node (ref "E90") (pin "7") (pinfunction "CLK_7") (pintype "input"))
    )
    (net (code "254") (name "P3_BTS3") (class "Default")
      (node (ref "E20") (pin "12") (pinfunction "I1_12") (pintype "input"))
      (node (ref "E26") (pin "4") (pinfunction "1C,2C_4") (pintype "input"))
      (node (ref "E51") (pin "13") (pinfunction "O_13") (pintype "output"))
      (node (ref "E64") (pin "2") (pinfunction "I0_2") (pintype "input"))
      (node (ref "E64") (pin "3") (pinfunction "I1_3") (pintype "input"))
    )
    (net (code "255") (name "P3_BTS4") (class "Default")
      (node (ref "E20") (pin "2") (pinfunction "I0_2") (pintype "input"))
      (node (ref "E26") (pin "3") (pinfunction "2D_3") (pintype "input"))
      (node (ref "E51") (pin "3") (pinfunction "O_3") (pintype "output"))
      (node (ref "E6") (pin "10") (pinfunction "I1_10") (pintype "input"))
      (node (ref "E74") (pin "4") (pinfunction "A3_4") (pintype "input"))
      (node (ref "E81") (pin "21") (pinfunction "I14_21") (pintype "input"))
      (node (ref "E92") (pin "1") (pinfunction "I0_1") (pintype "input"))
    )
    (net (code "256") (name "P3_INIOEN") (class "Default")
      (node (ref "E14") (pin "10") (pinfunction "O7_10") (pintype "tri_state"))
      (node (ref "E36") (pin "13") (pinfunction "I3_13") (pintype "input"))
      (node (ref "E36") (pin "5") (pinfunction "I3_5") (pintype "input"))
      (node (ref "E43") (pin "5") (pinfunction "I3_5") (pintype "input"))
    )
    (net (code "257") (name "P3_MBK") (class "Default")
      (node (ref "E19") (pin "2") (pinfunction "I0_2") (pintype "input"))
      (node (ref "E19") (pin "3") (pinfunction "I1_3") (pintype "input"))
      (node (ref "E19") (pin "5") (pinfunction "I0_5") (pintype "input"))
      (node (ref "E19") (pin "6") (pinfunction "I1_6") (pintype "input"))
      (node (ref "E20") (pin "3") (pinfunction "I1_3") (pintype "input"))
      (node (ref "E4") (pin "11") (pinfunction "I0_11") (pintype "input"))
      (node (ref "E4") (pin "12") (pinfunction "I1_12") (pintype "input"))
      (node (ref "E6") (pin "9") (pinfunction "I0_9") (pintype "input"))
      (node (ref "E60") (pin "9") (pinfunction "Q_9") (pintype "output"))
    )
    (net (code "258") (name "P4_3V") (class "Default")
      (node (ref "E76") (pin "1") (pinfunction "CLR_1") (pintype "input"))
      (node (ref "R18") (pin "1") (pinfunction "1_1") (pintype "passive"))
    )
    (net (code "259") (name "P4_BTS1") (class "Default")
      (node (ref "E20") (pin "5") (pinfunction "I0_5") (pintype "input"))
      (node (ref "E41") (pin "13") (pinfunction "O_13") (pintype "output"))
      (node (ref "E92") (pin "10") (pinfunction "I1_10") (pintype "input"))
      (node (ref "E92") (pin "5") (pinfunction "I2_5") (pintype "input"))
      (node (ref "E94") (pin "2") (pinfunction "I1_2") (pintype "input"))
    )
    (net (code "260") (name "P4_CKDB") (class "Default")
      (node (ref "E108") (pin "9") (pinfunction "CLK_9") (pintype "input"))
      (node (ref "E69") (pin "13") (pinfunction "F3_13") (pintype "output"))
    )
    (net (code "261") (name "P4_CKDF") (class "Default")
      (node (ref "E102") (pin "9") (pinfunction "CLK_9") (pintype "input"))
      (node (ref "E79") (pin "3") (pinfunction "F0_3") (pintype "output"))
    )
    (net (code "262") (name "P4_CKIBB") (class "Default")
      (node (ref "E116") (pin "9") (pinfunction "CLK_9") (pintype "input"))
      (node (ref "E79") (pin "12") (pinfunction "F2_12") (pintype "output"))
    )
    (net (code "263") (name "P4_CKIF") (class "Default")
      (node (ref "E110") (pin "9") (pinfunction "CLK_9") (pintype "input"))
      (node (ref "E79") (pin "4") (pinfunction "F1_4") (pintype "output"))
      (node (ref "E93") (pin "9") (pinfunction "CLK_9") (pintype "input"))
    )
    (net (code "264") (name "P4_CKIFB") (class "Default")
      (node (ref "E79") (pin "13") (pinfunction "F3_13") (pintype "output"))
      (node (ref "E97") (pin "7") (pinfunction "CLK_7") (pintype "input"))
    )
    (net (code "265") (name "P4_CKSV") (class "Default")
      (node (ref "E103") (pin "9") (pinfunction "CLK_9") (pintype "input"))
      (node (ref "E117") (pin "9") (pinfunction "CLK_9") (pintype "input"))
      (node (ref "E58") (pin "4") (pinfunction "O_4") (pintype "output"))
      (node (ref "E59") (pin "3") (pinfunction "CLK_3") (pintype "input"))
    )
    (net (code "266") (name "P4_CKUF") (class "Default")
      (node (ref "E59") (pin "11") (pinfunction "CLK_11") (pintype "input"))
      (node (ref "E69") (pin "4") (pinfunction "F1_4") (pintype "output"))
    )
    (net (code "267") (name "P4_CKUFB") (class "Default")
      (node (ref "E60") (pin "3") (pinfunction "CLK_3") (pintype "input"))
      (node (ref "E69") (pin "12") (pinfunction "F2_12") (pintype "output"))
    )
    (net (code "268") (name "P4_DFEN") (class "Default")
      (node (ref "E66") (pin "12") (pinfunction "I0_12") (pintype "input"))
      (node (ref "E74") (pin "1") (pinfunction "A6_1") (pintype "input"))
      (node (ref "E76") (pin "8") (pinfunction "~{Q}_8") (pintype "output"))
      (node (ref "E94") (pin "4") (pinfunction "I0_4") (pintype "input"))
    )
    (net (code "269") (name "P4_FATAL(0)") (class "Default")
      (node (ref "E32") (pin "5") (pinfunction "Q_5") (pintype "output"))
      (node (ref "E83") (pin "12") (pinfunction "A1_12") (pintype "input"))
    )
    (net (code "270") (name "P4_INIT_EN") (class "Default")
      (node (ref "E76") (pin "6") (pinfunction "~{Q}_6") (pintype "output"))
      (node (ref "E94") (pin "5") (pinfunction "I1_5") (pintype "input"))
    )
    (net (code "271") (name "P4_INT") (class "Default")
      (node (ref "E115") (pin "3") (pinfunction "I_3") (pintype "input"))
      (node (ref "E29") (pin "4") (pinfunction "O_4") (pintype "output"))
      (node (ref "E57") (pin "10") (pinfunction "I1_10") (pintype "input"))
      (node (ref "E97") (pin "1") (pinfunction "M_1") (pintype "input"))
    )
    (net (code "272") (name "P4_INT_IN") (class "Default")
      (node (ref "E38") (pin "5") (pinfunction "I1_5") (pintype "input"))
      (node (ref "E4") (pin "5") (pinfunction "I0_5") (pintype "input"))
      (node (ref "E77") (pin "5") (pinfunction "Q_5") (pintype "output"))
    )
    (net (code "273") (name "P4_INT_IN_PROG") (class "Default")
      (node (ref "E29") (pin "5") (pinfunction "I0_5") (pintype "input"))
      (node (ref "E3") (pin "2") (pinfunction "O_2") (pintype "output"))
    )
    (net (code "274") (name "P4_JMP+JMS") (class "Default")
      (node (ref "E58") (pin "9") (pinfunction "I_9") (pintype "input"))
      (node (ref "E61") (pin "2") (pinfunction "O_2") (pintype "output"))
      (node (ref "E70") (pin "1") (pinfunction "I0_1") (pintype "input"))
    )
    (net (code "275") (name "P4_LXA") (class "Default")
      (node (ref "E39") (pin "11") (pinfunction "I_11") (pintype "input"))
      (node (ref "E48") (pin "11") (pinfunction "I0_11") (pintype "input"))
      (node (ref "E51") (pin "14") (pinfunction "O_14") (pintype "output"))
      (node (ref "E57") (pin "4") (pinfunction "I0_4") (pintype "input"))
      (node (ref "E61") (pin "10") (pinfunction "I1_10") (pintype "input"))
      (node (ref "E61") (pin "11") (pinfunction "I0_11") (pintype "input"))
    )
    (net (code "276") (name "P4_NEW_FLD") (class "Default")
      (node (ref "E115") (pin "1") (pinfunction "I_1") (pintype "input"))
      (node (ref "E115") (pin "11") (pinfunction "I_11") (pintype "input"))
      (node (ref "E18") (pin "10") (pinfunction "I1_10") (pintype "input"))
      (node (ref "E18") (pin "2") (pinfunction "I1_2") (pintype "input"))
      (node (ref "E56") (pin "2") (pinfunction "I1_2") (pintype "input"))
      (node (ref "E70") (pin "6") (pinfunction "O_6") (pintype "output"))
      (node (ref "E80") (pin "10") (pinfunction "A0_10") (pintype "input"))
    )
    (net (code "277") (name "P4_PCLR") (class "Default")
      (node (ref "E1") (pin "15") (pinfunction "CLR_15") (pintype "input"))
      (node (ref "E121") (pin "15") (pinfunction "CLR_15") (pintype "input"))
      (node (ref "E73") (pin "15") (pinfunction "CLR_15") (pintype "input"))
      (node (ref "PAD1") (pin "1") (pinfunction "P_1") (pintype "passive"))
    )
    (net (code "278") (name "P4_PLXA") (class "Default")
      (node (ref "E1") (pin "7") (pinfunction "CLK_7") (pintype "input"))
      (node (ref "E121") (pin "7") (pinfunction "CLK_7") (pintype "input"))
      (node (ref "E122") (pin "7") (pinfunction "CLK_7") (pintype "input"))
      (node (ref "E58") (pin "2") (pinfunction "O_2") (pintype "output"))
      (node (ref "E65") (pin "1") (pinfunction "CLR_1") (pintype "input"))
    )
    (net (code "279") (name "P4_USINT") (class "Default")
      (node (ref "E32") (pin "4") (pinfunction "PRE_4") (pintype "input"))
      (node (ref "E32") (pin "8") (pinfunction "~{Q}_8") (pintype "output"))
      (node (ref "E38") (pin "4") (pinfunction "I0_4") (pintype "input"))
      (node (ref "E42") (pin "11") (pinfunction "I0_11") (pintype "input"))
      (node (ref "E42") (pin "12") (pinfunction "I1_12") (pintype "input"))
      (node (ref "E42") (pin "5") (pinfunction "I0_5") (pintype "input"))
    )
    (net (code "280") (name "P6_BIND2") (class "Default")
      (node (ref "E20") (pin "6") (pinfunction "I1_6") (pintype "input"))
      (node (ref "E72") (pin "2") (pinfunction "O_2") (pintype "output"))
      (node (ref "E92") (pin "11") (pinfunction "I2_11") (pintype "input"))
      (node (ref "E92") (pin "4") (pinfunction "I1_4") (pintype "input"))
      (node (ref "E94") (pin "1") (pinfunction "I0_1") (pintype "input"))
    )
    (net (code "281") (name "P6_DIOI") (class "Default")
      (node (ref "E14") (pin "9") (pinfunction "I0_9") (pintype "input"))
      (node (ref "E46") (pin "15") (pinfunction "Q4_15") (pintype "output"))
    )
    (net (code "282") (name "P6_EBM") (class "Default")
      (node (ref "E46") (pin "10") (pinfunction "Q3_10") (pintype "output"))
      (node (ref "E74") (pin "6") (pinfunction "A1_6") (pintype "input"))
    )
    (net (code "283") (name "P6_EEM") (class "Default")
      (node (ref "E14") (pin "7") (pinfunction "I2_7") (pintype "input"))
      (node (ref "E35") (pin "15") (pinfunction "Q4_15") (pintype "output"))
      (node (ref "E47") (pin "8") (pinfunction "I0_8") (pintype "input"))
    )
    (net (code "284") (name "P6_EN5") (class "Default")
      (node (ref "E28") (pin "1") (pinfunction "A6_1") (pintype "input"))
      (node (ref "E35") (pin "10") (pinfunction "Q3_10") (pintype "output"))
    )
    (net (code "285") (name "P6_EN9") (class "Default")
      (node (ref "E28") (pin "2") (pinfunction "A5_2") (pintype "input"))
      (node (ref "E35") (pin "7") (pinfunction "Q2_7") (pintype "output"))
    )
    (net (code "286") (name "P6_MAINT") (class "Default")
      (node (ref "E18") (pin "9") (pinfunction "I0_9") (pintype "input"))
      (node (ref "E48") (pin "1") (pinfunction "O_1") (pintype "output"))
      (node (ref "E56") (pin "1") (pinfunction "I0_1") (pintype "input"))
    )
    (net (code "287") (name "P6_PRUP") (class "Default")
      (node (ref "E55") (pin "1") (pinfunction "1G_1") (pintype "input"))
      (node (ref "E64") (pin "8") (pinfunction "I0_8") (pintype "input"))
      (node (ref "E65") (pin "6") (pinfunction "~{Q}_6") (pintype "output"))
    )
    (net (code "288") (name "P6_RVFEN") (class "Default")
      (node (ref "E14") (pin "6") (pinfunction "I3_6") (pintype "input"))
      (node (ref "E35") (pin "2") (pinfunction "Q1_2") (pintype "output"))
    )
    (net (code "289") (name "P6_USM") (class "Default")
      (node (ref "E111") (pin "14") (pinfunction "A8_14") (pintype "input"))
      (node (ref "E112") (pin "1") (pinfunction "A6_1") (pintype "input"))
      (node (ref "E112") (pin "14") (pinfunction "A8_14") (pintype "input"))
      (node (ref "E113") (pin "15") (pinfunction "A7_15") (pintype "input"))
      (node (ref "E114") (pin "14") (pinfunction "A8_14") (pintype "input"))
      (node (ref "E14") (pin "8") (pinfunction "I1_8") (pintype "input"))
      (node (ref "E30") (pin "12") (pinfunction "I7_12") (pintype "input"))
      (node (ref "E49") (pin "9") (pinfunction "I0_9") (pintype "input"))
      (node (ref "E59") (pin "8") (pinfunction "~{Q}_8") (pintype "output"))
      (node (ref "E8") (pin "3") (pinfunction "I1_3") (pintype "input"))
      (node (ref "E8") (pin "6") (pinfunction "I1_6") (pintype "input"))
      (node (ref "E87") (pin "15") (pinfunction "A7_15") (pintype "input"))
    )
    (net (code "290") (name "PULSE_LA") (class "Default")
      (node (ref "E53") (pin "5") (pinfunction "I1_5") (pintype "input"))
      (node (ref "U$1") (pin "DR2") (pinfunction "1_DR2") (pintype "bidirectional"))
    )
    (net (code "291") (name "TP1") (class "Default")
      (node (ref "E53") (pin "7") (pinfunction "I1_7") (pintype "input"))
      (node (ref "U$1") (pin "CD2") (pinfunction "1_CD2") (pintype "bidirectional"))
    )
    (net (code "292") (name "TP2") (class "Default")
      (node (ref "E53") (pin "10") (pinfunction "I1_10") (pintype "input"))
      (node (ref "U$1") (pin "CE2") (pinfunction "1_CE2") (pintype "bidirectional"))
    )
    (net (code "293") (name "TP3") (class "Default")
      (node (ref "E51") (pin "7") (pinfunction "I1_7") (pintype "input"))
      (node (ref "U$1") (pin "CH2") (pinfunction "1_CH2") (pintype "bidirectional"))
    )
    (net (code "294") (name "TP4") (class "Default")
      (node (ref "E27") (pin "1") (pinfunction "I0_1") (pintype "input"))
      (node (ref "E27") (pin "13") (pinfunction "I2_13") (pintype "input"))
      (node (ref "E27") (pin "2") (pinfunction "I1_2") (pintype "input"))
      (node (ref "U$1") (pin "CJ2") (pinfunction "1_CJ2") (pintype "bidirectional"))
    )
    (net (code "295") (name "VCC") (class "Default")
      (node (ref "C1") (pin "+") (pinfunction "+_+") (pintype "passive"))
      (node (ref "C10") (pin "1") (pinfunction "1_1") (pintype "passive"))
      (node (ref "C11") (pin "1") (pinfunction "1_1") (pintype "passive"))
      (node (ref "C13") (pin "1") (pinfunction "1_1") (pintype "passive"))
      (node (ref "C14") (pin "+") (pinfunction "+_+") (pintype "passive"))
      (node (ref "C15") (pin "1") (pinfunction "1_1") (pintype "passive"))
      (node (ref "C16") (pin "+") (pinfunction "+_+") (pintype "passive"))
      (node (ref "C17") (pin "1") (pinfunction "1_1") (pintype "passive"))
      (node (ref "C18") (pin "1") (pinfunction "1_1") (pintype "passive"))
      (node (ref "C2") (pin "1") (pinfunction "1_1") (pintype "passive"))
      (node (ref "C20") (pin "1") (pinfunction "1_1") (pintype "passive"))
      (node (ref "C21") (pin "1") (pinfunction "1_1") (pintype "passive"))
      (node (ref "C22") (pin "1") (pinfunction "1_1") (pintype "passive"))
      (node (ref "C23") (pin "1") (pinfunction "1_1") (pintype "passive"))
      (node (ref "C24") (pin "+") (pinfunction "+_+") (pintype "passive"))
      (node (ref "C25") (pin "1") (pinfunction "1_1") (pintype "passive"))
      (node (ref "C26") (pin "1") (pinfunction "1_1") (pintype "passive"))
      (node (ref "C27") (pin "1") (pinfunction "1_1") (pintype "passive"))
      (node (ref "C28") (pin "1") (pinfunction "1_1") (pintype "passive"))
      (node (ref "C29") (pin "1") (pinfunction "1_1") (pintype "passive"))
      (node (ref "C3") (pin "1") (pinfunction "1_1") (pintype "passive"))
      (node (ref "C31") (pin "1") (pinfunction "1_1") (pintype "passive"))
      (node (ref "C32") (pin "1") (pinfunction "1_1") (pintype "passive"))
      (node (ref "C33") (pin "1") (pinfunction "1_1") (pintype "passive"))
      (node (ref "C34") (pin "1") (pinfunction "1_1") (pintype "passive"))
      (node (ref "C35") (pin "1") (pinfunction "1_1") (pintype "passive"))
      (node (ref "C36") (pin "1") (pinfunction "1_1") (pintype "passive"))
      (node (ref "C4") (pin "1") (pinfunction "1_1") (pintype "passive"))
      (node (ref "C5") (pin "1") (pinfunction "1_1") (pintype "passive"))
      (node (ref "C6") (pin "1") (pinfunction "1_1") (pintype "passive"))
      (node (ref "C7") (pin "1") (pinfunction "1_1") (pintype "passive"))
      (node (ref "C8") (pin "+") (pinfunction "+_+") (pintype "passive"))
      (node (ref "C9") (pin "1") (pinfunction "1_1") (pintype "passive"))
      (node (ref "E101") (pin "16") (pinfunction "+UB_16") (pintype "power_in"))
      (node (ref "E26") (pin "5") (pinfunction "+UB_5") (pintype "power_in"))
      (node (ref "E83") (pin "16") (pinfunction "+UB_16") (pintype "power_in"))
      (node (ref "R1") (pin "1") (pinfunction "1_1") (pintype "passive"))
      (node (ref "R10") (pin "2") (pinfunction "2_2") (pintype "passive"))
      (node (ref "R11") (pin "2") (pinfunction "2_2") (pintype "passive"))
      (node (ref "R12") (pin "1") (pinfunction "1_1") (pintype "passive"))
      (node (ref "R13") (pin "2") (pinfunction "2_2") (pintype "passive"))
      (node (ref "R14") (pin "2") (pinfunction "2_2") (pintype "passive"))
      (node (ref "R15") (pin "2") (pinfunction "2_2") (pintype "passive"))
      (node (ref "R16") (pin "2") (pinfunction "2_2") (pintype "passive"))
      (node (ref "R17") (pin "2") (pinfunction "2_2") (pintype "passive"))
      (node (ref "R18") (pin "2") (pinfunction "2_2") (pintype "passive"))
      (node (ref "R19") (pin "2") (pinfunction "2_2") (pintype "passive"))
      (node (ref "R2") (pin "1") (pinfunction "1_1") (pintype "passive"))
      (node (ref "R21") (pin "2") (pinfunction "2_2") (pintype "passive"))
      (node (ref "R22") (pin "2") (pinfunction "2_2") (pintype "passive"))
      (node (ref "R23") (pin "2") (pinfunction "2_2") (pintype "passive"))
      (node (ref "R24") (pin "1") (pinfunction "1_1") (pintype "passive"))
      (node (ref "R25") (pin "1") (pinfunction "1_1") (pintype "passive"))
      (node (ref "R26") (pin "1") (pinfunction "1_1") (pintype "passive"))
      (node (ref "R27") (pin "1") (pinfunction "1_1") (pintype "passive"))
      (node (ref "R28") (pin "2") (pinfunction "2_2") (pintype "passive"))
      (node (ref "R29") (pin "2") (pinfunction "2_2") (pintype "passive"))
      (node (ref "R3") (pin "2") (pinfunction "2_2") (pintype "passive"))
      (node (ref "R30") (pin "2") (pinfunction "2_2") (pintype "passive"))
      (node (ref "R31") (pin "1") (pinfunction "1_1") (pintype "passive"))
      (node (ref "R32") (pin "2") (pinfunction "2_2") (pintype "passive"))
      (node (ref "R33") (pin "2") (pinfunction "2_2") (pintype "passive"))
      (node (ref "R34") (pin "2") (pinfunction "2_2") (pintype "passive"))
      (node (ref "R35") (pin "2") (pinfunction "2_2") (pintype "passive"))
      (node (ref "R36") (pin "2") (pinfunction "2_2") (pintype "passive"))
      (node (ref "R37") (pin "2") (pinfunction "2_2") (pintype "passive"))
      (node (ref "R38") (pin "2") (pinfunction "2_2") (pintype "passive"))
      (node (ref "R39") (pin "2") (pinfunction "2_2") (pintype "passive"))
      (node (ref "R4") (pin "2") (pinfunction "2_2") (pintype "passive"))
      (node (ref "R6") (pin "1") (pinfunction "1_1") (pintype "passive"))
      (node (ref "R7") (pin "1") (pinfunction "1_1") (pintype "passive"))
      (node (ref "R8") (pin "1") (pinfunction "1_1") (pintype "passive"))
      (node (ref "R9") (pin "1") (pinfunction "1_1") (pintype "passive"))
      (node (ref "U$1") (pin "AA2") (pinfunction "1_AA2") (pintype "bidirectional"))
      (node (ref "U$1") (pin "BA2") (pinfunction "1_BA2") (pintype "bidirectional"))
      (node (ref "U$1") (pin "CA2") (pinfunction "1_CA2") (pintype "bidirectional"))
    )
    (net (code "296") (name "unconnected-(E1A-D1-Pad14)") (class "Default")
      (node (ref "E1") (pin "14") (pinfunction "D1_14") (pintype "input"))
    )
    (net (code "297") (name "unconnected-(E1A-Q1-Pad3)") (class "Default")
      (node (ref "E1") (pin "3") (pinfunction "Q1_3") (pintype "tri_state"))
    )
    (net (code "298") (name "unconnected-(E2E-I-Pad11)") (class "Default")
      (node (ref "E2") (pin "11") (pinfunction "I_11") (pintype "input"))
    )
    (net (code "299") (name "unconnected-(E2E-O-Pad10)") (class "Default")
      (node (ref "E2") (pin "10") (pinfunction "O_10") (pintype "output"))
    )
    (net (code "300") (name "unconnected-(E2F-I-Pad13)") (class "Default")
      (node (ref "E2") (pin "13") (pinfunction "I_13") (pintype "input"))
    )
    (net (code "301") (name "unconnected-(E2F-O-Pad12)") (class "Default")
      (node (ref "E2") (pin "12") (pinfunction "O_12") (pintype "output"))
    )
    (net (code "302") (name "unconnected-(E3C-I0-Pad9)") (class "Default")
      (node (ref "E3") (pin "9") (pinfunction "I0_9") (pintype "input"))
    )
    (net (code "303") (name "unconnected-(E3C-I1-Pad10)") (class "Default")
      (node (ref "E3") (pin "10") (pinfunction "I1_10") (pintype "input"))
    )
    (net (code "304") (name "unconnected-(E3C-O-Pad14)") (class "Default")
      (node (ref "E3") (pin "14") (pinfunction "O_14") (pintype "output"))
    )
    (net (code "305") (name "unconnected-(E4A-I0-Pad2)") (class "Default")
      (node (ref "E4") (pin "2") (pinfunction "I0_2") (pintype "input"))
    )
    (net (code "306") (name "unconnected-(E4A-I1-Pad3)") (class "Default")
      (node (ref "E4") (pin "3") (pinfunction "I1_3") (pintype "input"))
    )
    (net (code "307") (name "unconnected-(E4A-O-Pad1)") (class "Default")
      (node (ref "E4") (pin "1") (pinfunction "O_1") (pintype "open_collector"))
    )
    (net (code "308") (name "unconnected-(E6B-I0-Pad4)") (class "Default")
      (node (ref "E6") (pin "4") (pinfunction "I0_4") (pintype "input"))
    )
    (net (code "309") (name "unconnected-(E6B-I1-Pad5)") (class "Default")
      (node (ref "E6") (pin "5") (pinfunction "I1_5") (pintype "input"))
    )
    (net (code "310") (name "unconnected-(E6B-O-Pad6)") (class "Default")
      (node (ref "E6") (pin "6") (pinfunction "O_6") (pintype "output"))
    )
    (net (code "311") (name "unconnected-(E9B-I0-Pad9)") (class "Default")
      (node (ref "E9") (pin "9") (pinfunction "I0_9") (pintype "input"))
    )
    (net (code "312") (name "unconnected-(E9B-I1-Pad10)") (class "Default")
      (node (ref "E9") (pin "10") (pinfunction "I1_10") (pintype "input"))
    )
    (net (code "313") (name "unconnected-(E9B-I2-Pad12)") (class "Default")
      (node (ref "E9") (pin "12") (pinfunction "I2_12") (pintype "input"))
    )
    (net (code "314") (name "unconnected-(E9B-I3-Pad13)") (class "Default")
      (node (ref "E9") (pin "13") (pinfunction "I3_13") (pintype "input"))
    )
    (net (code "315") (name "unconnected-(E9B-O-Pad8)") (class "Default")
      (node (ref "E9") (pin "8") (pinfunction "O_8") (pintype "output"))
    )
    (net (code "316") (name "unconnected-(E10-Pad1)") (class "Default")
      (node (ref "E10") (pin "1") (pinfunction "1_1") (pintype "passive"))
    )
    (net (code "317") (name "unconnected-(E10-Pad2)") (class "Default")
      (node (ref "E10") (pin "2") (pinfunction "2_2") (pintype "passive"))
    )
    (net (code "318") (name "unconnected-(E10-Pad3)") (class "Default")
      (node (ref "E10") (pin "3") (pinfunction "3_3") (pintype "passive"))
    )
    (net (code "319") (name "unconnected-(E10-Pad4)") (class "Default")
      (node (ref "E10") (pin "4") (pinfunction "4_4") (pintype "passive"))
    )
    (net (code "320") (name "unconnected-(E10-Pad5)") (class "Default")
      (node (ref "E10") (pin "5") (pinfunction "5_5") (pintype "passive"))
    )
    (net (code "321") (name "unconnected-(E10-Pad6)") (class "Default")
      (node (ref "E10") (pin "6") (pinfunction "6_6") (pintype "passive"))
    )
    (net (code "322") (name "unconnected-(E10-Pad7)") (class "Default")
      (node (ref "E10") (pin "7") (pinfunction "7_7") (pintype "passive"))
    )
    (net (code "323") (name "unconnected-(E10-Pad8)") (class "Default")
      (node (ref "E10") (pin "8") (pinfunction "8_8") (pintype "passive"))
    )
    (net (code "324") (name "unconnected-(E10-Pad9)") (class "Default")
      (node (ref "E10") (pin "9") (pinfunction "9_9") (pintype "passive"))
    )
    (net (code "325") (name "unconnected-(E10-Pad10)") (class "Default")
      (node (ref "E10") (pin "10") (pinfunction "10_10") (pintype "passive"))
    )
    (net (code "326") (name "unconnected-(E10-Pad11)") (class "Default")
      (node (ref "E10") (pin "11") (pinfunction "11_11") (pintype "passive"))
    )
    (net (code "327") (name "unconnected-(E10-Pad12)") (class "Default")
      (node (ref "E10") (pin "12") (pinfunction "12_12") (pintype "passive"))
    )
    (net (code "328") (name "unconnected-(E10-Pad13)") (class "Default")
      (node (ref "E10") (pin "13") (pinfunction "13_13") (pintype "passive"))
    )
    (net (code "329") (name "unconnected-(E10-Pad14)") (class "Default")
      (node (ref "E10") (pin "14") (pinfunction "14_14") (pintype "passive"))
    )
    (net (code "330") (name "unconnected-(E10-Pad15)") (class "Default")
      (node (ref "E10") (pin "15") (pinfunction "15_15") (pintype "passive"))
    )
    (net (code "331") (name "unconnected-(E10-Pad16)") (class "Default")
      (node (ref "E10") (pin "16") (pinfunction "16_16") (pintype "passive"))
    )
    (net (code "332") (name "unconnected-(E20C-I0-Pad8)") (class "Default")
      (node (ref "E20") (pin "8") (pinfunction "I0_8") (pintype "input"))
    )
    (net (code "333") (name "unconnected-(E20C-I1-Pad9)") (class "Default")
      (node (ref "E20") (pin "9") (pinfunction "I1_9") (pintype "input"))
    )
    (net (code "334") (name "unconnected-(E20C-O-Pad10)") (class "Default")
      (node (ref "E20") (pin "10") (pinfunction "O_10") (pintype "open_collector"))
    )
    (net (code "335") (name "unconnected-(E21B-I0-Pad3)") (class "Default")
      (node (ref "E21") (pin "3") (pinfunction "I0_3") (pintype "input"))
    )
    (net (code "336") (name "unconnected-(E21B-I1-Pad4)") (class "Default")
      (node (ref "E21") (pin "4") (pinfunction "I1_4") (pintype "input"))
    )
    (net (code "337") (name "unconnected-(E21B-I2-Pad5)") (class "Default")
      (node (ref "E21") (pin "5") (pinfunction "I2_5") (pintype "input"))
    )
    (net (code "338") (name "unconnected-(E21B-O-Pad6)") (class "Default")
      (node (ref "E21") (pin "6") (pinfunction "O_6") (pintype "output"))
    )
    (net (code "339") (name "unconnected-(E26C-1D-Pad6)") (class "Default")
      (node (ref "E26") (pin "6") (pinfunction "1D_6") (pintype "input"))
    )
    (net (code "340") (name "unconnected-(E26C-1Q-Pad10)") (class "Default")
      (node (ref "E26") (pin "10") (pinfunction "1Q_10") (pintype "output"))
    )
    (net (code "341") (name "unconnected-(E26C-2Q-Pad9)") (class "Default")
      (node (ref "E26") (pin "9") (pinfunction "2Q_9") (pintype "output"))
    )
    (net (code "342") (name "unconnected-(E26C-~{1Q}-Pad11)") (class "Default")
      (node (ref "E26") (pin "11") (pinfunction "~{1Q}_11") (pintype "output"))
    )
    (net (code "343") (name "unconnected-(E26D-~{1Q}-Pad1)") (class "Default")
      (node (ref "E26") (pin "1") (pinfunction "~{1Q}_1") (pintype "output"))
    )
    (net (code "344") (name "unconnected-(E26D-~{2Q}-Pad14)") (class "Default")
      (node (ref "E26") (pin "14") (pinfunction "~{2Q}_14") (pintype "output"))
    )
    (net (code "345") (name "unconnected-(E31A-0-Pad1)") (class "Default")
      (node (ref "E31") (pin "1") (pinfunction "0_1") (pintype "output"))
    )
    (net (code "346") (name "unconnected-(E32A-D-Pad2)") (class "Default")
      (node (ref "E32") (pin "2") (pinfunction "D_2") (pintype "input"))
    )
    (net (code "347") (name "unconnected-(E34A-O8-Pad10)") (class "Default")
      (node (ref "E34") (pin "10") (pinfunction "O8_10") (pintype "output"))
    )
    (net (code "348") (name "unconnected-(E34A-O9-Pad11)") (class "Default")
      (node (ref "E34") (pin "11") (pinfunction "O9_11") (pintype "output"))
    )
    (net (code "349") (name "unconnected-(E40-Pad1)") (class "Default")
      (node (ref "E40") (pin "1") (pinfunction "1_1") (pintype "passive"))
    )
    (net (code "350") (name "unconnected-(E40-Pad2)") (class "Default")
      (node (ref "E40") (pin "2") (pinfunction "2_2") (pintype "passive"))
    )
    (net (code "351") (name "unconnected-(E40-Pad3)") (class "Default")
      (node (ref "E40") (pin "3") (pinfunction "3_3") (pintype "passive"))
    )
    (net (code "352") (name "unconnected-(E40-Pad4)") (class "Default")
      (node (ref "E40") (pin "4") (pinfunction "4_4") (pintype "passive"))
    )
    (net (code "353") (name "unconnected-(E40-Pad5)") (class "Default")
      (node (ref "E40") (pin "5") (pinfunction "5_5") (pintype "passive"))
    )
    (net (code "354") (name "unconnected-(E40-Pad6)") (class "Default")
      (node (ref "E40") (pin "6") (pinfunction "6_6") (pintype "passive"))
    )
    (net (code "355") (name "unconnected-(E40-Pad7)") (class "Default")
      (node (ref "E40") (pin "7") (pinfunction "7_7") (pintype "passive"))
    )
    (net (code "356") (name "unconnected-(E40-Pad8)") (class "Default")
      (node (ref "E40") (pin "8") (pinfunction "8_8") (pintype "passive"))
    )
    (net (code "357") (name "unconnected-(E40-Pad9)") (class "Default")
      (node (ref "E40") (pin "9") (pinfunction "9_9") (pintype "passive"))
    )
    (net (code "358") (name "unconnected-(E40-Pad10)") (class "Default")
      (node (ref "E40") (pin "10") (pinfunction "10_10") (pintype "passive"))
    )
    (net (code "359") (name "unconnected-(E40-Pad11)") (class "Default")
      (node (ref "E40") (pin "11") (pinfunction "11_11") (pintype "passive"))
    )
    (net (code "360") (name "unconnected-(E40-Pad12)") (class "Default")
      (node (ref "E40") (pin "12") (pinfunction "12_12") (pintype "passive"))
    )
    (net (code "361") (name "unconnected-(E40-Pad13)") (class "Default")
      (node (ref "E40") (pin "13") (pinfunction "13_13") (pintype "passive"))
    )
    (net (code "362") (name "unconnected-(E40-Pad14)") (class "Default")
      (node (ref "E40") (pin "14") (pinfunction "14_14") (pintype "passive"))
    )
    (net (code "363") (name "unconnected-(E40-Pad15)") (class "Default")
      (node (ref "E40") (pin "15") (pinfunction "15_15") (pintype "passive"))
    )
    (net (code "364") (name "unconnected-(E40-Pad16)") (class "Default")
      (node (ref "E40") (pin "16") (pinfunction "16_16") (pintype "passive"))
    )
    (net (code "365") (name "unconnected-(E43B-I0-Pad9)") (class "Default")
      (node (ref "E43") (pin "9") (pinfunction "I0_9") (pintype "input"))
    )
    (net (code "366") (name "unconnected-(E43B-I1-Pad10)") (class "Default")
      (node (ref "E43") (pin "10") (pinfunction "I1_10") (pintype "input"))
    )
    (net (code "367") (name "unconnected-(E43B-I2-Pad12)") (class "Default")
      (node (ref "E43") (pin "12") (pinfunction "I2_12") (pintype "input"))
    )
    (net (code "368") (name "unconnected-(E43B-I3-Pad13)") (class "Default")
      (node (ref "E43") (pin "13") (pinfunction "I3_13") (pintype "input"))
    )
    (net (code "369") (name "unconnected-(E43B-O-Pad8)") (class "Default")
      (node (ref "E43") (pin "8") (pinfunction "O_8") (pintype "output"))
    )
    (net (code "370") (name "unconnected-(E46A-D1-Pad4)") (class "Default")
      (node (ref "E46") (pin "4") (pinfunction "D1_4") (pintype "input"))
    )
    (net (code "371") (name "unconnected-(E46A-Q1-Pad2)") (class "Default")
      (node (ref "E46") (pin "2") (pinfunction "Q1_2") (pintype "output"))
    )
    (net (code "372") (name "unconnected-(E46A-Q2-Pad7)") (class "Default")
      (node (ref "E46") (pin "7") (pinfunction "Q2_7") (pintype "output"))
    )
    (net (code "373") (name "unconnected-(E46A-~{Q1}-Pad3)") (class "Default")
      (node (ref "E46") (pin "3") (pinfunction "~{Q1}_3") (pintype "output"))
    )
    (net (code "374") (name "unconnected-(E55A-2A2-Pad14)") (class "Default")
      (node (ref "E55") (pin "14") (pinfunction "2A2_14") (pintype "input"))
    )
    (net (code "375") (name "unconnected-(E55A-2Y2-Pad13)") (class "Default")
      (node (ref "E55") (pin "13") (pinfunction "2Y2_13") (pintype "tri_state"))
    )
    (net (code "376") (name "unconnected-(E57D-I0-Pad12)") (class "Default")
      (node (ref "E57") (pin "12") (pinfunction "I0_12") (pintype "input"))
    )
    (net (code "377") (name "unconnected-(E57D-I1-Pad13)") (class "Default")
      (node (ref "E57") (pin "13") (pinfunction "I1_13") (pintype "input"))
    )
    (net (code "378") (name "unconnected-(E57D-O-Pad11)") (class "Default")
      (node (ref "E57") (pin "11") (pinfunction "O_11") (pintype "output"))
    )
    (net (code "379") (name "unconnected-(E59A-Q-Pad5)") (class "Default")
      (node (ref "E59") (pin "5") (pinfunction "Q_5") (pintype "output"))
    )
    (net (code "380") (name "unconnected-(E60A-Q-Pad5)") (class "Default")
      (node (ref "E60") (pin "5") (pinfunction "Q_5") (pintype "output"))
    )
    (net (code "381") (name "unconnected-(E60B-~{Q}-Pad8)") (class "Default")
      (node (ref "E60") (pin "8") (pinfunction "~{Q}_8") (pintype "output"))
    )
    (net (code "382") (name "unconnected-(E62A-D1-Pad14)") (class "Default")
      (node (ref "E62") (pin "14") (pinfunction "D1_14") (pintype "input"))
    )
    (net (code "383") (name "unconnected-(E62A-Q1-Pad3)") (class "Default")
      (node (ref "E62") (pin "3") (pinfunction "Q1_3") (pintype "tri_state"))
    )
    (net (code "384") (name "unconnected-(E64C-O-Pad10)") (class "Default")
      (node (ref "E64") (pin "10") (pinfunction "O_10") (pintype "output"))
    )
    (net (code "385") (name "unconnected-(E64D-I0-Pad11)") (class "Default")
      (node (ref "E64") (pin "11") (pinfunction "I0_11") (pintype "input"))
    )
    (net (code "386") (name "unconnected-(E64D-I1-Pad12)") (class "Default")
      (node (ref "E64") (pin "12") (pinfunction "I1_12") (pintype "input"))
    )
    (net (code "387") (name "unconnected-(E64D-O-Pad13)") (class "Default")
      (node (ref "E64") (pin "13") (pinfunction "O_13") (pintype "output"))
    )
    (net (code "388") (name "unconnected-(E65B-~{Q}-Pad8)") (class "Default")
      (node (ref "E65") (pin "8") (pinfunction "~{Q}_8") (pintype "output"))
    )
    (net (code "389") (name "unconnected-(E66C-I0-Pad9)") (class "Default")
      (node (ref "E66") (pin "9") (pinfunction "I0_9") (pintype "input"))
    )
    (net (code "390") (name "unconnected-(E66C-I1-Pad10)") (class "Default")
      (node (ref "E66") (pin "10") (pinfunction "I1_10") (pintype "input"))
    )
    (net (code "391") (name "unconnected-(E66C-O-Pad8)") (class "Default")
      (node (ref "E66") (pin "8") (pinfunction "O_8") (pintype "output"))
    )
    (net (code "392") (name "unconnected-(E68A-A<B_O-Pad7)") (class "Default")
      (node (ref "E68") (pin "7") (pinfunction "A<B_O_7") (pintype "output"))
    )
    (net (code "393") (name "unconnected-(E72C-I0-Pad9)") (class "Default")
      (node (ref "E72") (pin "9") (pinfunction "I0_9") (pintype "input"))
    )
    (net (code "394") (name "unconnected-(E72C-I1-Pad10)") (class "Default")
      (node (ref "E72") (pin "10") (pinfunction "I1_10") (pintype "input"))
    )
    (net (code "395") (name "unconnected-(E72C-O-Pad14)") (class "Default")
      (node (ref "E72") (pin "14") (pinfunction "O_14") (pintype "output"))
    )
    (net (code "396") (name "unconnected-(E72D-I0-Pad11)") (class "Default")
      (node (ref "E72") (pin "11") (pinfunction "I0_11") (pintype "input"))
    )
    (net (code "397") (name "unconnected-(E72D-I1-Pad12)") (class "Default")
      (node (ref "E72") (pin "12") (pinfunction "I1_12") (pintype "input"))
    )
    (net (code "398") (name "unconnected-(E72D-O-Pad13)") (class "Default")
      (node (ref "E72") (pin "13") (pinfunction "O_13") (pintype "output"))
    )
    (net (code "399") (name "unconnected-(E73A-D1-Pad14)") (class "Default")
      (node (ref "E73") (pin "14") (pinfunction "D1_14") (pintype "input"))
    )
    (net (code "400") (name "unconnected-(E73A-Q1-Pad3)") (class "Default")
      (node (ref "E73") (pin "3") (pinfunction "Q1_3") (pintype "tri_state"))
    )
    (net (code "401") (name "unconnected-(E75A-I0-Pad4)") (class "Default")
      (node (ref "E75") (pin "4") (pinfunction "I0_4") (pintype "input"))
    )
    (net (code "402") (name "unconnected-(E75A-I1-Pad5)") (class "Default")
      (node (ref "E75") (pin "5") (pinfunction "I1_5") (pintype "input"))
    )
    (net (code "403") (name "unconnected-(E75A-O-Pad3)") (class "Default")
      (node (ref "E75") (pin "3") (pinfunction "O_3") (pintype "output"))
    )
    (net (code "404") (name "unconnected-(E75C-I0-Pad9)") (class "Default")
      (node (ref "E75") (pin "9") (pinfunction "I0_9") (pintype "input"))
    )
    (net (code "405") (name "unconnected-(E75C-I1-Pad10)") (class "Default")
      (node (ref "E75") (pin "10") (pinfunction "I1_10") (pintype "input"))
    )
    (net (code "406") (name "unconnected-(E75C-O-Pad14)") (class "Default")
      (node (ref "E75") (pin "14") (pinfunction "O_14") (pintype "output"))
    )
    (net (code "407") (name "unconnected-(E75D-I0-Pad11)") (class "Default")
      (node (ref "E75") (pin "11") (pinfunction "I0_11") (pintype "input"))
    )
    (net (code "408") (name "unconnected-(E75D-I1-Pad12)") (class "Default")
      (node (ref "E75") (pin "12") (pinfunction "I1_12") (pintype "input"))
    )
    (net (code "409") (name "unconnected-(E75D-O-Pad13)") (class "Default")
      (node (ref "E75") (pin "13") (pinfunction "O_13") (pintype "output"))
    )
    (net (code "410") (name "unconnected-(E77B-CLK-Pad11)") (class "Default")
      (node (ref "E77") (pin "11") (pinfunction "CLK_11") (pintype "input"))
    )
    (net (code "411") (name "unconnected-(E77B-CLR-Pad13)") (class "Default")
      (node (ref "E77") (pin "13") (pinfunction "CLR_13") (pintype "input"))
    )
    (net (code "412") (name "unconnected-(E77B-D-Pad12)") (class "Default")
      (node (ref "E77") (pin "12") (pinfunction "D_12") (pintype "input"))
    )
    (net (code "413") (name "unconnected-(E77B-PRE-Pad10)") (class "Default")
      (node (ref "E77") (pin "10") (pinfunction "PRE_10") (pintype "input"))
    )
    (net (code "414") (name "unconnected-(E77B-Q-Pad9)") (class "Default")
      (node (ref "E77") (pin "9") (pinfunction "Q_9") (pintype "output"))
    )
    (net (code "415") (name "unconnected-(E77B-~{Q}-Pad8)") (class "Default")
      (node (ref "E77") (pin "8") (pinfunction "~{Q}_8") (pintype "output"))
    )
    (net (code "416") (name "unconnected-(E81A-O0-Pad18)") (class "Default")
      (node (ref "E81") (pin "18") (pinfunction "O0_18") (pintype "tri_state"))
    )
    (net (code "417") (name "unconnected-(E82A-D2-Pad10)") (class "Default")
      (node (ref "E82") (pin "10") (pinfunction "D2_10") (pintype "input"))
    )
    (net (code "418") (name "unconnected-(E82A-D3-Pad12)") (class "Default")
      (node (ref "E82") (pin "12") (pinfunction "D3_12") (pintype "input"))
    )
    (net (code "419") (name "unconnected-(E82A-Q2-Pad9)") (class "Default")
      (node (ref "E82") (pin "9") (pinfunction "Q2_9") (pintype "output"))
    )
    (net (code "420") (name "unconnected-(E82A-Q3-Pad11)") (class "Default")
      (node (ref "E82") (pin "11") (pinfunction "Q3_11") (pintype "output"))
    )
    (net (code "421") (name "unconnected-(E83D-A4-Pad10)") (class "Default")
      (node (ref "E83") (pin "10") (pinfunction "A4_10") (pintype "input"))
    )
    (net (code "422") (name "unconnected-(E83D-Y4-Pad9)") (class "Default")
      (node (ref "E83") (pin "9") (pinfunction "Y4_9") (pintype "tri_state"))
    )
    (net (code "423") (name "unconnected-(E84A-1A4-Pad10)") (class "Default")
      (node (ref "E84") (pin "10") (pinfunction "1A4_10") (pintype "input"))
    )
    (net (code "424") (name "unconnected-(E84A-1Y4-Pad9)") (class "Default")
      (node (ref "E84") (pin "9") (pinfunction "1Y4_9") (pintype "tri_state"))
    )
    (net (code "425") (name "unconnected-(E84A-2A1-Pad12)") (class "Default")
      (node (ref "E84") (pin "12") (pinfunction "2A1_12") (pintype "input"))
    )
    (net (code "426") (name "unconnected-(E84A-2A2-Pad14)") (class "Default")
      (node (ref "E84") (pin "14") (pinfunction "2A2_14") (pintype "input"))
    )
    (net (code "427") (name "unconnected-(E84A-2G-Pad15)") (class "Default")
      (node (ref "E84") (pin "15") (pinfunction "2G_15") (pintype "input"))
    )
    (net (code "428") (name "unconnected-(E84A-2Y1-Pad11)") (class "Default")
      (node (ref "E84") (pin "11") (pinfunction "2Y1_11") (pintype "tri_state"))
    )
    (net (code "429") (name "unconnected-(E84A-2Y2-Pad13)") (class "Default")
      (node (ref "E84") (pin "13") (pinfunction "2Y2_13") (pintype "tri_state"))
    )
    (net (code "430") (name "unconnected-(E85A-D2-Pad4)") (class "Default")
      (node (ref "E85") (pin "4") (pinfunction "D2_4") (pintype "input"))
    )
    (net (code "431") (name "unconnected-(E85A-Q2-Pad5)") (class "Default")
      (node (ref "E85") (pin "5") (pinfunction "Q2_5") (pintype "output"))
    )
    (net (code "432") (name "unconnected-(E86A-2A2-Pad14)") (class "Default")
      (node (ref "E86") (pin "14") (pinfunction "2A2_14") (pintype "input"))
    )
    (net (code "433") (name "unconnected-(E86A-2Y2-Pad13)") (class "Default")
      (node (ref "E86") (pin "13") (pinfunction "2Y2_13") (pintype "tri_state"))
    )
    (net (code "434") (name "unconnected-(E89A-EO-Pad15)") (class "Default")
      (node (ref "E89") (pin "15") (pinfunction "EO_15") (pintype "output"))
    )
    (net (code "435") (name "unconnected-(E89A-GS-Pad14)") (class "Default")
      (node (ref "E89") (pin "14") (pinfunction "GS_14") (pintype "output"))
    )
    (net (code "436") (name "unconnected-(E93A-D1-Pad4)") (class "Default")
      (node (ref "E93") (pin "4") (pinfunction "D1_4") (pintype "input"))
    )
    (net (code "437") (name "unconnected-(E93A-Q1-Pad2)") (class "Default")
      (node (ref "E93") (pin "2") (pinfunction "Q1_2") (pintype "output"))
    )
    (net (code "438") (name "unconnected-(E93A-~{Q1}-Pad3)") (class "Default")
      (node (ref "E93") (pin "3") (pinfunction "~{Q1}_3") (pintype "output"))
    )
    (net (code "439") (name "unconnected-(E94C-I0-Pad9)") (class "Default")
      (node (ref "E94") (pin "9") (pinfunction "I0_9") (pintype "input"))
    )
    (net (code "440") (name "unconnected-(E94C-I1-Pad10)") (class "Default")
      (node (ref "E94") (pin "10") (pinfunction "I1_10") (pintype "input"))
    )
    (net (code "441") (name "unconnected-(E94C-O-Pad8)") (class "Default")
      (node (ref "E94") (pin "8") (pinfunction "O_8") (pintype "output"))
    )
    (net (code "442") (name "unconnected-(E94D-I0-Pad12)") (class "Default")
      (node (ref "E94") (pin "12") (pinfunction "I0_12") (pintype "input"))
    )
    (net (code "443") (name "unconnected-(E94D-I1-Pad13)") (class "Default")
      (node (ref "E94") (pin "13") (pinfunction "I1_13") (pintype "input"))
    )
    (net (code "444") (name "unconnected-(E94D-O-Pad11)") (class "Default")
      (node (ref "E94") (pin "11") (pinfunction "O_11") (pintype "output"))
    )
    (net (code "445") (name "unconnected-(E97A-CLR-Pad15)") (class "Default")
      (node (ref "E97") (pin "15") (pinfunction "CLR_15") (pintype "input"))
    )
    (net (code "446") (name "unconnected-(E97A-D1-Pad14)") (class "Default")
      (node (ref "E97") (pin "14") (pinfunction "D1_14") (pintype "input"))
    )
    (net (code "447") (name "unconnected-(E97A-G1-Pad9)") (class "Default")
      (node (ref "E97") (pin "9") (pinfunction "G1_9") (pintype "input"))
    )
    (net (code "448") (name "unconnected-(E97A-G2-Pad10)") (class "Default")
      (node (ref "E97") (pin "10") (pinfunction "G2_10") (pintype "input"))
    )
    (net (code "449") (name "unconnected-(E97A-Q1-Pad3)") (class "Default")
      (node (ref "E97") (pin "3") (pinfunction "Q1_3") (pintype "tri_state"))
    )
    (net (code "450") (name "unconnected-(E101D-A4-Pad10)") (class "Default")
      (node (ref "E101") (pin "10") (pinfunction "A4_10") (pintype "input"))
    )
    (net (code "451") (name "unconnected-(E101D-Y4-Pad9)") (class "Default")
      (node (ref "E101") (pin "9") (pinfunction "Y4_9") (pintype "tri_state"))
    )
    (net (code "452") (name "unconnected-(E102A-D1-Pad4)") (class "Default")
      (node (ref "E102") (pin "4") (pinfunction "D1_4") (pintype "input"))
    )
    (net (code "453") (name "unconnected-(E102A-Q1-Pad2)") (class "Default")
      (node (ref "E102") (pin "2") (pinfunction "Q1_2") (pintype "output"))
    )
    (net (code "454") (name "unconnected-(E102A-~{Q1}-Pad3)") (class "Default")
      (node (ref "E102") (pin "3") (pinfunction "~{Q1}_3") (pintype "output"))
    )
    (net (code "455") (name "unconnected-(E104A-1A4-Pad10)") (class "Default")
      (node (ref "E104") (pin "10") (pinfunction "1A4_10") (pintype "input"))
    )
    (net (code "456") (name "unconnected-(E104A-1Y4-Pad9)") (class "Default")
      (node (ref "E104") (pin "9") (pinfunction "1Y4_9") (pintype "tri_state"))
    )
    (net (code "457") (name "unconnected-(E104A-2A1-Pad12)") (class "Default")
      (node (ref "E104") (pin "12") (pinfunction "2A1_12") (pintype "input"))
    )
    (net (code "458") (name "unconnected-(E104A-2A2-Pad14)") (class "Default")
      (node (ref "E104") (pin "14") (pinfunction "2A2_14") (pintype "input"))
    )
    (net (code "459") (name "unconnected-(E104A-2G-Pad15)") (class "Default")
      (node (ref "E104") (pin "15") (pinfunction "2G_15") (pintype "input"))
    )
    (net (code "460") (name "unconnected-(E104A-2Y1-Pad11)") (class "Default")
      (node (ref "E104") (pin "11") (pinfunction "2Y1_11") (pintype "tri_state"))
    )
    (net (code "461") (name "unconnected-(E104A-2Y2-Pad13)") (class "Default")
      (node (ref "E104") (pin "13") (pinfunction "2Y2_13") (pintype "tri_state"))
    )
    (net (code "462") (name "unconnected-(E108A-D1-Pad4)") (class "Default")
      (node (ref "E108") (pin "4") (pinfunction "D1_4") (pintype "input"))
    )
    (net (code "463") (name "unconnected-(E108A-D2-Pad5)") (class "Default")
      (node (ref "E108") (pin "5") (pinfunction "D2_5") (pintype "input"))
    )
    (net (code "464") (name "unconnected-(E108A-Q1-Pad2)") (class "Default")
      (node (ref "E108") (pin "2") (pinfunction "Q1_2") (pintype "output"))
    )
    (net (code "465") (name "unconnected-(E108A-Q2-Pad7)") (class "Default")
      (node (ref "E108") (pin "7") (pinfunction "Q2_7") (pintype "output"))
    )
    (net (code "466") (name "unconnected-(E108A-~{Q1}-Pad3)") (class "Default")
      (node (ref "E108") (pin "3") (pinfunction "~{Q1}_3") (pintype "output"))
    )
    (net (code "467") (name "unconnected-(E108A-~{Q2}-Pad6)") (class "Default")
      (node (ref "E108") (pin "6") (pinfunction "~{Q2}_6") (pintype "output"))
    )
    (net (code "468") (name "unconnected-(E109A-O0-Pad18)") (class "Default")
      (node (ref "E109") (pin "18") (pinfunction "O0_18") (pintype "tri_state"))
    )
    (net (code "469") (name "unconnected-(E109A-O1-Pad17)") (class "Default")
      (node (ref "E109") (pin "17") (pinfunction "O1_17") (pintype "tri_state"))
    )
    (net (code "470") (name "unconnected-(E110A-D1-Pad4)") (class "Default")
      (node (ref "E110") (pin "4") (pinfunction "D1_4") (pintype "input"))
    )
    (net (code "471") (name "unconnected-(E110A-D2-Pad5)") (class "Default")
      (node (ref "E110") (pin "5") (pinfunction "D2_5") (pintype "input"))
    )
    (net (code "472") (name "unconnected-(E110A-Q1-Pad2)") (class "Default")
      (node (ref "E110") (pin "2") (pinfunction "Q1_2") (pintype "output"))
    )
    (net (code "473") (name "unconnected-(E110A-Q2-Pad7)") (class "Default")
      (node (ref "E110") (pin "7") (pinfunction "Q2_7") (pintype "output"))
    )
    (net (code "474") (name "unconnected-(E110A-~{Q1}-Pad3)") (class "Default")
      (node (ref "E110") (pin "3") (pinfunction "~{Q1}_3") (pintype "output"))
    )
    (net (code "475") (name "unconnected-(E110A-~{Q2}-Pad6)") (class "Default")
      (node (ref "E110") (pin "6") (pinfunction "~{Q2}_6") (pintype "output"))
    )
    (net (code "476") (name "unconnected-(E111A-O2-Pad10)") (class "Default")
      (node (ref "E111") (pin "10") (pinfunction "O2_10") (pintype "tri_state"))
    )
    (net (code "477") (name "unconnected-(E111A-O3-Pad9)") (class "Default")
      (node (ref "E111") (pin "9") (pinfunction "O3_9") (pintype "tri_state"))
    )
    (net (code "478") (name "unconnected-(E112A-O3-Pad9)") (class "Default")
      (node (ref "E112") (pin "9") (pinfunction "O3_9") (pintype "tri_state"))
    )
    (net (code "479") (name "unconnected-(E113A-O2-Pad10)") (class "Default")
      (node (ref "E113") (pin "10") (pinfunction "O2_10") (pintype "tri_state"))
    )
    (net (code "480") (name "unconnected-(E113A-O3-Pad9)") (class "Default")
      (node (ref "E113") (pin "9") (pinfunction "O3_9") (pintype "tri_state"))
    )
    (net (code "481") (name "unconnected-(E114A-O1-Pad11)") (class "Default")
      (node (ref "E114") (pin "11") (pinfunction "O1_11") (pintype "tri_state"))
    )
    (net (code "482") (name "unconnected-(E114A-O3-Pad9)") (class "Default")
      (node (ref "E114") (pin "9") (pinfunction "O3_9") (pintype "tri_state"))
    )
    (net (code "483") (name "unconnected-(E115F-I-Pad13)") (class "Default")
      (node (ref "E115") (pin "13") (pinfunction "I_13") (pintype "input"))
    )
    (net (code "484") (name "unconnected-(E115F-O-Pad12)") (class "Default")
      (node (ref "E115") (pin "12") (pinfunction "O_12") (pintype "output"))
    )
    (net (code "485") (name "unconnected-(E116A-D1-Pad4)") (class "Default")
      (node (ref "E116") (pin "4") (pinfunction "D1_4") (pintype "input"))
    )
    (net (code "486") (name "unconnected-(E116A-D2-Pad5)") (class "Default")
      (node (ref "E116") (pin "5") (pinfunction "D2_5") (pintype "input"))
    )
    (net (code "487") (name "unconnected-(E116A-Q1-Pad2)") (class "Default")
      (node (ref "E116") (pin "2") (pinfunction "Q1_2") (pintype "output"))
    )
    (net (code "488") (name "unconnected-(E116A-Q2-Pad7)") (class "Default")
      (node (ref "E116") (pin "7") (pinfunction "Q2_7") (pintype "output"))
    )
    (net (code "489") (name "unconnected-(E116A-~{Q1}-Pad3)") (class "Default")
      (node (ref "E116") (pin "3") (pinfunction "~{Q1}_3") (pintype "output"))
    )
    (net (code "490") (name "unconnected-(E116A-~{Q2}-Pad6)") (class "Default")
      (node (ref "E116") (pin "6") (pinfunction "~{Q2}_6") (pintype "output"))
    )
    (net (code "491") (name "unconnected-(E116A-~{Q3}-Pad11)") (class "Default")
      (node (ref "E116") (pin "11") (pinfunction "~{Q3}_11") (pintype "output"))
    )
    (net (code "492") (name "unconnected-(E116A-~{Q4}-Pad14)") (class "Default")
      (node (ref "E116") (pin "14") (pinfunction "~{Q4}_14") (pintype "output"))
    )
    (net (code "493") (name "unconnected-(E117A-Q1-Pad2)") (class "Default")
      (node (ref "E117") (pin "2") (pinfunction "Q1_2") (pintype "output"))
    )
    (net (code "494") (name "unconnected-(E117A-Q2-Pad7)") (class "Default")
      (node (ref "E117") (pin "7") (pinfunction "Q2_7") (pintype "output"))
    )
    (net (code "495") (name "unconnected-(E117A-Q3-Pad10)") (class "Default")
      (node (ref "E117") (pin "10") (pinfunction "Q3_10") (pintype "output"))
    )
    (net (code "496") (name "unconnected-(E117A-Q4-Pad15)") (class "Default")
      (node (ref "E117") (pin "15") (pinfunction "Q4_15") (pintype "output"))
    )
    (net (code "497") (name "~{BREAK_IN_PROG}") (class "Default")
      (node (ref "E4") (pin "13") (pinfunction "O_13") (pintype "open_collector"))
      (node (ref "U$1") (pin "BE2") (pinfunction "1_BE2") (pintype "bidirectional"))
    )
    (net (code "498") (name "~{C0}") (class "Default")
      (node (ref "E19") (pin "13") (pinfunction "O_13") (pintype "open_collector"))
      (node (ref "U$1") (pin "CE1") (pinfunction "1_CE1") (pintype "bidirectional"))
    )
    (net (code "499") (name "~{C1}") (class "Default")
      (node (ref "E19") (pin "10") (pinfunction "O_10") (pintype "open_collector"))
      (node (ref "U$1") (pin "CH1") (pinfunction "1_CH1") (pintype "bidirectional"))
    )
    (net (code "500") (name "~{CPMA_DISABLE}") (class "Default")
      (node (ref "E19") (pin "4") (pinfunction "O_4") (pintype "open_collector"))
      (node (ref "E52") (pin "12") (pinfunction "I1_12") (pintype "input"))
      (node (ref "U$1") (pin "CU1") (pinfunction "1_CU1") (pintype "bidirectional"))
    )
    (net (code "501") (name "~{DATA00}") (class "Default")
      (node (ref "E12") (pin "4") (pinfunction "B3_4") (pintype "bidirectional"))
      (node (ref "U$1") (pin "AR1") (pinfunction "1_AR1") (pintype "bidirectional"))
    )
    (net (code "502") (name "~{DATA01}") (class "Default")
      (node (ref "E12") (pin "1") (pinfunction "B2_1") (pintype "bidirectional"))
      (node (ref "U$1") (pin "AS1") (pinfunction "1_AS1") (pintype "bidirectional"))
    )
    (net (code "503") (name "~{DATA02}") (class "Default")
      (node (ref "E12") (pin "12") (pinfunction "B1_12") (pintype "bidirectional"))
      (node (ref "U$1") (pin "AU1") (pinfunction "1_AU1") (pintype "bidirectional"))
    )
    (net (code "504") (name "~{DATA03}") (class "Default")
      (node (ref "E12") (pin "15") (pinfunction "B0_15") (pintype "bidirectional"))
      (node (ref "U$1") (pin "AV1") (pinfunction "1_AV1") (pintype "bidirectional"))
    )
    (net (code "505") (name "~{DATA04}") (class "Default")
      (node (ref "E13") (pin "4") (pinfunction "B3_4") (pintype "bidirectional"))
      (node (ref "U$1") (pin "BR1") (pinfunction "1_BR1") (pintype "bidirectional"))
    )
    (net (code "506") (name "~{DATA05}") (class "Default")
      (node (ref "E13") (pin "1") (pinfunction "B2_1") (pintype "bidirectional"))
      (node (ref "U$1") (pin "BS1") (pinfunction "1_BS1") (pintype "bidirectional"))
    )
    (net (code "507") (name "~{DATA06}") (class "Default")
      (node (ref "E13") (pin "12") (pinfunction "B1_12") (pintype "bidirectional"))
      (node (ref "U$1") (pin "BU1") (pinfunction "1_BU1") (pintype "bidirectional"))
    )
    (net (code "508") (name "~{DATA07}") (class "Default")
      (node (ref "E13") (pin "15") (pinfunction "B0_15") (pintype "bidirectional"))
      (node (ref "U$1") (pin "BV1") (pinfunction "1_BV1") (pintype "bidirectional"))
    )
    (net (code "509") (name "~{DATA08}") (class "Default")
      (node (ref "E45") (pin "4") (pinfunction "B3_4") (pintype "bidirectional"))
      (node (ref "U$1") (pin "DR1") (pinfunction "1_DR1") (pintype "bidirectional"))
    )
    (net (code "510") (name "~{DATA09}") (class "Default")
      (node (ref "E45") (pin "1") (pinfunction "B2_1") (pintype "bidirectional"))
      (node (ref "U$1") (pin "DS1") (pinfunction "1_DS1") (pintype "bidirectional"))
    )
    (net (code "511") (name "~{DATA10}") (class "Default")
      (node (ref "E45") (pin "12") (pinfunction "B1_12") (pintype "bidirectional"))
      (node (ref "U$1") (pin "DU1") (pinfunction "1_DU1") (pintype "bidirectional"))
    )
    (net (code "512") (name "~{DATA11}") (class "Default")
      (node (ref "E45") (pin "15") (pinfunction "B0_15") (pintype "bidirectional"))
      (node (ref "U$1") (pin "DV1") (pinfunction "1_DV1") (pintype "bidirectional"))
    )
    (net (code "513") (name "~{D}") (class "Default")
      (node (ref "E61") (pin "9") (pinfunction "I0_9") (pintype "input"))
      (node (ref "U$1") (pin "DK2") (pinfunction "1_DK2") (pintype "bidirectional"))
    )
    (net (code "514") (name "~{EMA0}") (class "Default")
      (node (ref "E1") (pin "6") (pinfunction "Q4_6") (pintype "tri_state"))
      (node (ref "E52") (pin "9") (pinfunction "I0_9") (pintype "input"))
      (node (ref "E73") (pin "6") (pinfunction "Q4_6") (pintype "tri_state"))
      (node (ref "U$1") (pin "AH2") (pinfunction "1_AH2") (pintype "bidirectional"))
    )
    (net (code "515") (name "~{EMA1}") (class "Default")
      (node (ref "E1") (pin "5") (pinfunction "Q3_5") (pintype "tri_state"))
      (node (ref "E52") (pin "6") (pinfunction "I0_6") (pintype "input"))
      (node (ref "E73") (pin "5") (pinfunction "Q3_5") (pintype "tri_state"))
      (node (ref "U$1") (pin "AE2") (pinfunction "1_AE2") (pintype "bidirectional"))
    )
    (net (code "516") (name "~{EMA2}") (class "Default")
      (node (ref "E1") (pin "4") (pinfunction "Q2_4") (pintype "tri_state"))
      (node (ref "E52") (pin "4") (pinfunction "I0_4") (pintype "input"))
      (node (ref "E73") (pin "4") (pinfunction "Q2_4") (pintype "tri_state"))
      (node (ref "U$1") (pin "AD2") (pinfunction "1_AD2") (pintype "bidirectional"))
    )
    (net (code "517") (name "~{FORCE_0}") (class "Default")
      (node (ref "E74") (pin "9") (pinfunction "O3_9") (pintype "tri_state"))
      (node (ref "E89") (pin "4") (pinfunction "7_4") (pintype "input"))
    )
    (net (code "518") (name "~{F_SET}") (class "Default")
      (node (ref "E75") (pin "7") (pinfunction "I1_7") (pintype "input"))
      (node (ref "U$1") (pin "DP2") (pinfunction "1_DP2") (pintype "bidirectional"))
    )
    (net (code "519") (name "~{F}") (class "Default")
      (node (ref "E61") (pin "12") (pinfunction "I1_12") (pintype "input"))
      (node (ref "U$1") (pin "DJ2") (pinfunction "1_DJ2") (pintype "bidirectional"))
    )
    (net (code "520") (name "~{IBS}") (class "Default")
      (node (ref "E101") (pin "15") (pinfunction "~{G}_15") (pintype "input"))
      (node (ref "E74") (pin "12") (pinfunction "O0_12") (pintype "tri_state"))
    )
    (net (code "521") (name "~{IND1}") (class "Default")
      (node (ref "E72") (pin "5") (pinfunction "I1_5") (pintype "input"))
      (node (ref "U$1") (pin "CU2") (pinfunction "1_CU2") (pintype "bidirectional"))
    )
    (net (code "522") (name "~{IND2}") (class "Default")
      (node (ref "E72") (pin "7") (pinfunction "I1_7") (pintype "input"))
      (node (ref "U$1") (pin "CV2") (pinfunction "1_CV2") (pintype "bidirectional"))
    )
    (net (code "523") (name "~{INT_IN_PROG}") (class "Default")
      (node (ref "E3") (pin "7") (pinfunction "I1_7") (pintype "input"))
      (node (ref "U$1") (pin "BP2") (pinfunction "1_BP2") (pintype "bidirectional"))
    )
    (net (code "524") (name "~{INT_RQST}") (class "Default")
      (node (ref "E42") (pin "1") (pinfunction "O_1") (pintype "open_collector"))
      (node (ref "E42") (pin "13") (pinfunction "O_13") (pintype "open_collector"))
      (node (ref "U$1") (pin "CP1") (pinfunction "1_CP1") (pintype "bidirectional"))
    )
    (net (code "525") (name "~{IR0}") (class "Default")
      (node (ref "E61") (pin "7") (pinfunction "I1_7") (pintype "input"))
      (node (ref "U$1") (pin "DD2") (pinfunction "1_DD2") (pintype "bidirectional"))
    )
    (net (code "526") (name "~{IR1}") (class "Default")
      (node (ref "E61") (pin "5") (pinfunction "I1_5") (pintype "input"))
      (node (ref "U$1") (pin "DE2") (pinfunction "1_DE2") (pintype "bidirectional"))
    )
    (net (code "527") (name "~{KEY_CONTROL}") (class "Default")
      (node (ref "E51") (pin "9") (pinfunction "I0_9") (pintype "input"))
      (node (ref "U$1") (pin "DU2") (pinfunction "1_DU2") (pintype "bidirectional"))
    )
    (net (code "528") (name "~{LA_EN}") (class "Default")
      (node (ref "E41") (pin "7") (pinfunction "I1_7") (pintype "input"))
      (node (ref "E51") (pin "10") (pinfunction "I1_10") (pintype "input"))
      (node (ref "U$1") (pin "BM2") (pinfunction "1_BM2") (pintype "bidirectional"))
    )
    (net (code "529") (name "~{LINK}") (class "Default")
      (node (ref "E3") (pin "12") (pinfunction "I1_12") (pintype "input"))
      (node (ref "U$1") (pin "AV2") (pinfunction "1_AV2") (pintype "bidirectional"))
    )
    (net (code "530") (name "~{MBCT4}") (class "Default")
      (node (ref "E16") (pin "6") (pinfunction "I3_6") (pintype "input"))
      (node (ref "E33") (pin "2") (pinfunction "I1_2") (pintype "input"))
      (node (ref "E6") (pin "8") (pinfunction "O_8") (pintype "output"))
      (node (ref "E9") (pin "5") (pinfunction "I3_5") (pintype "input"))
    )
    (net (code "531") (name "~{MD00}") (class "Default")
      (node (ref "E11") (pin "7") (pinfunction "I1_7") (pintype "input"))
      (node (ref "U$1") (pin "AK1") (pinfunction "1_AK1") (pintype "bidirectional"))
    )
    (net (code "532") (name "~{MD01}") (class "Default")
      (node (ref "E11") (pin "4") (pinfunction "I0_4") (pintype "input"))
      (node (ref "U$1") (pin "AL1") (pinfunction "1_AL1") (pintype "bidirectional"))
    )
    (net (code "533") (name "~{MD02}") (class "Default")
      (node (ref "E11") (pin "11") (pinfunction "I0_11") (pintype "input"))
      (node (ref "U$1") (pin "AM1") (pinfunction "1_AM1") (pintype "bidirectional"))
    )
    (net (code "534") (name "~{MD03}") (class "Default")
      (node (ref "E11") (pin "10") (pinfunction "I1_10") (pintype "input"))
      (node (ref "U$1") (pin "AP1") (pinfunction "1_AP1") (pintype "bidirectional"))
    )
    (net (code "535") (name "~{MD04}") (class "Default")
      (node (ref "E25") (pin "7") (pinfunction "I1_7") (pintype "input"))
      (node (ref "U$1") (pin "BK1") (pinfunction "1_BK1") (pintype "bidirectional"))
    )
    (net (code "536") (name "~{MD05}") (class "Default")
      (node (ref "E25") (pin "4") (pinfunction "I0_4") (pintype "input"))
      (node (ref "U$1") (pin "BL1") (pinfunction "1_BL1") (pintype "bidirectional"))
    )
    (net (code "537") (name "~{MD06}") (class "Default")
      (node (ref "E25") (pin "11") (pinfunction "I0_11") (pintype "input"))
      (node (ref "U$1") (pin "BM1") (pinfunction "1_BM1") (pintype "bidirectional"))
    )
    (net (code "538") (name "~{MD07}") (class "Default")
      (node (ref "E25") (pin "10") (pinfunction "I1_10") (pintype "input"))
      (node (ref "U$1") (pin "BP1") (pinfunction "1_BP1") (pintype "bidirectional"))
    )
    (net (code "539") (name "~{MD08}") (class "Default")
      (node (ref "E71") (pin "7") (pinfunction "I1_7") (pintype "input"))
      (node (ref "U$1") (pin "DK1") (pinfunction "1_DK1") (pintype "bidirectional"))
    )
    (net (code "540") (name "~{MD09}") (class "Default")
      (node (ref "E71") (pin "4") (pinfunction "I0_4") (pintype "input"))
      (node (ref "U$1") (pin "DL1") (pinfunction "1_DL1") (pintype "bidirectional"))
    )
    (net (code "541") (name "~{MD10}") (class "Default")
      (node (ref "E71") (pin "11") (pinfunction "I0_11") (pintype "input"))
      (node (ref "U$1") (pin "DM1") (pinfunction "1_DM1") (pintype "bidirectional"))
    )
    (net (code "542") (name "~{MD11}") (class "Default")
      (node (ref "E71") (pin "10") (pinfunction "I1_10") (pintype "input"))
      (node (ref "U$1") (pin "DP1") (pinfunction "1_DP1") (pintype "bidirectional"))
    )
    (net (code "543") (name "~{MSIRDIS}") (class "Default")
      (node (ref "E19") (pin "1") (pinfunction "O_1") (pintype "open_collector"))
      (node (ref "U$1") (pin "CV1") (pinfunction "1_CV1") (pintype "bidirectional"))
    )
    (net (code "544") (name "~{P1_ENRF}") (class "Default")
      (node (ref "E111") (pin "13") (pinfunction "~{G}_13") (pintype "input"))
      (node (ref "E112") (pin "13") (pinfunction "~{G}_13") (pintype "input"))
      (node (ref "E114") (pin "13") (pinfunction "~{G}_13") (pintype "input"))
      (node (ref "E27") (pin "5") (pinfunction "I2_5") (pintype "input"))
      (node (ref "E33") (pin "11") (pinfunction "O_11") (pintype "output"))
    )
    (net (code "545") (name "~{P2_BCPMAD}") (class "Default")
      (node (ref "E52") (pin "13") (pinfunction "O_13") (pintype "output"))
      (node (ref "E63") (pin "12") (pinfunction "D_12") (pintype "input"))
      (node (ref "E74") (pin "3") (pinfunction "A4_3") (pintype "input"))
    )
    (net (code "546") (name "~{P2_DFA}") (class "Default")
      (node (ref "E101") (pin "6") (pinfunction "A3_6") (pintype "input"))
      (node (ref "E102") (pin "7") (pinfunction "Q2_7") (pintype "output"))
      (node (ref "E103") (pin "14") (pinfunction "D6_14") (pintype "input"))
      (node (ref "E104") (pin "6") (pinfunction "1A3_6") (pintype "input"))
    )
    (net (code "547") (name "~{P2_DFB}") (class "Default")
      (node (ref "E101") (pin "4") (pinfunction "A2_4") (pintype "input"))
      (node (ref "E102") (pin "10") (pinfunction "Q3_10") (pintype "output"))
      (node (ref "E103") (pin "13") (pinfunction "D5_13") (pintype "input"))
      (node (ref "E104") (pin "4") (pinfunction "1A2_4") (pintype "input"))
    )
    (net (code "548") (name "~{P2_DFC}") (class "Default")
      (node (ref "E101") (pin "2") (pinfunction "A1_2") (pintype "input"))
      (node (ref "E102") (pin "15") (pinfunction "Q4_15") (pintype "output"))
      (node (ref "E103") (pin "11") (pinfunction "D4_11") (pintype "input"))
      (node (ref "E104") (pin "2") (pinfunction "1A1_2") (pintype "input"))
    )
    (net (code "549") (name "~{P2_ELAR}") (class "Default")
      (node (ref "E1") (pin "1") (pinfunction "M_1") (pintype "input"))
      (node (ref "E1") (pin "2") (pinfunction "N_2") (pintype "input"))
      (node (ref "E121") (pin "1") (pinfunction "M_1") (pintype "input"))
      (node (ref "E121") (pin "2") (pinfunction "N_2") (pintype "input"))
      (node (ref "E122") (pin "1") (pinfunction "M_1") (pintype "input"))
      (node (ref "E122") (pin "2") (pinfunction "N_2") (pintype "input"))
      (node (ref "E63") (pin "5") (pinfunction "Q_5") (pintype "output"))
    )
    (net (code "550") (name "~{P2_EMAEN}") (class "Default")
      (node (ref "E63") (pin "8") (pinfunction "~{Q}_8") (pintype "output"))
      (node (ref "E73") (pin "1") (pinfunction "M_1") (pintype "input"))
      (node (ref "E73") (pin "2") (pinfunction "N_2") (pintype "input"))
    )
    (net (code "551") (name "~{P2_ENBS}") (class "Default")
      (node (ref "E118") (pin "2") (pinfunction "N_2") (pintype "input"))
      (node (ref "E119") (pin "2") (pinfunction "N_2") (pintype "input"))
      (node (ref "E63") (pin "6") (pinfunction "~{Q}_6") (pintype "output"))
    )
    (net (code "552") (name "~{P2_IFA}") (class "Default")
      (node (ref "E103") (pin "6") (pinfunction "D3_6") (pintype "input"))
      (node (ref "E83") (pin "2") (pinfunction "A1_2") (pintype "input"))
      (node (ref "E84") (pin "6") (pinfunction "1A3_6") (pintype "input"))
      (node (ref "E93") (pin "7") (pinfunction "Q2_7") (pintype "output"))
    )
    (net (code "553") (name "~{P2_IFB}") (class "Default")
      (node (ref "E103") (pin "4") (pinfunction "D2_4") (pintype "input"))
      (node (ref "E83") (pin "4") (pinfunction "A2_4") (pintype "input"))
      (node (ref "E84") (pin "4") (pinfunction "1A2_4") (pintype "input"))
      (node (ref "E93") (pin "10") (pinfunction "Q3_10") (pintype "output"))
    )
    (net (code "554") (name "~{P2_IFC}") (class "Default")
      (node (ref "E103") (pin "3") (pinfunction "D1_3") (pintype "input"))
      (node (ref "E83") (pin "6") (pinfunction "A3_6") (pintype "input"))
      (node (ref "E84") (pin "2") (pinfunction "1A1_2") (pintype "input"))
      (node (ref "E93") (pin "15") (pinfunction "Q4_15") (pintype "output"))
    )
    (net (code "555") (name "~{P2_INT}") (class "Default")
      (node (ref "E115") (pin "4") (pinfunction "O_4") (pintype "output"))
      (node (ref "E92") (pin "2") (pinfunction "I1_2") (pintype "input"))
    )
    (net (code "556") (name "~{P2_RSB}") (class "Default")
      (node (ref "E100") (pin "1") (pinfunction "1G_1") (pintype "input"))
      (node (ref "E38") (pin "11") (pinfunction "O_11") (pintype "output"))
    )
    (net (code "557") (name "~{P2_RST}") (class "Default")
      (node (ref "E35") (pin "1") (pinfunction "CLR_1") (pintype "input"))
      (node (ref "E46") (pin "1") (pinfunction "CLR_1") (pintype "input"))
      (node (ref "E63") (pin "13") (pinfunction "CLR_13") (pintype "input"))
      (node (ref "E67") (pin "6") (pinfunction "O_6") (pintype "output"))
      (node (ref "E85") (pin "1") (pinfunction "CLR_1") (pintype "input"))
      (node (ref "E88") (pin "1") (pinfunction "CLR_1") (pintype "input"))
    )
    (net (code "558") (name "~{P3_BINIT}") (class "Default")
      (node (ref "E15") (pin "1") (pinfunction "CLR_1") (pintype "input"))
      (node (ref "E17") (pin "1") (pinfunction "CLR_1") (pintype "input"))
      (node (ref "E22") (pin "4") (pinfunction "O_4") (pintype "output"))
      (node (ref "E27") (pin "10") (pinfunction "I1_10") (pintype "input"))
      (node (ref "E27") (pin "11") (pinfunction "I2_11") (pintype "input"))
      (node (ref "E32") (pin "10") (pinfunction "PRE_10") (pintype "input"))
    )
    (net (code "559") (name "~{P3_BM0}") (class "Default")
      (node (ref "E29") (pin "2") (pinfunction "I0_2") (pintype "input"))
      (node (ref "E5") (pin "10") (pinfunction "O_10") (pintype "output"))
    )
    (net (code "560") (name "~{P3_BM2}") (class "Default")
      (node (ref "E30") (pin "3") (pinfunction "I2_3") (pintype "input"))
      (node (ref "E5") (pin "12") (pinfunction "O_12") (pintype "output"))
    )
    (net (code "561") (name "~{P3_BM3}") (class "Default")
      (node (ref "E49") (pin "5") (pinfunction "I2_5") (pintype "input"))
      (node (ref "E7") (pin "10") (pinfunction "O_10") (pintype "output"))
    )
    (net (code "562") (name "~{P3_BM4}") (class "Default")
      (node (ref "E36") (pin "9") (pinfunction "I0_9") (pintype "input"))
      (node (ref "E43") (pin "2") (pinfunction "I1_2") (pintype "input"))
      (node (ref "E7") (pin "12") (pinfunction "O_12") (pintype "output"))
    )
    (net (code "563") (name "~{P3_BM9}") (class "Default")
      (node (ref "E36") (pin "2") (pinfunction "I1_2") (pintype "input"))
      (node (ref "E44") (pin "10") (pinfunction "O_10") (pintype "output"))
    )
    (net (code "564") (name "~{P3_BM11}") (class "Default")
      (node (ref "E36") (pin "4") (pinfunction "I2_4") (pintype "input"))
      (node (ref "E43") (pin "1") (pinfunction "I0_1") (pintype "input"))
      (node (ref "E44") (pin "12") (pinfunction "O_12") (pintype "output"))
    )
    (net (code "565") (name "~{P3_BTP2}") (class "Default")
      (node (ref "E22") (pin "2") (pinfunction "O_2") (pintype "output"))
      (node (ref "E65") (pin "13") (pinfunction "CLR_13") (pintype "input"))
    )
    (net (code "566") (name "~{P3_BTP3}") (class "Default")
      (node (ref "E26") (pin "13") (pinfunction "1C,2C_13") (pintype "input"))
      (node (ref "E29") (pin "11") (pinfunction "I0_11") (pintype "input"))
      (node (ref "E38") (pin "1") (pinfunction "I0_1") (pintype "input"))
      (node (ref "E38") (pin "2") (pinfunction "I1_2") (pintype "input"))
      (node (ref "E47") (pin "11") (pinfunction "I0_11") (pintype "input"))
      (node (ref "E48") (pin "6") (pinfunction "I1_6") (pintype "input"))
      (node (ref "E51") (pin "2") (pinfunction "O_2") (pintype "output"))
    )
    (net (code "567") (name "~{P3_C17EN}") (class "Default")
      (node (ref "E14") (pin "13") (pinfunction "O4_13") (pintype "tri_state"))
      (node (ref "E34") (pin "12") (pinfunction "D_12") (pintype "input"))
    )
    (net (code "568") (name "~{P3_CFROM}") (class "Default")
      (node (ref "E14") (pin "12") (pinfunction "O5_12") (pintype "tri_state"))
      (node (ref "E28") (pin "13") (pinfunction "~{G1}_13") (pintype "input"))
    )
    (net (code "569") (name "~{P3_DECEN}") (class "Default")
      (node (ref "E14") (pin "11") (pinfunction "O6_11") (pintype "tri_state"))
      (node (ref "E31") (pin "18") (pinfunction "G1_18") (pintype "input"))
      (node (ref "E47") (pin "2") (pinfunction "I0_2") (pintype "input"))
    )
    (net (code "570") (name "~{P3_E2CFROM}") (class "Default")
      (node (ref "E26") (pin "15") (pinfunction "2Q_15") (pintype "output"))
      (node (ref "E28") (pin "14") (pinfunction "~{G2}_14") (pintype "input"))
    )
    (net (code "571") (name "~{P3_HOS}") (class "Default")
      (node (ref "E14") (pin "15") (pinfunction "O3_15") (pintype "tri_state"))
      (node (ref "E24") (pin "2") (pinfunction "I1_2") (pintype "input"))
    )
    (net (code "572") (name "~{P4_BLBM}") (class "Default")
      (node (ref "E26") (pin "8") (pinfunction "~{2Q}_8") (pintype "output"))
      (node (ref "E82") (pin "3") (pinfunction "WE_3") (pintype "input"))
    )
    (net (code "573") (name "~{P4_CDF}") (class "Default")
      (node (ref "E28") (pin "9") (pinfunction "O3_9") (pintype "tri_state"))
      (node (ref "E70") (pin "10") (pinfunction "I1_10") (pintype "input"))
      (node (ref "E80") (pin "12") (pinfunction "A2_12") (pintype "input"))
      (node (ref "E89") (pin "1") (pinfunction "4_1") (pintype "input"))
      (node (ref "R17") (pin "1") (pinfunction "1_1") (pintype "passive"))
    )
    (net (code "574") (name "~{P4_CIF}") (class "Default")
      (node (ref "E28") (pin "10") (pinfunction "O2_10") (pintype "tri_state"))
      (node (ref "E70") (pin "9") (pinfunction "I0_9") (pintype "input"))
      (node (ref "E80") (pin "11") (pinfunction "A1_11") (pintype "input"))
      (node (ref "E89") (pin "2") (pinfunction "5_2") (pintype "input"))
      (node (ref "R16") (pin "1") (pinfunction "1_1") (pintype "passive"))
    )
    (net (code "575") (name "~{P4_CINT}") (class "Default")
      (node (ref "E31") (pin "9") (pinfunction "8_9") (pintype "output"))
      (node (ref "E33") (pin "5") (pinfunction "I1_5") (pintype "input"))
    )
    (net (code "576") (name "~{P4_CUF}") (class "Default")
      (node (ref "E22") (pin "11") (pinfunction "I_11") (pintype "input"))
      (node (ref "E31") (pin "16") (pinfunction "14_16") (pintype "output"))
    )
    (net (code "577") (name "~{P4_CUMB}") (class "Default")
      (node (ref "E33") (pin "8") (pinfunction "O_8") (pintype "output"))
      (node (ref "E59") (pin "10") (pinfunction "PRE_10") (pintype "input"))
      (node (ref "E60") (pin "1") (pinfunction "CLR_1") (pintype "input"))
    )
    (net (code "578") (name "~{P4_DFEN}") (class "Default")
      (node (ref "E76") (pin "9") (pinfunction "Q_9") (pintype "output"))
      (node (ref "E92") (pin "13") (pinfunction "I2_13") (pintype "input"))
    )
    (net (code "579") (name "~{P4_FATAL}") (class "Default")
      (node (ref "E32") (pin "1") (pinfunction "CLR_1") (pintype "input"))
      (node (ref "E38") (pin "6") (pinfunction "O_6") (pintype "output"))
      (node (ref "E4") (pin "6") (pinfunction "I1_6") (pintype "input"))
    )
    (net (code "580") (name "~{P4_GTF}") (class "Default")
      (node (ref "E18") (pin "12") (pinfunction "I0_12") (pintype "input"))
      (node (ref "E18") (pin "13") (pinfunction "I1_13") (pintype "input"))
      (node (ref "E38") (pin "12") (pinfunction "I0_12") (pintype "input"))
      (node (ref "E43") (pin "6") (pinfunction "O_6") (pintype "output"))
      (node (ref "E56") (pin "3") (pinfunction "I0_3") (pintype "input"))
      (node (ref "E6") (pin "12") (pinfunction "I0_12") (pintype "input"))
    )
    (net (code "581") (name "~{P4_GTS}") (class "Default")
      (node (ref "E31") (pin "2") (pinfunction "1_2") (pintype "output"))
      (node (ref "E56") (pin "5") (pinfunction "I2_5") (pintype "input"))
      (node (ref "E6") (pin "13") (pinfunction "I1_13") (pintype "input"))
    )
    (net (code "582") (name "~{P4_INIT_EN}") (class "Default")
      (node (ref "E74") (pin "2") (pinfunction "A5_2") (pintype "input"))
      (node (ref "E76") (pin "5") (pinfunction "Q_5") (pintype "output"))
    )
    (net (code "583") (name "~{P4_INT_INH}") (class "Default")
      (node (ref "E48") (pin "3") (pinfunction "I1_3") (pintype "input"))
      (node (ref "E77") (pin "6") (pinfunction "~{Q}_6") (pintype "output"))
    )
    (net (code "584") (name "~{P4_INT_IN_PROG}") (class "Default")
      (node (ref "E4") (pin "4") (pinfunction "O_4") (pintype "open_collector"))
      (node (ref "E74") (pin "15") (pinfunction "A7_15") (pintype "input"))
    )
    (net (code "585") (name "~{P4_LBM}") (class "Default")
      (node (ref "E29") (pin "9") (pinfunction "I1_9") (pintype "input"))
      (node (ref "E34") (pin "1") (pinfunction "O0_1") (pintype "output"))
      (node (ref "E81") (pin "23") (pinfunction "I12_23") (pintype "input"))
    )
    (net (code "586") (name "~{P4_LET_IO}") (class "Default")
      (node (ref "E24") (pin "11") (pinfunction "I2_11") (pintype "input"))
      (node (ref "E28") (pin "12") (pinfunction "O0_12") (pintype "tri_state"))
      (node (ref "E30") (pin "5") (pinfunction "I4_5") (pintype "input"))
      (node (ref "E30") (pin "6") (pinfunction "I5_6") (pintype "input"))
      (node (ref "E64") (pin "5") (pinfunction "I0_5") (pintype "input"))
      (node (ref "E95") (pin "1") (pinfunction "1G_1") (pintype "input"))
      (node (ref "E95") (pin "15") (pinfunction "2G_15") (pintype "input"))
      (node (ref "R14") (pin "1") (pinfunction "1_1") (pintype "passive"))
    )
    (net (code "587") (name "~{P4_LRR}") (class "Default")
      (node (ref "E31") (pin "5") (pinfunction "4_5") (pintype "output"))
      (node (ref "E47") (pin "12") (pinfunction "I1_12") (pintype "input"))
    )
    (net (code "588") (name "~{P4_LUSR}") (class "Default")
      (node (ref "E29") (pin "12") (pinfunction "I1_12") (pintype "input"))
      (node (ref "E31") (pin "7") (pinfunction "6_7") (pintype "output"))
    )
    (net (code "589") (name "~{P4_LXM}") (class "Default")
      (node (ref "E24") (pin "9") (pinfunction "I0_9") (pintype "input"))
      (node (ref "E36") (pin "6") (pinfunction "O_6") (pintype "output"))
      (node (ref "E48") (pin "5") (pinfunction "I0_5") (pintype "input"))
    )
    (net (code "590") (name "~{P4_MBC}") (class "Default")
      (node (ref "E22") (pin "5") (pinfunction "I_5") (pintype "input"))
      (node (ref "E34") (pin "5") (pinfunction "O4_5") (pintype "output"))
    )
    (net (code "591") (name "~{P4_PCLR}") (class "Default")
      (node (ref "E49") (pin "2") (pinfunction "I1_2") (pintype "input"))
      (node (ref "E63") (pin "4") (pinfunction "PRE_4") (pintype "input"))
      (node (ref "E65") (pin "4") (pinfunction "PRE_4") (pintype "input"))
      (node (ref "E67") (pin "5") (pinfunction "I1_5") (pintype "input"))
      (node (ref "E76") (pin "3") (pinfunction "CLK_3") (pintype "input"))
      (node (ref "PAD2") (pin "1") (pinfunction "P_1") (pintype "passive"))
    )
    (net (code "592") (name "~{P4_PLXA}") (class "Default")
      (node (ref "E49") (pin "13") (pinfunction "I2_13") (pintype "input"))
      (node (ref "E57") (pin "6") (pinfunction "O_6") (pintype "output"))
      (node (ref "E58") (pin "1") (pinfunction "I_1") (pintype "input"))
      (node (ref "E63") (pin "1") (pinfunction "CLR_1") (pintype "input"))
      (node (ref "E67") (pin "4") (pinfunction "I0_4") (pintype "input"))
    )
    (net (code "593") (name "~{P4_RACA}") (class "Default")
      (node (ref "E16") (pin "7") (pinfunction "I2_7") (pintype "input"))
      (node (ref "E23") (pin "1") (pinfunction "~{A}/B_1") (pintype "input"))
      (node (ref "E33") (pin "1") (pinfunction "I0_1") (pintype "input"))
      (node (ref "E34") (pin "6") (pinfunction "O5_6") (pintype "output"))
      (node (ref "E9") (pin "1") (pinfunction "I0_1") (pintype "input"))
    )
    (net (code "594") (name "~{P4_RACB}") (class "Default")
      (node (ref "E16") (pin "8") (pinfunction "I1_8") (pintype "input"))
      (node (ref "E34") (pin "7") (pinfunction "O6_7") (pintype "output"))
      (node (ref "E9") (pin "2") (pinfunction "I1_2") (pintype "input"))
    )
    (net (code "595") (name "~{P4_RACC}") (class "Default")
      (node (ref "E16") (pin "9") (pinfunction "I0_9") (pintype "input"))
      (node (ref "E34") (pin "9") (pinfunction "O7_9") (pintype "output"))
      (node (ref "E9") (pin "4") (pinfunction "I2_4") (pintype "input"))
    )
    (net (code "596") (name "~{P4_RBM}") (class "Default")
      (node (ref "E100") (pin "15") (pinfunction "2G_15") (pintype "input"))
      (node (ref "E34") (pin "2") (pinfunction "O1_2") (pintype "output"))
      (node (ref "E81") (pin "22") (pinfunction "I13_22") (pintype "input"))
    )
    (net (code "597") (name "~{P4_RDF}") (class "Default")
      (node (ref "E111") (pin "15") (pinfunction "A7_15") (pintype "input"))
      (node (ref "E112") (pin "15") (pinfunction "A7_15") (pintype "input"))
      (node (ref "E114") (pin "15") (pinfunction "A7_15") (pintype "input"))
      (node (ref "E31") (pin "10") (pinfunction "9_10") (pintype "output"))
      (node (ref "E33") (pin "13") (pinfunction "I1_13") (pintype "input"))
    )
    (net (code "598") (name "~{P4_RIB}") (class "Default")
      (node (ref "E31") (pin "13") (pinfunction "11_13") (pintype "output"))
      (node (ref "E56") (pin "4") (pinfunction "I1_4") (pintype "input"))
    )
    (net (code "599") (name "~{P4_RIF}") (class "Default")
      (node (ref "E31") (pin "11") (pinfunction "10_11") (pintype "output"))
      (node (ref "E33") (pin "12") (pinfunction "I0_12") (pintype "input"))
    )
    (net (code "600") (name "~{P4_RLB}") (class "Default")
      (node (ref "E34") (pin "3") (pinfunction "O2_3") (pintype "output"))
      (node (ref "E90") (pin "1") (pinfunction "M_1") (pintype "input"))
      (node (ref "E90") (pin "2") (pinfunction "N_2") (pintype "input"))
    )
    (net (code "601") (name "~{P4_RMF}") (class "Default")
      (node (ref "E107") (pin "1") (pinfunction "1G_1") (pintype "input"))
      (node (ref "E107") (pin "15") (pinfunction "2G_15") (pintype "input"))
      (node (ref "E31") (pin "14") (pinfunction "12_14") (pintype "output"))
      (node (ref "E39") (pin "1") (pinfunction "I_1") (pintype "input"))
      (node (ref "E50") (pin "9") (pinfunction "I0_9") (pintype "input"))
      (node (ref "E70") (pin "13") (pinfunction "I1_13") (pintype "input"))
      (node (ref "E89") (pin "11") (pinfunction "1_11") (pintype "input"))
    )
    (net (code "602") (name "~{P4_RMR}") (class "Default")
      (node (ref "E34") (pin "4") (pinfunction "O3_4") (pintype "output"))
      (node (ref "E62") (pin "1") (pinfunction "M_1") (pintype "input"))
      (node (ref "E62") (pin "2") (pinfunction "N_2") (pintype "input"))
      (node (ref "E98") (pin "1") (pinfunction "M_1") (pintype "input"))
      (node (ref "E98") (pin "2") (pinfunction "N_2") (pintype "input"))
      (node (ref "E99") (pin "1") (pinfunction "M_1") (pintype "input"))
      (node (ref "E99") (pin "2") (pinfunction "N_2") (pintype "input"))
    )
    (net (code "603") (name "~{P4_RRR}") (class "Default")
      (node (ref "E31") (pin "6") (pinfunction "5_6") (pintype "output"))
      (node (ref "E86") (pin "1") (pinfunction "1G_1") (pintype "input"))
      (node (ref "E86") (pin "15") (pinfunction "2G_15") (pintype "input"))
    )
    (net (code "604") (name "~{P4_RTF}") (class "Default")
      (node (ref "E36") (pin "8") (pinfunction "O_8") (pintype "output"))
      (node (ref "E38") (pin "9") (pinfunction "I0_9") (pintype "input"))
      (node (ref "E80") (pin "14") (pinfunction "A4_14") (pintype "input"))
    )
    (net (code "605") (name "~{P4_RTS}") (class "Default")
      (node (ref "E31") (pin "3") (pinfunction "2_3") (pintype "output"))
      (node (ref "E38") (pin "10") (pinfunction "I1_10") (pintype "input"))
      (node (ref "E70") (pin "12") (pinfunction "I0_12") (pintype "input"))
      (node (ref "E89") (pin "12") (pinfunction "2_12") (pintype "input"))
    )
    (net (code "606") (name "~{P4_RUSR}") (class "Default")
      (node (ref "E106") (pin "1") (pinfunction "1G_1") (pintype "input"))
      (node (ref "E106") (pin "15") (pinfunction "2G_15") (pintype "input"))
      (node (ref "E31") (pin "8") (pinfunction "7_8") (pintype "output"))
    )
    (net (code "607") (name "~{P4_RXM}") (class "Default")
      (node (ref "E31") (pin "4") (pinfunction "3_4") (pintype "output"))
      (node (ref "E37") (pin "1") (pinfunction "1G_1") (pintype "input"))
      (node (ref "E37") (pin "15") (pinfunction "2G_15") (pintype "input"))
      (node (ref "E55") (pin "15") (pinfunction "2G_15") (pintype "input"))
    )
    (net (code "608") (name "~{P4_SINT}") (class "Default")
      (node (ref "E22") (pin "13") (pinfunction "I_13") (pintype "input"))
      (node (ref "E31") (pin "15") (pinfunction "13_15") (pintype "output"))
    )
    (net (code "609") (name "~{P4_SUF}") (class "Default")
      (node (ref "E31") (pin "17") (pinfunction "15_17") (pintype "output"))
      (node (ref "E39") (pin "3") (pinfunction "I_3") (pintype "input"))
      (node (ref "E67") (pin "2") (pinfunction "I1_2") (pintype "input"))
    )
    (net (code "610") (name "~{P4_USINT}") (class "Default")
      (node (ref "E24") (pin "4") (pinfunction "I1_4") (pintype "input"))
      (node (ref "E32") (pin "9") (pinfunction "Q_9") (pintype "output"))
    )
    (net (code "611") (name "~{P5_BMEN}") (class "Default")
      (node (ref "E54") (pin "2") (pinfunction "I1_2") (pintype "input"))
      (node (ref "E74") (pin "10") (pinfunction "O2_10") (pintype "tri_state"))
      (node (ref "E82") (pin "2") (pinfunction "CS_2") (pintype "input"))
      (node (ref "E90") (pin "10") (pinfunction "G2_10") (pintype "input"))
      (node (ref "E90") (pin "9") (pinfunction "G1_9") (pintype "input"))
    )
    (net (code "612") (name "~{P5_DBS}") (class "Default")
      (node (ref "E54") (pin "1") (pinfunction "I0_1") (pintype "input"))
      (node (ref "E74") (pin "11") (pinfunction "O1_11") (pintype "tri_state"))
      (node (ref "E91") (pin "15") (pinfunction "2G_15") (pintype "input"))
    )
    (net (code "613") (name "~{P5_IBS0}") (class "Default")
      (node (ref "E118") (pin "11") (pinfunction "D4_11") (pintype "input"))
      (node (ref "E119") (pin "11") (pinfunction "D4_11") (pintype "input"))
      (node (ref "E120") (pin "7") (pinfunction "Y3_7") (pintype "output"))
    )
    (net (code "614") (name "~{P5_IBS1}") (class "Default")
      (node (ref "E118") (pin "12") (pinfunction "D3_12") (pintype "input"))
      (node (ref "E119") (pin "12") (pinfunction "D3_12") (pintype "input"))
      (node (ref "E120") (pin "6") (pinfunction "Y2_6") (pintype "output"))
    )
    (net (code "615") (name "~{P5_IBS2}") (class "Default")
      (node (ref "E118") (pin "13") (pinfunction "D2_13") (pintype "input"))
      (node (ref "E119") (pin "13") (pinfunction "D2_13") (pintype "input"))
      (node (ref "E120") (pin "5") (pinfunction "Y1_5") (pintype "output"))
    )
    (net (code "616") (name "~{P5_IBS3}") (class "Default")
      (node (ref "E118") (pin "14") (pinfunction "D1_14") (pintype "input"))
      (node (ref "E119") (pin "14") (pinfunction "D1_14") (pintype "input"))
      (node (ref "E120") (pin "4") (pinfunction "Y0_4") (pintype "output"))
    )
    (net (code "617") (name "~{P6_BS0}") (class "Default")
      (node (ref "E118") (pin "6") (pinfunction "Q4_6") (pintype "tri_state"))
      (node (ref "E121") (pin "6") (pinfunction "Q4_6") (pintype "tri_state"))
      (node (ref "E55") (pin "7") (pinfunction "1Y3_7") (pintype "tri_state"))
      (node (ref "E55") (pin "9") (pinfunction "1Y4_9") (pintype "tri_state"))
      (node (ref "E98") (pin "11") (pinfunction "D4_11") (pintype "input"))
      (node (ref "U$1") (pin "EB2") (pinfunction "1_EB2") (pintype "bidirectional"))
    )
    (net (code "618") (name "~{P6_BS1}") (class "Default")
      (node (ref "E118") (pin "5") (pinfunction "Q3_5") (pintype "tri_state"))
      (node (ref "E121") (pin "5") (pinfunction "Q3_5") (pintype "tri_state"))
      (node (ref "E98") (pin "12") (pinfunction "D3_12") (pintype "input"))
      (node (ref "U$1") (pin "ED2") (pinfunction "1_ED2") (pintype "bidirectional"))
    )
    (net (code "619") (name "~{P6_BS2}") (class "Default")
      (node (ref "E118") (pin "4") (pinfunction "Q2_4") (pintype "tri_state"))
      (node (ref "E121") (pin "4") (pinfunction "Q2_4") (pintype "tri_state"))
      (node (ref "E98") (pin "13") (pinfunction "D2_13") (pintype "input"))
      (node (ref "U$1") (pin "EL2") (pinfunction "1_EL2") (pintype "bidirectional"))
    )
    (net (code "620") (name "~{P6_BS3}") (class "Default")
      (node (ref "E118") (pin "3") (pinfunction "Q1_3") (pintype "tri_state"))
      (node (ref "E121") (pin "3") (pinfunction "Q1_3") (pintype "tri_state"))
      (node (ref "E98") (pin "14") (pinfunction "D1_14") (pintype "input"))
      (node (ref "U$1") (pin "EP2") (pinfunction "1_EP2") (pintype "bidirectional"))
    )
    (net (code "621") (name "~{P6_CKMR}") (class "Default")
      (node (ref "E54") (pin "8") (pinfunction "O_8") (pintype "output"))
      (node (ref "E62") (pin "7") (pinfunction "CLK_7") (pintype "input"))
      (node (ref "E98") (pin "7") (pinfunction "CLK_7") (pintype "input"))
      (node (ref "E99") (pin "7") (pinfunction "CLK_7") (pintype "input"))
    )
    (net (code "622") (name "~{P6_DIOI}") (class "Default")
      (node (ref "E27") (pin "3") (pinfunction "I0_3") (pintype "input"))
      (node (ref "E27") (pin "4") (pinfunction "I1_4") (pintype "input"))
      (node (ref "E30") (pin "4") (pinfunction "I3_4") (pintype "input"))
      (node (ref "E37") (pin "6") (pinfunction "1A3_6") (pintype "input"))
      (node (ref "E46") (pin "14") (pinfunction "~{Q4}_14") (pintype "output"))
    )
    (net (code "623") (name "~{P6_DISF}") (class "Default")
      (node (ref "E101") (pin "1") (pinfunction "~{G}_1") (pintype "input"))
      (node (ref "E83") (pin "1") (pinfunction "~{G}_1") (pintype "input"))
      (node (ref "E94") (pin "3") (pinfunction "O_3") (pintype "output"))
    )
    (net (code "624") (name "~{P6_DISPB}") (class "Default")
      (node (ref "E91") (pin "1") (pinfunction "1G_1") (pintype "input"))
      (node (ref "E92") (pin "6") (pinfunction "O_6") (pintype "output"))
    )
    (net (code "625") (name "~{P6_EBM}") (class "Default")
      (node (ref "E37") (pin "4") (pinfunction "1A2_4") (pintype "input"))
      (node (ref "E46") (pin "11") (pinfunction "~{Q3}_11") (pintype "output"))
    )
    (net (code "626") (name "~{P6_EEM}") (class "Default")
      (node (ref "E35") (pin "14") (pinfunction "~{Q4}_14") (pintype "output"))
      (node (ref "E55") (pin "12") (pinfunction "2A1_12") (pintype "input"))
    )
    (net (code "627") (name "~{P6_EN5}") (class "Default")
      (node (ref "E35") (pin "11") (pinfunction "~{Q3}_11") (pintype "output"))
      (node (ref "E37") (pin "14") (pinfunction "2A2_14") (pintype "input"))
    )
    (net (code "628") (name "~{P6_EN9}") (class "Default")
      (node (ref "E35") (pin "6") (pinfunction "~{Q2}_6") (pintype "output"))
      (node (ref "E37") (pin "12") (pinfunction "2A1_12") (pintype "input"))
    )
    (net (code "629") (name "~{P6_MAINT}") (class "Default")
      (node (ref "E37") (pin "2") (pinfunction "1A1_2") (pintype "input"))
      (node (ref "E46") (pin "6") (pinfunction "~{Q2}_6") (pintype "output"))
      (node (ref "E48") (pin "2") (pinfunction "I0_2") (pintype "input"))
    )
    (net (code "630") (name "~{P6_PRUP}") (class "Default")
      (node (ref "E118") (pin "1") (pinfunction "M_1") (pintype "input"))
      (node (ref "E119") (pin "1") (pinfunction "M_1") (pintype "input"))
      (node (ref "E65") (pin "5") (pinfunction "Q_5") (pintype "output"))
    )
    (net (code "631") (name "~{P6_RVFEN}") (class "Default")
      (node (ref "E35") (pin "3") (pinfunction "~{Q1}_3") (pintype "output"))
      (node (ref "E37") (pin "10") (pinfunction "1A4_10") (pintype "input"))
    )
    (net (code "632") (name "~{P6_USM}") (class "Default")
      (node (ref "E59") (pin "2") (pinfunction "D_2") (pintype "input"))
      (node (ref "E59") (pin "9") (pinfunction "Q_9") (pintype "output"))
      (node (ref "E83") (pin "14") (pinfunction "A2_14") (pintype "input"))
    )
    (net (code "633") (name "~{PAUSE}") (class "Default")
      (node (ref "D1") (pin "C") (pinfunction "C_C") (pintype "passive"))
      (node (ref "E41") (pin "4") (pinfunction "I0_4") (pintype "input"))
      (node (ref "Q1") (pin "3") (pinfunction "C_3") (pintype "passive"))
      (node (ref "U$1") (pin "CD1") (pinfunction "1_CD1") (pintype "bidirectional"))
    )
    (net (code "634") (name "~{POWER_OK}") (class "Default")
      (node (ref "E41") (pin "9") (pinfunction "I0_9") (pintype "input"))
      (node (ref "U$1") (pin "BV2") (pinfunction "1_BV2") (pintype "bidirectional"))
    )
    (net (code "635") (name "~{RBS0}") (class "Default")
      (node (ref "E119") (pin "6") (pinfunction "Q4_6") (pintype "tri_state"))
      (node (ref "E122") (pin "6") (pinfunction "Q4_6") (pintype "tri_state"))
      (node (ref "E55") (pin "3") (pinfunction "1Y1_3") (pintype "tri_state"))
      (node (ref "E55") (pin "5") (pinfunction "1Y2_5") (pintype "tri_state"))
      (node (ref "E99") (pin "14") (pinfunction "D1_14") (pintype "input"))
      (node (ref "J1") (pin "1") (pinfunction "1_1") (pintype "passive"))
      (node (ref "R11") (pin "1") (pinfunction "1_1") (pintype "passive"))
    )
    (net (code "636") (name "~{RBS1}") (class "Default")
      (node (ref "E119") (pin "5") (pinfunction "Q3_5") (pintype "tri_state"))
      (node (ref "E122") (pin "5") (pinfunction "Q3_5") (pintype "tri_state"))
      (node (ref "E99") (pin "13") (pinfunction "D2_13") (pintype "input"))
      (node (ref "J1") (pin "3") (pinfunction "3_3") (pintype "passive"))
      (node (ref "R39") (pin "1") (pinfunction "1_1") (pintype "passive"))
    )
    (net (code "637") (name "~{RBS2}") (class "Default")
      (node (ref "E119") (pin "4") (pinfunction "Q2_4") (pintype "tri_state"))
      (node (ref "E122") (pin "4") (pinfunction "Q2_4") (pintype "tri_state"))
      (node (ref "E99") (pin "12") (pinfunction "D3_12") (pintype "input"))
      (node (ref "J1") (pin "5") (pinfunction "5_5") (pintype "passive"))
      (node (ref "R38") (pin "1") (pinfunction "1_1") (pintype "passive"))
    )
    (net (code "638") (name "~{RBS3}") (class "Default")
      (node (ref "E119") (pin "3") (pinfunction "Q1_3") (pintype "tri_state"))
      (node (ref "E122") (pin "3") (pinfunction "Q1_3") (pintype "tri_state"))
      (node (ref "E99") (pin "11") (pinfunction "D4_11") (pintype "input"))
      (node (ref "J1") (pin "7") (pinfunction "7_7") (pintype "passive"))
      (node (ref "R37") (pin "1") (pinfunction "1_1") (pintype "passive"))
    )
    (net (code "639") (name "~{RD0}") (class "Default")
      (node (ref "E16") (pin "10") (pinfunction "O7_10") (pintype "tri_state"))
      (node (ref "E4") (pin "10") (pinfunction "O_10") (pintype "open_collector"))
      (node (ref "E5") (pin "1") (pinfunction "I_1") (pintype "input"))
      (node (ref "E55") (pin "11") (pinfunction "2Y1_11") (pintype "tri_state"))
      (node (ref "R12") (pin "2") (pinfunction "2_2") (pintype "passive"))
    )
    (net (code "640") (name "~{RD1}") (class "Default")
      (node (ref "E100") (pin "3") (pinfunction "1Y1_3") (pintype "tri_state"))
      (node (ref "E16") (pin "11") (pinfunction "O6_11") (pintype "tri_state"))
      (node (ref "E37") (pin "13") (pinfunction "2Y2_13") (pintype "tri_state"))
      (node (ref "E5") (pin "3") (pinfunction "I_3") (pintype "input"))
      (node (ref "E91") (pin "3") (pinfunction "1Y1_3") (pintype "tri_state"))
      (node (ref "E99") (pin "3") (pinfunction "Q1_3") (pintype "tri_state"))
      (node (ref "R9") (pin "2") (pinfunction "2_2") (pintype "passive"))
    )
    (net (code "641") (name "~{RD2}") (class "Default")
      (node (ref "E100") (pin "5") (pinfunction "1Y2_5") (pintype "tri_state"))
      (node (ref "E16") (pin "12") (pinfunction "O5_12") (pintype "tri_state"))
      (node (ref "E37") (pin "11") (pinfunction "2Y1_11") (pintype "tri_state"))
      (node (ref "E5") (pin "5") (pinfunction "I_5") (pintype "input"))
      (node (ref "E91") (pin "5") (pinfunction "1Y2_5") (pintype "tri_state"))
      (node (ref "E99") (pin "4") (pinfunction "Q2_4") (pintype "tri_state"))
      (node (ref "R8") (pin "2") (pinfunction "2_2") (pintype "passive"))
    )
    (net (code "642") (name "~{RD3}") (class "Default")
      (node (ref "E100") (pin "7") (pinfunction "1Y3_7") (pintype "tri_state"))
      (node (ref "E23") (pin "4") (pinfunction "1Y_4") (pintype "tri_state"))
      (node (ref "E37") (pin "9") (pinfunction "1Y4_9") (pintype "tri_state"))
      (node (ref "E5") (pin "9") (pinfunction "I_9") (pintype "input"))
      (node (ref "E8") (pin "13") (pinfunction "O_13") (pintype "open_collector"))
      (node (ref "E83") (pin "11") (pinfunction "Y1_11") (pintype "tri_state"))
      (node (ref "E99") (pin "5") (pinfunction "Q3_5") (pintype "tri_state"))
      (node (ref "R2") (pin "2") (pinfunction "2_2") (pintype "passive"))
    )
    (net (code "643") (name "~{RD4}") (class "Default")
      (node (ref "E100") (pin "9") (pinfunction "1Y4_9") (pintype "tri_state"))
      (node (ref "E23") (pin "7") (pinfunction "2Y_7") (pintype "tri_state"))
      (node (ref "E37") (pin "7") (pinfunction "1Y3_7") (pintype "tri_state"))
      (node (ref "E7") (pin "1") (pinfunction "I_1") (pintype "input"))
      (node (ref "E91") (pin "7") (pinfunction "1Y3_7") (pintype "tri_state"))
      (node (ref "E99") (pin "6") (pinfunction "Q4_6") (pintype "tri_state"))
      (node (ref "R1") (pin "2") (pinfunction "2_2") (pintype "passive"))
    )
    (net (code "644") (name "~{RD5}") (class "Default")
      (node (ref "E111") (pin "11") (pinfunction "O1_11") (pintype "tri_state"))
      (node (ref "E16") (pin "13") (pinfunction "O4_13") (pintype "tri_state"))
      (node (ref "E37") (pin "5") (pinfunction "1Y2_5") (pintype "tri_state"))
      (node (ref "E7") (pin "3") (pinfunction "I_3") (pintype "input"))
      (node (ref "E8") (pin "10") (pinfunction "O_10") (pintype "open_collector"))
      (node (ref "E83") (pin "13") (pinfunction "Y2_13") (pintype "tri_state"))
      (node (ref "E91") (pin "9") (pinfunction "1Y4_9") (pintype "tri_state"))
      (node (ref "E98") (pin "6") (pinfunction "Q4_6") (pintype "tri_state"))
      (node (ref "R6") (pin "2") (pinfunction "2_2") (pintype "passive"))
    )
    (net (code "645") (name "~{RD6}") (class "Default")
      (node (ref "E105") (pin "13") (pinfunction "2Y2_13") (pintype "tri_state"))
      (node (ref "E106") (pin "3") (pinfunction "1Y1_3") (pintype "tri_state"))
      (node (ref "E114") (pin "12") (pinfunction "O0_12") (pintype "tri_state"))
      (node (ref "E16") (pin "15") (pinfunction "O3_15") (pintype "tri_state"))
      (node (ref "E37") (pin "3") (pinfunction "1Y1_3") (pintype "tri_state"))
      (node (ref "E7") (pin "5") (pinfunction "I_5") (pintype "input"))
      (node (ref "E83") (pin "7") (pinfunction "Y3_7") (pintype "tri_state"))
      (node (ref "E90") (pin "3") (pinfunction "Q1_3") (pintype "tri_state"))
      (node (ref "E98") (pin "5") (pinfunction "Q3_5") (pintype "tri_state"))
      (node (ref "R7") (pin "2") (pinfunction "2_2") (pintype "passive"))
    )
    (net (code "646") (name "~{RD7}") (class "Default")
      (node (ref "E105") (pin "11") (pinfunction "2Y1_11") (pintype "tri_state"))
      (node (ref "E106") (pin "5") (pinfunction "1Y2_5") (pintype "tri_state"))
      (node (ref "E112") (pin "11") (pinfunction "O1_11") (pintype "tri_state"))
      (node (ref "E16") (pin "16") (pinfunction "O2_16") (pintype "tri_state"))
      (node (ref "E7") (pin "9") (pinfunction "I_9") (pintype "input"))
      (node (ref "E83") (pin "5") (pinfunction "Y2_5") (pintype "tri_state"))
      (node (ref "E86") (pin "3") (pinfunction "1Y1_3") (pintype "tri_state"))
      (node (ref "E90") (pin "4") (pinfunction "Q2_4") (pintype "tri_state"))
      (node (ref "E98") (pin "4") (pinfunction "Q2_4") (pintype "tri_state"))
      (node (ref "R31") (pin "2") (pinfunction "2_2") (pintype "passive"))
    )
    (net (code "647") (name "~{RD8}") (class "Default")
      (node (ref "E105") (pin "9") (pinfunction "1Y4_9") (pintype "tri_state"))
      (node (ref "E106") (pin "7") (pinfunction "1Y3_7") (pintype "tri_state"))
      (node (ref "E112") (pin "12") (pinfunction "O0_12") (pintype "tri_state"))
      (node (ref "E16") (pin "17") (pinfunction "O1_17") (pintype "tri_state"))
      (node (ref "E44") (pin "1") (pinfunction "I_1") (pintype "input"))
      (node (ref "E83") (pin "3") (pinfunction "Y1_3") (pintype "tri_state"))
      (node (ref "E86") (pin "5") (pinfunction "1Y2_5") (pintype "tri_state"))
      (node (ref "E90") (pin "5") (pinfunction "Q3_5") (pintype "tri_state"))
      (node (ref "E98") (pin "3") (pinfunction "Q1_3") (pintype "tri_state"))
      (node (ref "R25") (pin "2") (pinfunction "2_2") (pintype "passive"))
    )
    (net (code "648") (name "~{RD9}") (class "Default")
      (node (ref "E101") (pin "3") (pinfunction "Y1_3") (pintype "tri_state"))
      (node (ref "E105") (pin "7") (pinfunction "1Y3_7") (pintype "tri_state"))
      (node (ref "E106") (pin "9") (pinfunction "1Y4_9") (pintype "tri_state"))
      (node (ref "E111") (pin "12") (pinfunction "O0_12") (pintype "tri_state"))
      (node (ref "E16") (pin "18") (pinfunction "O0_18") (pintype "tri_state"))
      (node (ref "E44") (pin "3") (pinfunction "I_3") (pintype "input"))
      (node (ref "E62") (pin "4") (pinfunction "Q2_4") (pintype "tri_state"))
      (node (ref "E86") (pin "7") (pinfunction "1Y3_7") (pintype "tri_state"))
      (node (ref "E90") (pin "6") (pinfunction "Q4_6") (pintype "tri_state"))
      (node (ref "R24") (pin "2") (pinfunction "2_2") (pintype "passive"))
    )
    (net (code "649") (name "~{RD10}") (class "Default")
      (node (ref "E100") (pin "11") (pinfunction "2Y1_11") (pintype "tri_state"))
      (node (ref "E101") (pin "5") (pinfunction "Y2_5") (pintype "tri_state"))
      (node (ref "E105") (pin "5") (pinfunction "1Y2_5") (pintype "tri_state"))
      (node (ref "E106") (pin "11") (pinfunction "2Y1_11") (pintype "tri_state"))
      (node (ref "E23") (pin "9") (pinfunction "3Y_9") (pintype "tri_state"))
      (node (ref "E44") (pin "5") (pinfunction "I_5") (pintype "input"))
      (node (ref "E62") (pin "5") (pinfunction "Q3_5") (pintype "tri_state"))
      (node (ref "E86") (pin "9") (pinfunction "1Y4_9") (pintype "tri_state"))
      (node (ref "R26") (pin "2") (pinfunction "2_2") (pintype "passive"))
    )
    (net (code "650") (name "~{RD11}") (class "Default")
      (node (ref "E100") (pin "13") (pinfunction "2Y2_13") (pintype "tri_state"))
      (node (ref "E101") (pin "7") (pinfunction "Y3_7") (pintype "tri_state"))
      (node (ref "E105") (pin "3") (pinfunction "1Y1_3") (pintype "tri_state"))
      (node (ref "E106") (pin "13") (pinfunction "2Y2_13") (pintype "tri_state"))
      (node (ref "E23") (pin "12") (pinfunction "4Y_12") (pintype "tri_state"))
      (node (ref "E44") (pin "9") (pinfunction "I_9") (pintype "input"))
      (node (ref "E62") (pin "6") (pinfunction "Q4_6") (pintype "tri_state"))
      (node (ref "E86") (pin "11") (pinfunction "2Y1_11") (pintype "tri_state"))
      (node (ref "R27") (pin "2") (pinfunction "2_2") (pintype "passive"))
    )
    (net (code "651") (name "~{RUN}") (class "Default")
      (node (ref "E66") (pin "4") (pinfunction "I0_4") (pintype "input"))
      (node (ref "U$1") (pin "BU2") (pinfunction "1_BU2") (pintype "bidirectional"))
    )
    (net (code "652") (name "~{SB0}") (class "Default")
      (node (ref "E100") (pin "2") (pinfunction "1A1_2") (pintype "input"))
      (node (ref "E109") (pin "23") (pinfunction "I12_23") (pintype "input"))
      (node (ref "E117") (pin "14") (pinfunction "~{Q4}_14") (pintype "output"))
    )
    (net (code "653") (name "~{SB1}") (class "Default")
      (node (ref "E100") (pin "4") (pinfunction "1A2_4") (pintype "input"))
      (node (ref "E109") (pin "24") (pinfunction "I11_24") (pintype "input"))
      (node (ref "E117") (pin "11") (pinfunction "~{Q3}_11") (pintype "output"))
    )
    (net (code "654") (name "~{SB2}") (class "Default")
      (node (ref "E100") (pin "6") (pinfunction "1A3_6") (pintype "input"))
      (node (ref "E109") (pin "25") (pinfunction "I10_25") (pintype "input"))
      (node (ref "E117") (pin "6") (pinfunction "~{Q2}_6") (pintype "output"))
    )
    (net (code "655") (name "~{SB3}") (class "Default")
      (node (ref "E100") (pin "10") (pinfunction "1A4_10") (pintype "input"))
      (node (ref "E109") (pin "26") (pinfunction "I9_26") (pintype "input"))
      (node (ref "E117") (pin "3") (pinfunction "~{Q1}_3") (pintype "output"))
    )
    (net (code "656") (name "~{SKIP}") (class "Default")
      (node (ref "E42") (pin "4") (pinfunction "O_4") (pintype "open_collector"))
      (node (ref "U$1") (pin "CS1") (pinfunction "1_CS1") (pintype "bidirectional"))
    )
    (net (code "657") (name "~{TS1}") (class "Default")
      (node (ref "E41") (pin "10") (pinfunction "I1_10") (pintype "input"))
      (node (ref "E41") (pin "11") (pinfunction "I0_11") (pintype "input"))
      (node (ref "U$1") (pin "CK2") (pinfunction "1_CK2") (pintype "bidirectional"))
    )
    (net (code "658") (name "~{TS3}") (class "Default")
      (node (ref "E51") (pin "12") (pinfunction "I1_12") (pintype "input"))
      (node (ref "U$1") (pin "CM2") (pinfunction "1_CM2") (pintype "bidirectional"))
    )
    (net (code "659") (name "~{TS4}") (class "Default")
      (node (ref "E51") (pin "4") (pinfunction "I0_4") (pintype "input"))
      (node (ref "U$1") (pin "CP2") (pinfunction "1_CP2") (pintype "bidirectional"))
    )
    (net (code "660") (name "~{USER_MODE}") (class "Default")
      (node (ref "E8") (pin "1") (pinfunction "O_1") (pintype "open_collector"))
      (node (ref "E8") (pin "4") (pinfunction "O_4") (pintype "open_collector"))
      (node (ref "U$1") (pin "DM2") (pinfunction "1_DM2") (pintype "bidirectional"))
    )
  )
)
